# sch.net
KiCad netlist of a schematic drawn in EasyEDA Pro
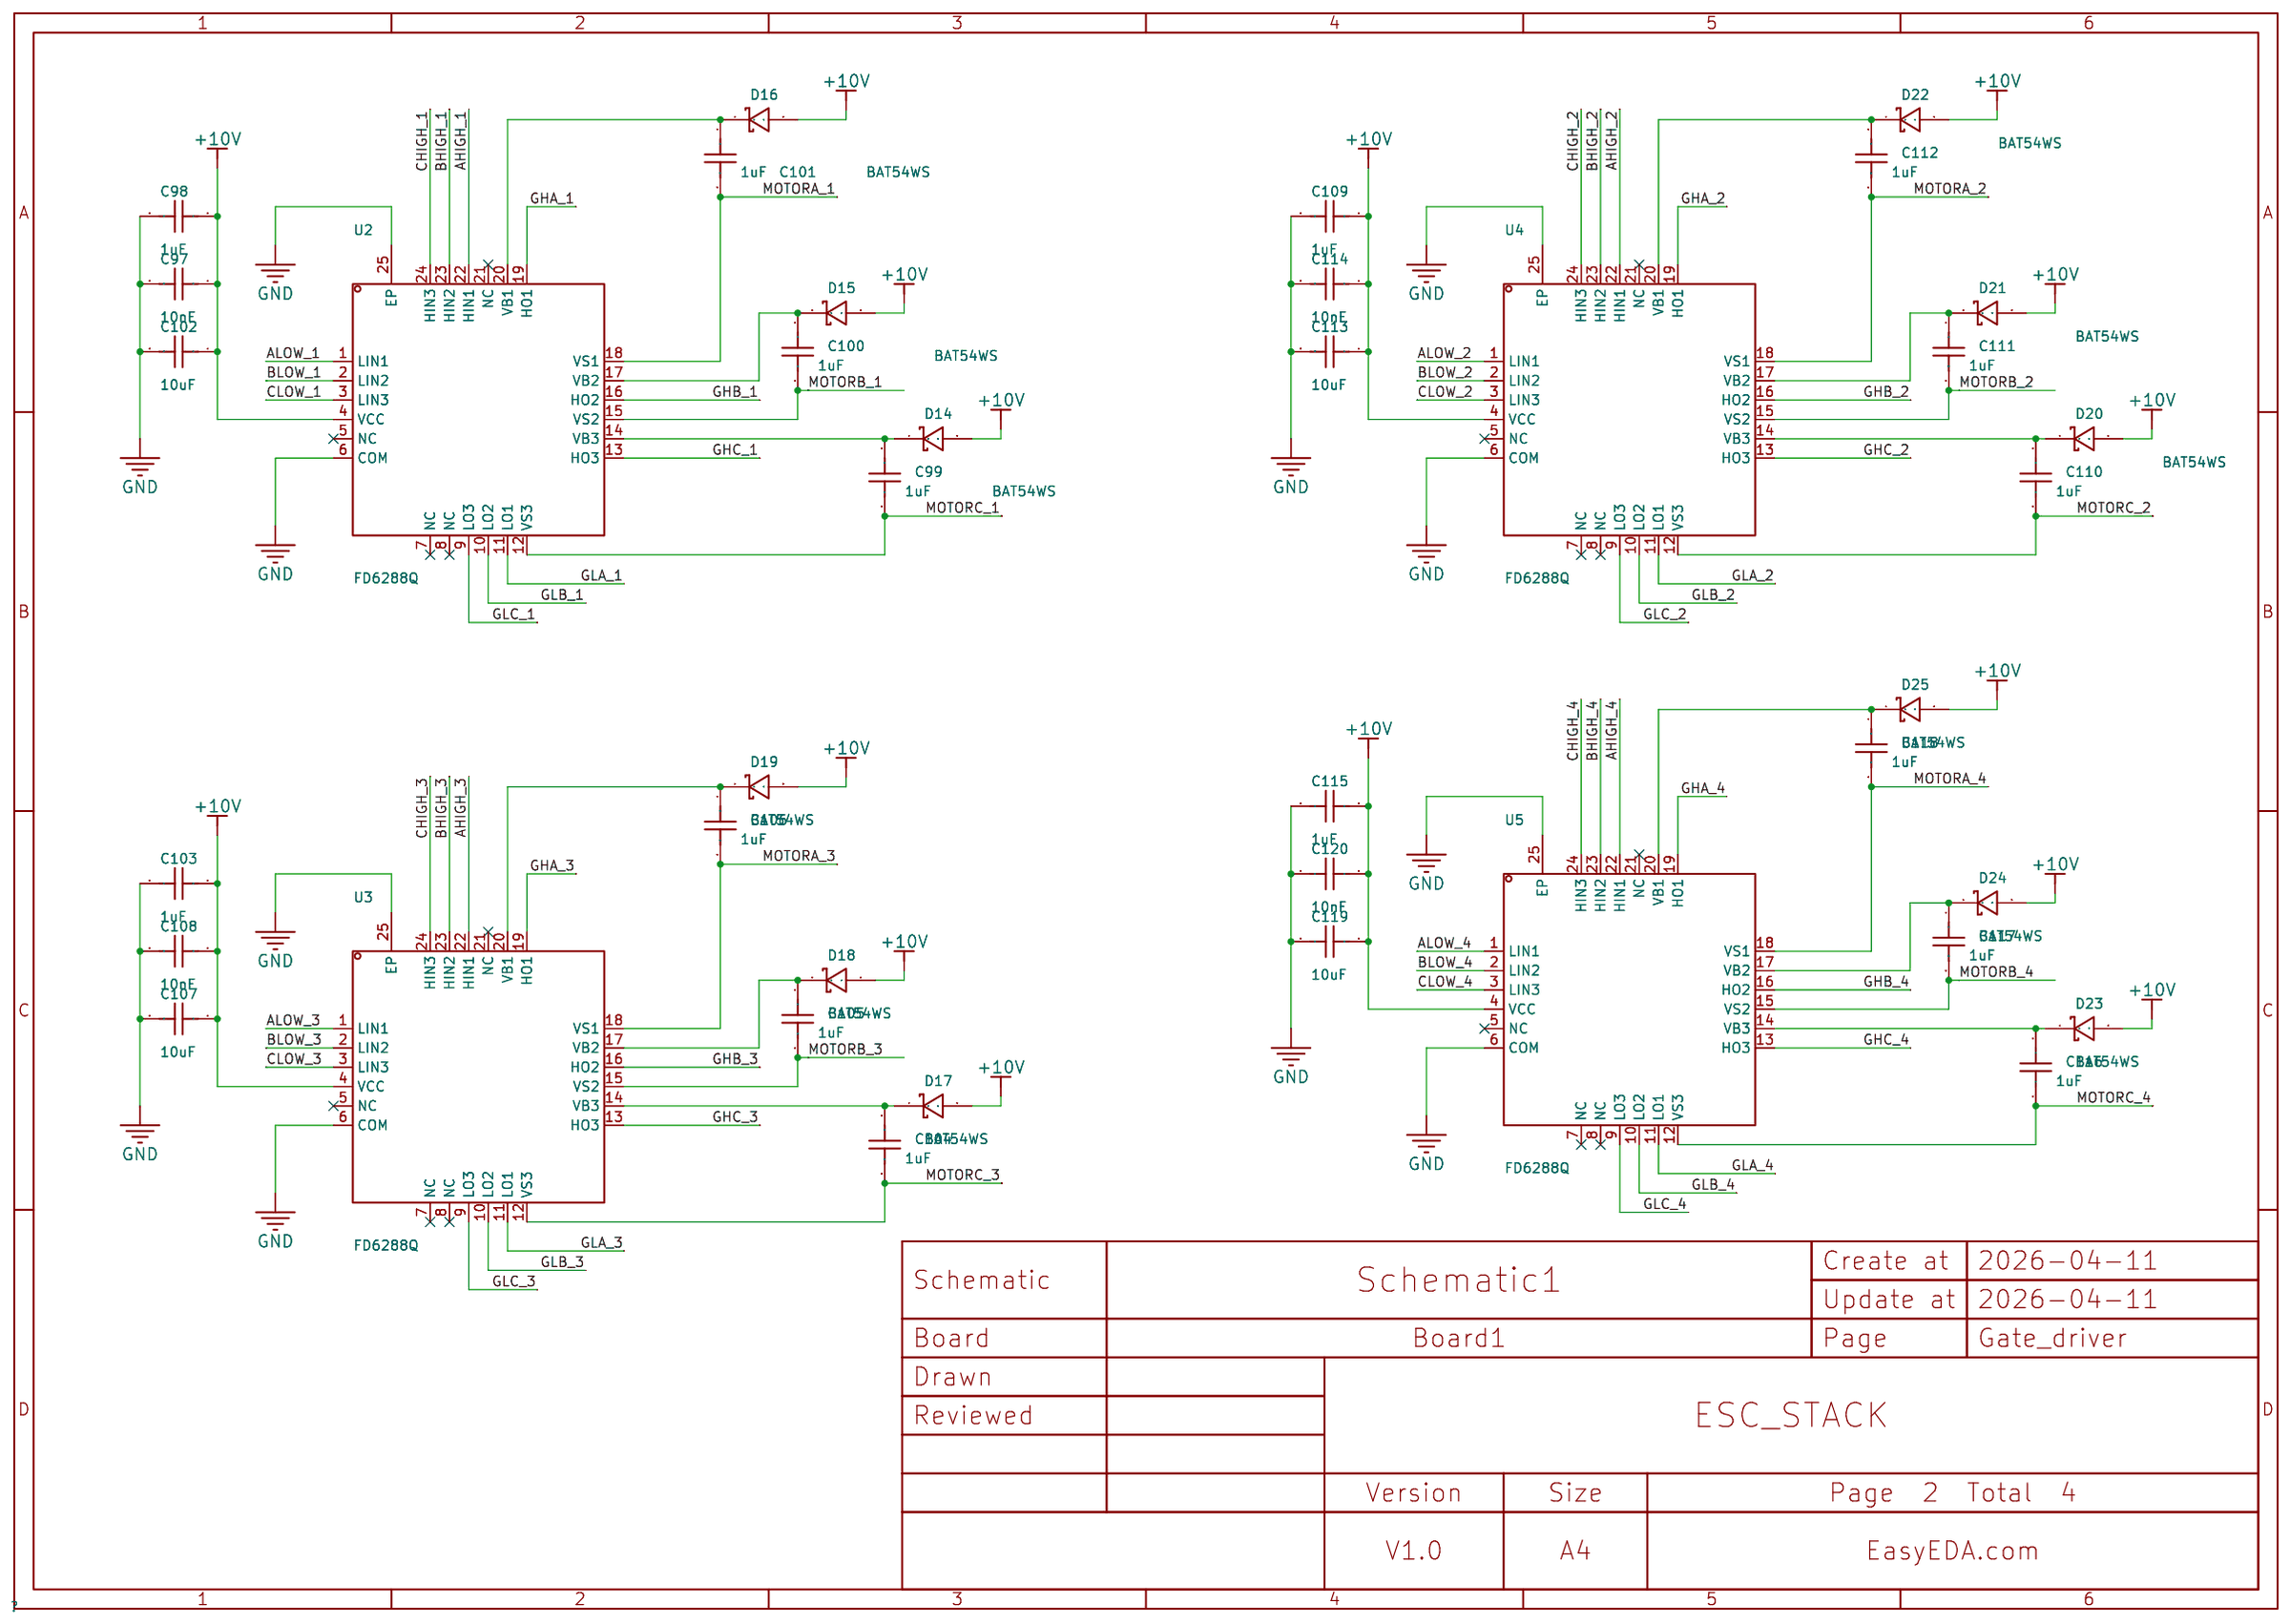
[diagram p0: Gate_driver]
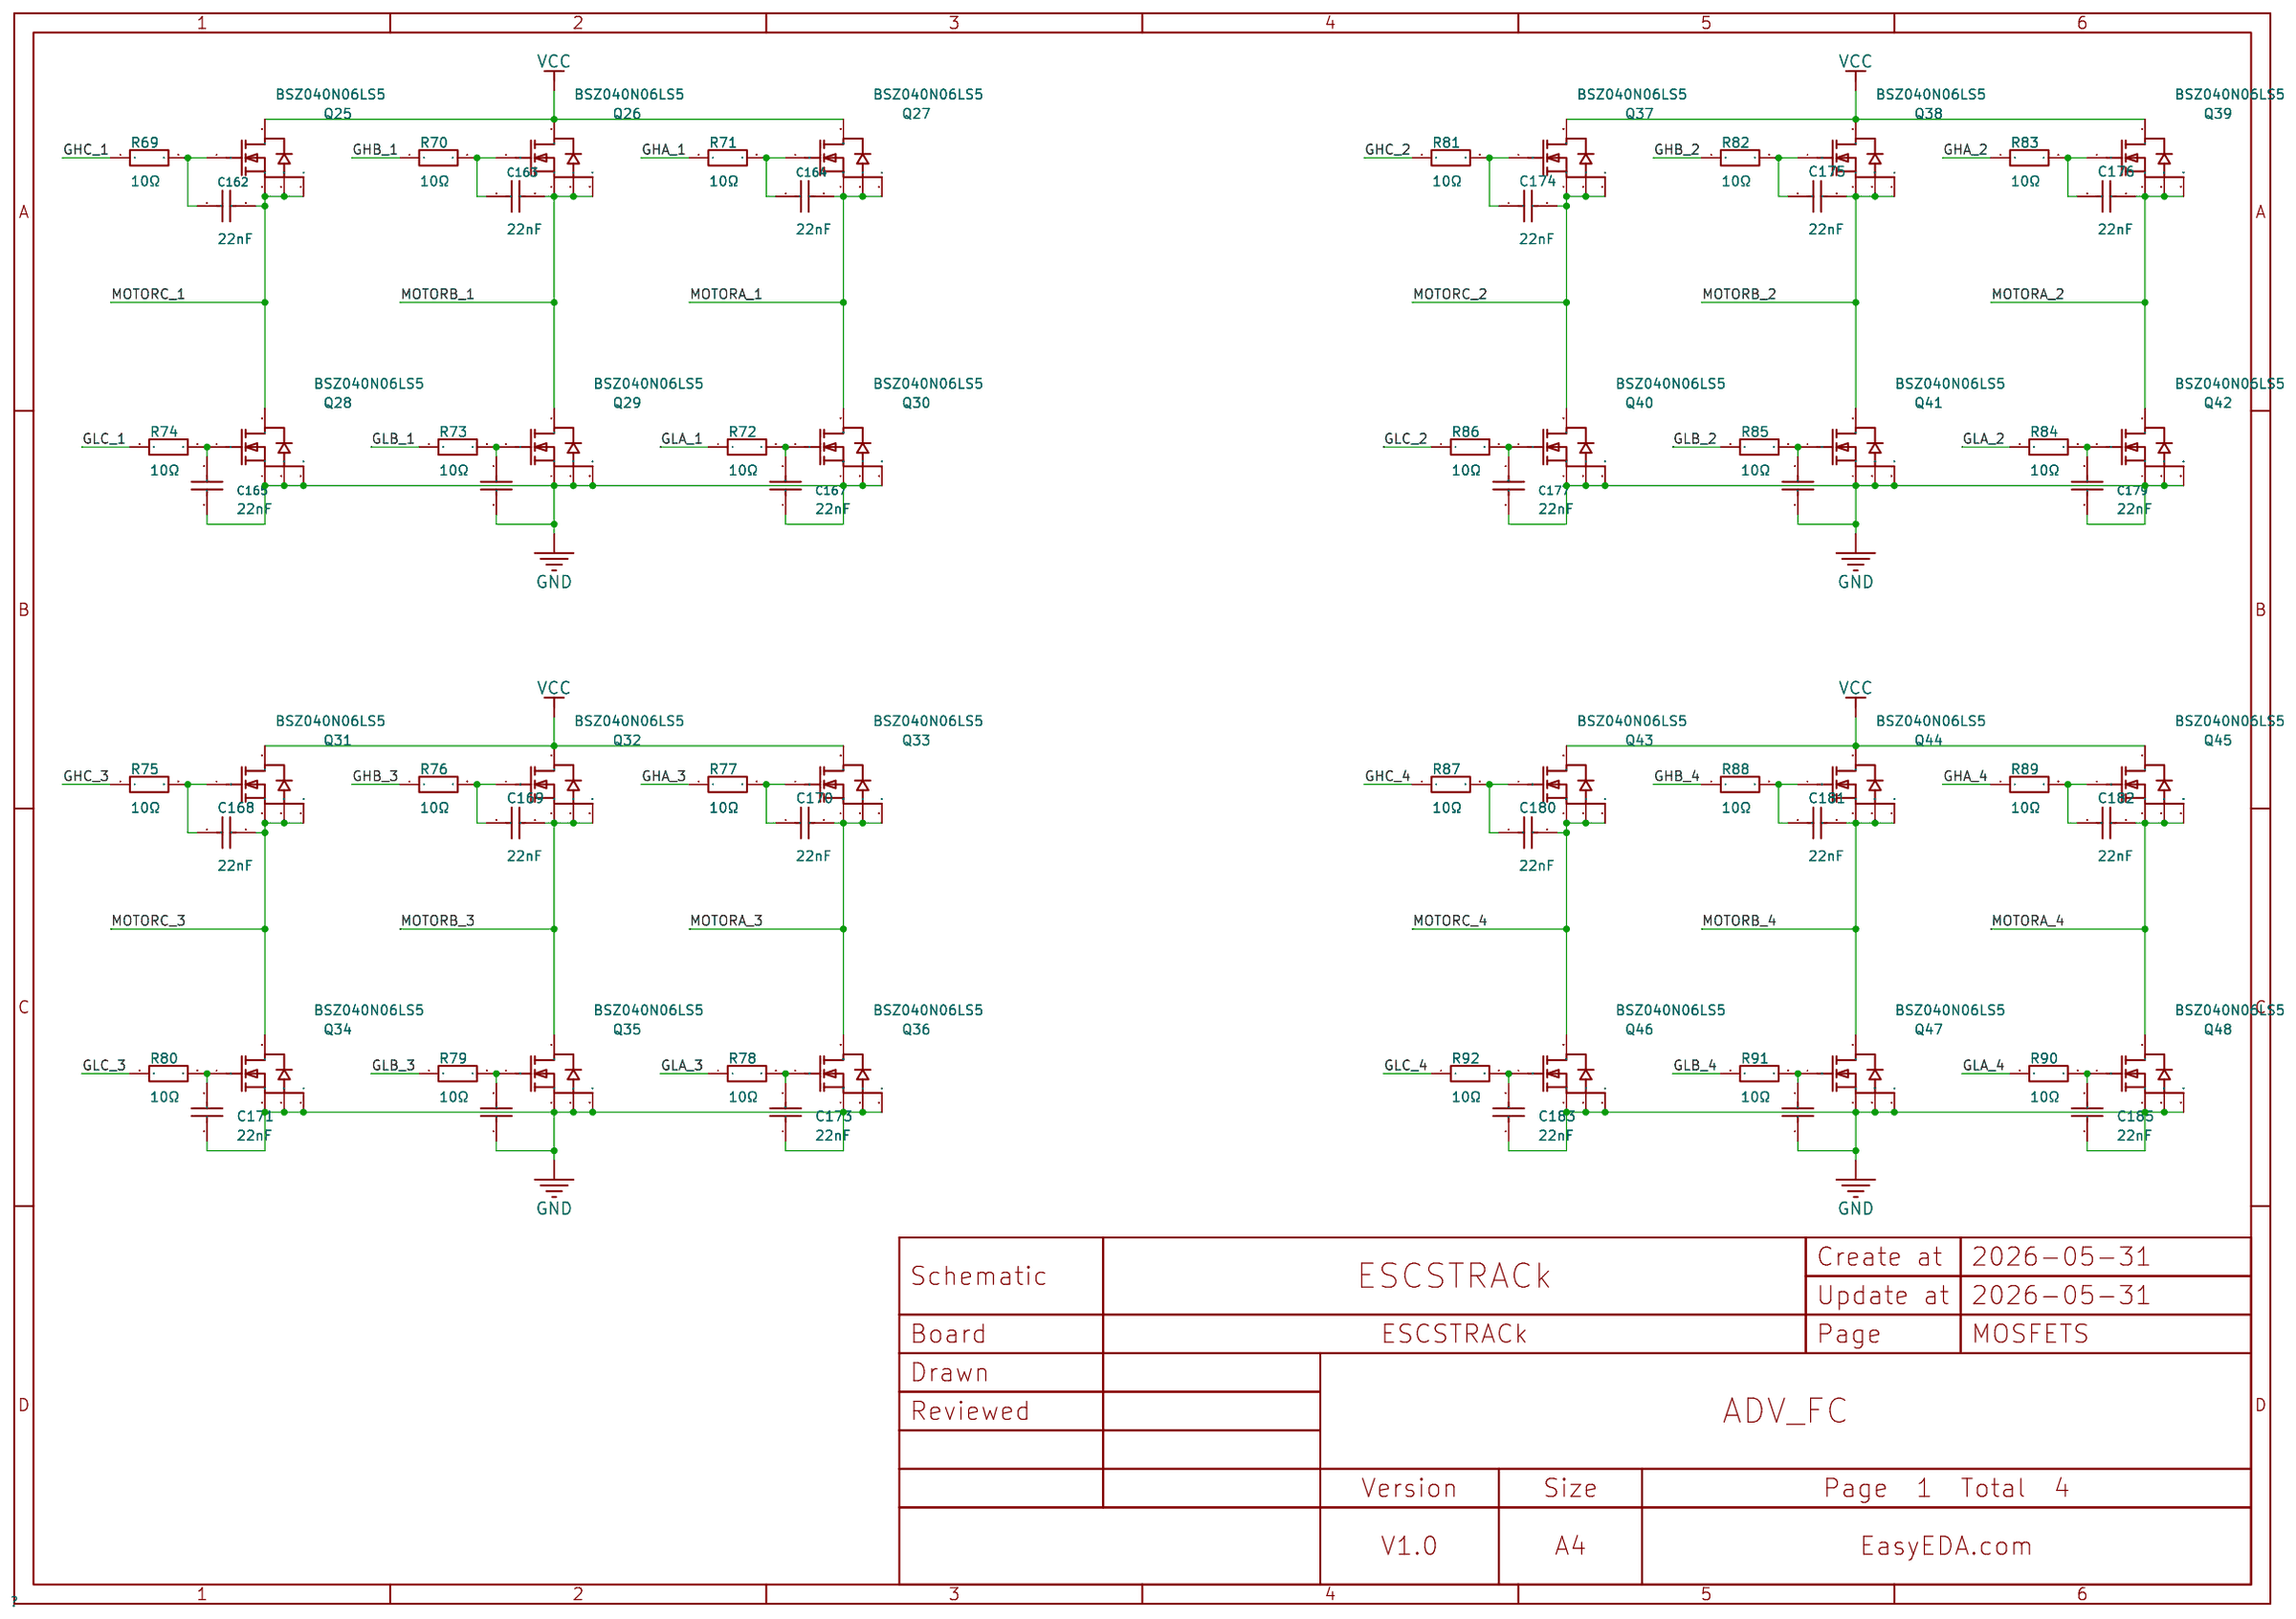
[diagram p1: MOSFETS]
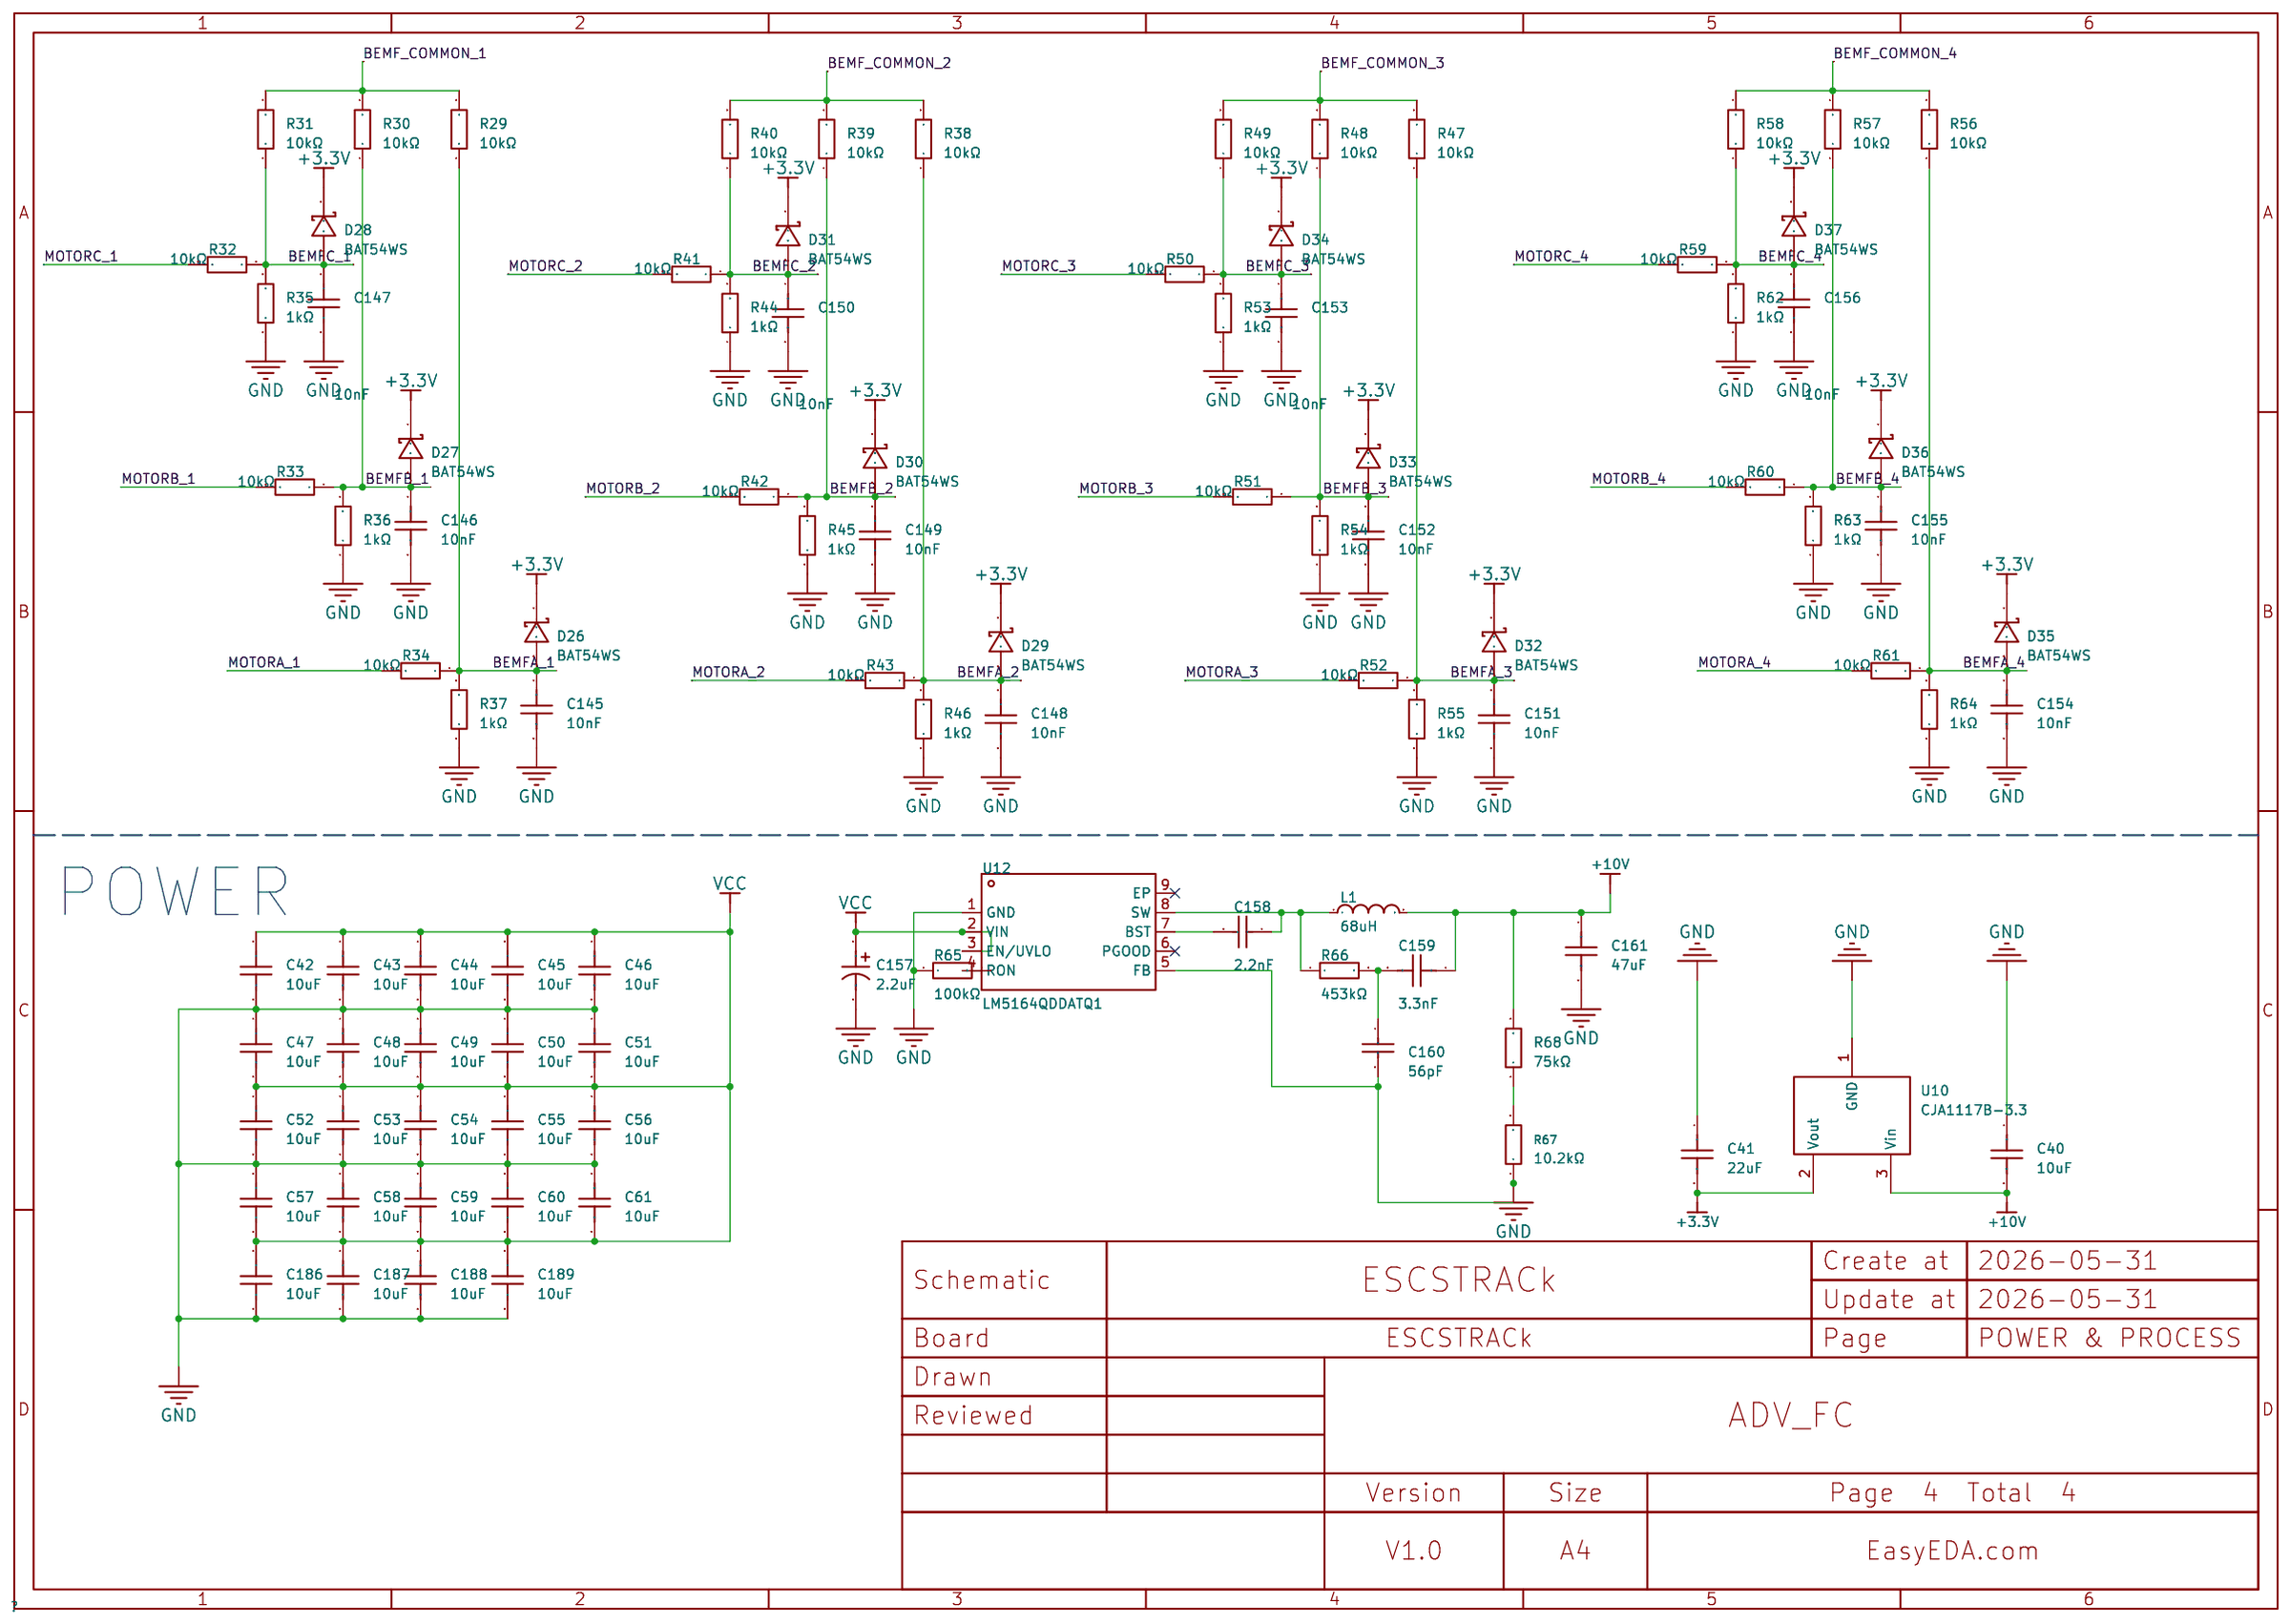
[diagram p2: POWER & PROCESS]
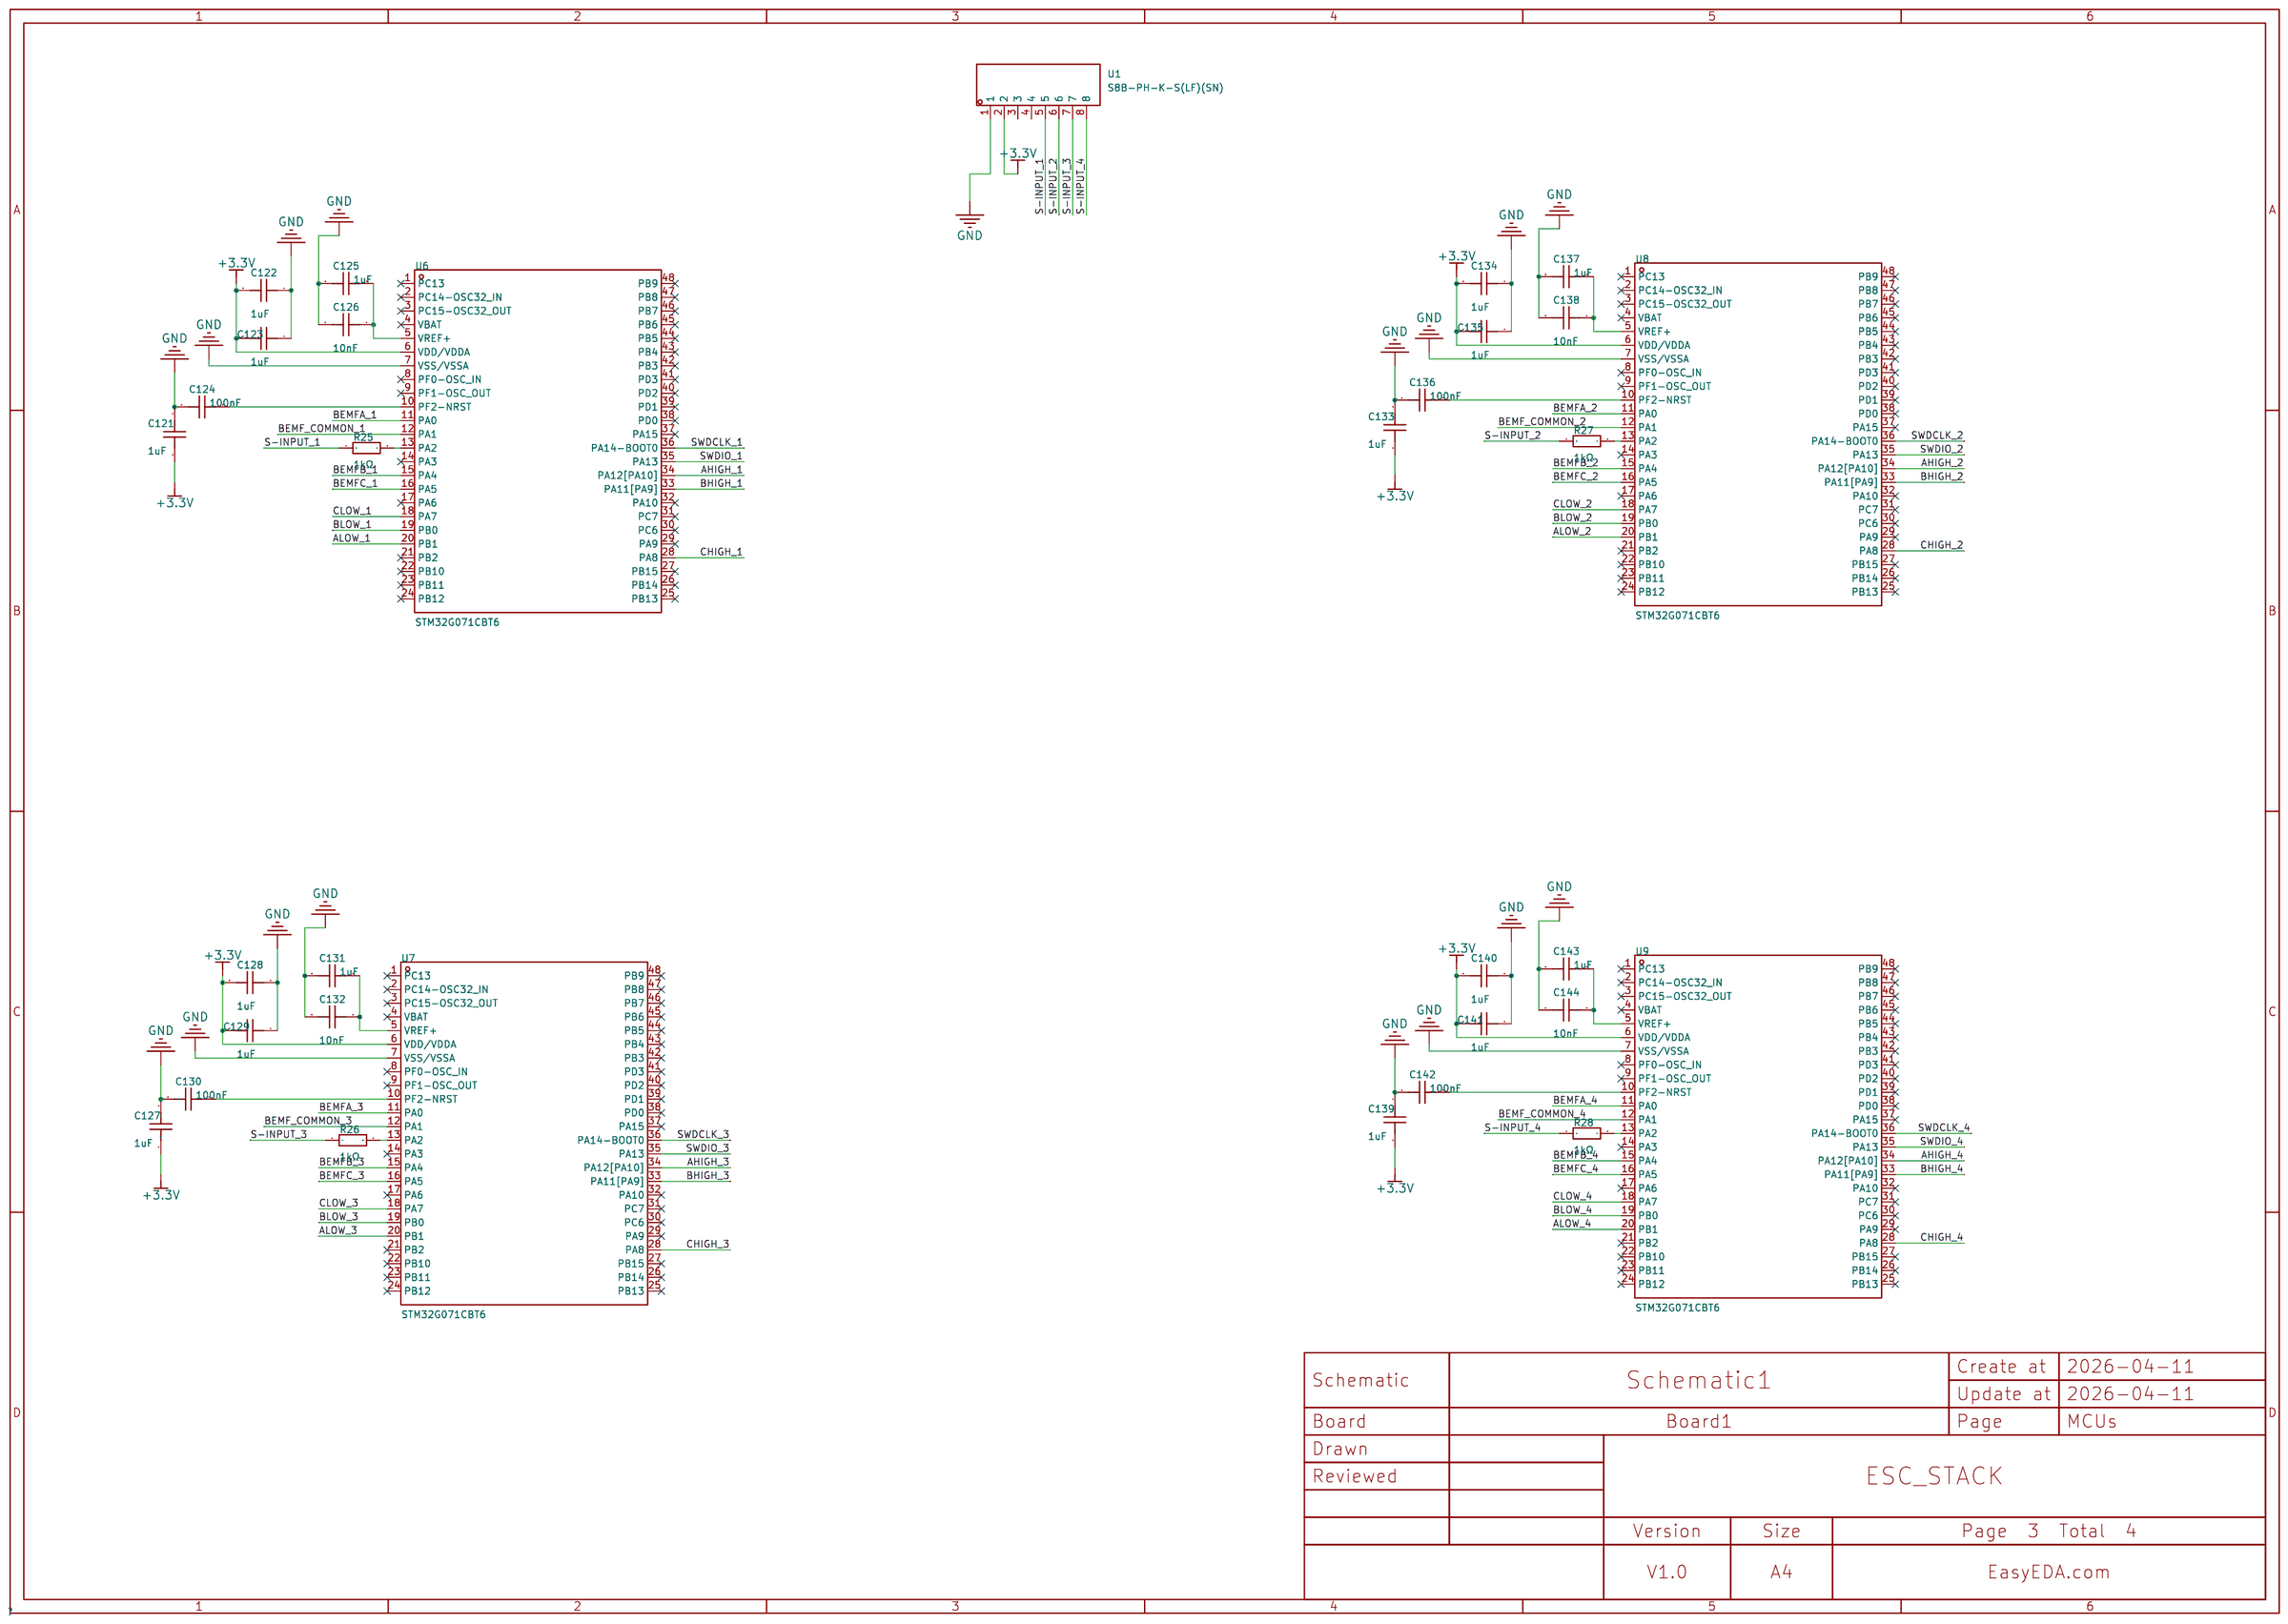
[diagram p3: MCUs]

(export (version "E")
  (design (tool "Eeschema 10.0.6"))
  (components
    (comp (ref "C97")
      (value "10nF")
      (description "Capacitance:10nF Tolerance:±10% Tolerance:±10% Voltage Rating:50V Temperature Coefficient:X7R")
      (fields
        (field (name "Manufacturer Part") "CC0402KRX7R9BB103")
        (field (name "Manufacturer") "YAGEO(国巨)")
      )
      (libsource (lib "easyedapro") (part "CAP"))
    )
    (comp (ref "C98")
      (value "1uF")
      (description "Capacitance:1uF Tolerance:±10% Tolerance:±10% Voltage Rating:25V Temperature Coefficient:X5R")
      (fields
        (field (name "Manufacturer Part") "CL05A105KA5NQNC")
        (field (name "Manufacturer") "SAMSUNG(三星)")
      )
      (libsource (lib "easyedapro") (part "CAP"))
    )
    (comp (ref "C99")
      (value "1uF")
      (description "Capacitance:1uF Tolerance:±10% Tolerance:±10% Voltage Rating:25V Temperature Coefficient:X5R")
      (fields
        (field (name "Manufacturer Part") "CL05A105KA5NQNC")
        (field (name "Manufacturer") "SAMSUNG(三星)")
      )
      (libsource (lib "easyedapro") (part "CAP"))
    )
    (comp (ref "C100")
      (value "1uF")
      (description "Capacitance:1uF Tolerance:±10% Tolerance:±10% Voltage Rating:25V Temperature Coefficient:X5R")
      (fields
        (field (name "Manufacturer Part") "CL05A105KA5NQNC")
        (field (name "Manufacturer") "SAMSUNG(三星)")
      )
      (libsource (lib "easyedapro") (part "CAP"))
    )
    (comp (ref "C101")
      (value "1uF")
      (description "Capacitance:1uF Tolerance:±10% Tolerance:±10% Voltage Rating:25V Temperature Coefficient:X5R")
      (fields
        (field (name "Manufacturer Part") "CL05A105KA5NQNC")
        (field (name "Manufacturer") "SAMSUNG(三星)")
      )
      (libsource (lib "easyedapro") (part "CAP"))
    )
    (comp (ref "C102")
      (value "10uF")
      (description "Capacitance:10uF Tolerance:±10% Tolerance:±10% Voltage Rating:50V Temperature Coefficient:X5R")
      (fields
        (field (name "Manufacturer Part") "CL31A106KBHNNNE")
        (field (name "Manufacturer") "SAMSUNG(三星)")
      )
      (libsource (lib "easyedapro") (part "CAP"))
    )
    (comp (ref "C103")
      (value "1uF")
      (description "Capacitance:1uF Tolerance:±10% Tolerance:±10% Voltage Rating:25V Temperature Coefficient:X5R")
      (fields
        (field (name "Manufacturer Part") "CL05A105KA5NQNC")
        (field (name "Manufacturer") "SAMSUNG(三星)")
      )
      (libsource (lib "easyedapro") (part "CAP"))
    )
    (comp (ref "C104")
      (value "1uF")
      (description "Capacitance:1uF Tolerance:±10% Tolerance:±10% Voltage Rating:25V Temperature Coefficient:X5R")
      (fields
        (field (name "Manufacturer Part") "CL05A105KA5NQNC")
        (field (name "Manufacturer") "SAMSUNG(三星)")
      )
      (libsource (lib "easyedapro") (part "CAP"))
    )
    (comp (ref "C105")
      (value "1uF")
      (description "Capacitance:1uF Tolerance:±10% Tolerance:±10% Voltage Rating:25V Temperature Coefficient:X5R")
      (fields
        (field (name "Manufacturer Part") "CL05A105KA5NQNC")
        (field (name "Manufacturer") "SAMSUNG(三星)")
      )
      (libsource (lib "easyedapro") (part "CAP"))
    )
    (comp (ref "C106")
      (value "1uF")
      (description "Capacitance:1uF Tolerance:±10% Tolerance:±10% Voltage Rating:25V Temperature Coefficient:X5R")
      (fields
        (field (name "Manufacturer Part") "CL05A105KA5NQNC")
        (field (name "Manufacturer") "SAMSUNG(三星)")
      )
      (libsource (lib "easyedapro") (part "CAP"))
    )
    (comp (ref "C107")
      (value "10uF")
      (description "Capacitance:10uF Tolerance:±10% Tolerance:±10% Voltage Rating:50V Temperature Coefficient:X5R")
      (fields
        (field (name "Manufacturer Part") "CL31A106KBHNNNE")
        (field (name "Manufacturer") "SAMSUNG(三星)")
      )
      (libsource (lib "easyedapro") (part "CAP"))
    )
    (comp (ref "C108")
      (value "10nF")
      (description "Capacitance:10nF Tolerance:±10% Tolerance:±10% Voltage Rating:50V Temperature Coefficient:X7R")
      (fields
        (field (name "Manufacturer Part") "CC0402KRX7R9BB103")
        (field (name "Manufacturer") "YAGEO(国巨)")
      )
      (libsource (lib "easyedapro") (part "CAP"))
    )
    (comp (ref "C109")
      (value "1uF")
      (description "Capacitance:1uF Tolerance:±10% Tolerance:±10% Voltage Rating:25V Temperature Coefficient:X5R")
      (fields
        (field (name "Manufacturer Part") "CL05A105KA5NQNC")
        (field (name "Manufacturer") "SAMSUNG(三星)")
      )
      (libsource (lib "easyedapro") (part "CAP"))
    )
    (comp (ref "C110")
      (value "1uF")
      (description "Capacitance:1uF Tolerance:±10% Tolerance:±10% Voltage Rating:25V Temperature Coefficient:X5R")
      (fields
        (field (name "Manufacturer Part") "CL05A105KA5NQNC")
        (field (name "Manufacturer") "SAMSUNG(三星)")
      )
      (libsource (lib "easyedapro") (part "CAP"))
    )
    (comp (ref "C111")
      (value "1uF")
      (description "Capacitance:1uF Tolerance:±10% Tolerance:±10% Voltage Rating:25V Temperature Coefficient:X5R")
      (fields
        (field (name "Manufacturer Part") "CL05A105KA5NQNC")
        (field (name "Manufacturer") "SAMSUNG(三星)")
      )
      (libsource (lib "easyedapro") (part "CAP"))
    )
    (comp (ref "C112")
      (value "1uF")
      (description "Capacitance:1uF Tolerance:±10% Tolerance:±10% Voltage Rating:25V Temperature Coefficient:X5R")
      (fields
        (field (name "Manufacturer Part") "CL05A105KA5NQNC")
        (field (name "Manufacturer") "SAMSUNG(三星)")
      )
      (libsource (lib "easyedapro") (part "CAP"))
    )
    (comp (ref "C113")
      (value "10uF")
      (description "Capacitance:10uF Tolerance:±10% Tolerance:±10% Voltage Rating:50V Temperature Coefficient:X5R")
      (fields
        (field (name "Manufacturer Part") "CL31A106KBHNNNE")
        (field (name "Manufacturer") "SAMSUNG(三星)")
      )
      (libsource (lib "easyedapro") (part "CAP"))
    )
    (comp (ref "C114")
      (value "10nF")
      (description "Capacitance:10nF Tolerance:±10% Tolerance:±10% Voltage Rating:50V Temperature Coefficient:X7R")
      (fields
        (field (name "Manufacturer Part") "CC0402KRX7R9BB103")
        (field (name "Manufacturer") "YAGEO(国巨)")
      )
      (libsource (lib "easyedapro") (part "CAP"))
    )
    (comp (ref "C115")
      (value "1uF")
      (description "Capacitance:1uF Tolerance:±10% Tolerance:±10% Voltage Rating:25V Temperature Coefficient:X5R")
      (fields
        (field (name "Manufacturer Part") "CL05A105KA5NQNC")
        (field (name "Manufacturer") "SAMSUNG(三星)")
      )
      (libsource (lib "easyedapro") (part "CAP"))
    )
    (comp (ref "C116")
      (value "1uF")
      (description "Capacitance:1uF Tolerance:±10% Tolerance:±10% Voltage Rating:25V Temperature Coefficient:X5R")
      (fields
        (field (name "Manufacturer Part") "CL05A105KA5NQNC")
        (field (name "Manufacturer") "SAMSUNG(三星)")
      )
      (libsource (lib "easyedapro") (part "CAP"))
    )
    (comp (ref "C117")
      (value "1uF")
      (description "Capacitance:1uF Tolerance:±10% Tolerance:±10% Voltage Rating:25V Temperature Coefficient:X5R")
      (fields
        (field (name "Manufacturer Part") "CL05A105KA5NQNC")
        (field (name "Manufacturer") "SAMSUNG(三星)")
      )
      (libsource (lib "easyedapro") (part "CAP"))
    )
    (comp (ref "C118")
      (value "1uF")
      (description "Capacitance:1uF Tolerance:±10% Tolerance:±10% Voltage Rating:25V Temperature Coefficient:X5R")
      (fields
        (field (name "Manufacturer Part") "CL05A105KA5NQNC")
        (field (name "Manufacturer") "SAMSUNG(三星)")
      )
      (libsource (lib "easyedapro") (part "CAP"))
    )
    (comp (ref "C119")
      (value "10uF")
      (description "Capacitance:10uF Tolerance:±10% Tolerance:±10% Voltage Rating:50V Temperature Coefficient:X5R")
      (fields
        (field (name "Manufacturer Part") "CL31A106KBHNNNE")
        (field (name "Manufacturer") "SAMSUNG(三星)")
      )
      (libsource (lib "easyedapro") (part "CAP"))
    )
    (comp (ref "C120")
      (value "10nF")
      (description "Capacitance:10nF Tolerance:±10% Tolerance:±10% Voltage Rating:50V Temperature Coefficient:X7R")
      (fields
        (field (name "Manufacturer Part") "CC0402KRX7R9BB103")
        (field (name "Manufacturer") "YAGEO(国巨)")
      )
      (libsource (lib "easyedapro") (part "CAP"))
    )
    (comp (ref "D14")
      (value "BAT54WS")
      (footprint "easyedapro:SOD-323_L1.7-W1.3-LS2.6-RD-1")
      (fields (field (name "Manufacturer") "High Diode(海德)"))
      (libsource (lib "easyedapro") (part "BAT54WS_C466657"))
    )
    (comp (ref "D15")
      (value "BAT54WS")
      (footprint "easyedapro:SOD-323_L1.7-W1.3-LS2.6-RD-1")
      (fields (field (name "Manufacturer") "High Diode(海德)"))
      (libsource (lib "easyedapro") (part "BAT54WS_C466657"))
    )
    (comp (ref "D16")
      (value "BAT54WS")
      (footprint "easyedapro:SOD-323_L1.7-W1.3-LS2.6-RD-1")
      (fields (field (name "Manufacturer") "High Diode(海德)"))
      (libsource (lib "easyedapro") (part "BAT54WS_C466657"))
    )
    (comp (ref "D17")
      (value "BAT54WS")
      (footprint "easyedapro:SOD-323_L1.7-W1.3-LS2.6-RD-1")
      (fields (field (name "Manufacturer") "High Diode(海德)"))
      (libsource (lib "easyedapro") (part "BAT54WS_C466657"))
    )
    (comp (ref "D18")
      (value "BAT54WS")
      (footprint "easyedapro:SOD-323_L1.7-W1.3-LS2.6-RD-1")
      (fields (field (name "Manufacturer") "High Diode(海德)"))
      (libsource (lib "easyedapro") (part "BAT54WS_C466657"))
    )
    (comp (ref "D19")
      (value "BAT54WS")
      (footprint "easyedapro:SOD-323_L1.7-W1.3-LS2.6-RD-1")
      (fields (field (name "Manufacturer") "High Diode(海德)"))
      (libsource (lib "easyedapro") (part "BAT54WS_C466657"))
    )
    (comp (ref "D20")
      (value "BAT54WS")
      (footprint "easyedapro:SOD-323_L1.7-W1.3-LS2.6-RD-1")
      (fields (field (name "Manufacturer") "High Diode(海德)"))
      (libsource (lib "easyedapro") (part "BAT54WS_C466657"))
    )
    (comp (ref "D21")
      (value "BAT54WS")
      (footprint "easyedapro:SOD-323_L1.7-W1.3-LS2.6-RD-1")
      (fields (field (name "Manufacturer") "High Diode(海德)"))
      (libsource (lib "easyedapro") (part "BAT54WS_C466657"))
    )
    (comp (ref "D22")
      (value "BAT54WS")
      (footprint "easyedapro:SOD-323_L1.7-W1.3-LS2.6-RD-1")
      (fields (field (name "Manufacturer") "High Diode(海德)"))
      (libsource (lib "easyedapro") (part "BAT54WS_C466657"))
    )
    (comp (ref "D23")
      (value "BAT54WS")
      (footprint "easyedapro:SOD-323_L1.7-W1.3-LS2.6-RD-1")
      (fields (field (name "Manufacturer") "High Diode(海德)"))
      (libsource (lib "easyedapro") (part "BAT54WS_C466657"))
    )
    (comp (ref "D24")
      (value "BAT54WS")
      (footprint "easyedapro:SOD-323_L1.7-W1.3-LS2.6-RD-1")
      (fields (field (name "Manufacturer") "High Diode(海德)"))
      (libsource (lib "easyedapro") (part "BAT54WS_C466657"))
    )
    (comp (ref "D25")
      (value "BAT54WS")
      (footprint "easyedapro:SOD-323_L1.7-W1.3-LS2.6-RD-1")
      (fields (field (name "Manufacturer") "High Diode(海德)"))
      (libsource (lib "easyedapro") (part "BAT54WS_C466657"))
    )
    (comp (ref "U2")
      (value "FD6288Q")
      (footprint "easyedapro:QFN-24_L4.0-W4.0-P0.50-BL-EP2.6")
      (fields (field (name "Manufacturer") "Fortior Tech(峰岹)"))
      (libsource (lib "easyedapro") (part "FD6288Q_C328453"))
    )
    (comp (ref "U3")
      (value "FD6288Q")
      (footprint "easyedapro:QFN-24_L4.0-W4.0-P0.50-BL-EP2.6")
      (fields (field (name "Manufacturer") "Fortior Tech(峰岹)"))
      (libsource (lib "easyedapro") (part "FD6288Q_C328453"))
    )
    (comp (ref "U4")
      (value "FD6288Q")
      (footprint "easyedapro:QFN-24_L4.0-W4.0-P0.50-BL-EP2.6")
      (fields (field (name "Manufacturer") "Fortior Tech(峰岹)"))
      (libsource (lib "easyedapro") (part "FD6288Q_C328453"))
    )
    (comp (ref "U5")
      (value "FD6288Q")
      (footprint "easyedapro:QFN-24_L4.0-W4.0-P0.50-BL-EP2.6")
      (fields (field (name "Manufacturer") "Fortior Tech(峰岹)"))
      (libsource (lib "easyedapro") (part "FD6288Q_C328453"))
    )
    (comp (ref "C162")
      (value "22nF")
      (footprint "easyedapro:C0603")
      (description "Capacitance:22nF Tolerance:±10% Tolerance:±10% Voltage Rating:50V Temperature Coefficient:X7R")
      (fields
        (field (name "Manufacturer Part") "CL10B223KB8NNNC")
        (field (name "Manufacturer") "SAMSUNG(三星)")
      )
      (libsource (lib "easyedapro") (part "CL10B223KB8NNNC"))
    )
    (comp (ref "C163")
      (value "22nF")
      (footprint "easyedapro:C0603")
      (description "Capacitance:22nF Tolerance:±10% Tolerance:±10% Voltage Rating:50V Temperature Coefficient:X7R")
      (fields
        (field (name "Manufacturer Part") "CL10B223KB8NNNC")
        (field (name "Manufacturer") "SAMSUNG(三星)")
      )
      (libsource (lib "easyedapro") (part "CL10B223KB8NNNC"))
    )
    (comp (ref "C164")
      (value "22nF")
      (footprint "easyedapro:C0603")
      (description "Capacitance:22nF Tolerance:±10% Tolerance:±10% Voltage Rating:50V Temperature Coefficient:X7R")
      (fields
        (field (name "Manufacturer Part") "CL10B223KB8NNNC")
        (field (name "Manufacturer") "SAMSUNG(三星)")
      )
      (libsource (lib "easyedapro") (part "CL10B223KB8NNNC"))
    )
    (comp (ref "C165")
      (value "22nF")
      (footprint "easyedapro:C0603")
      (description "Capacitance:22nF Tolerance:±10% Tolerance:±10% Voltage Rating:50V Temperature Coefficient:X7R")
      (fields
        (field (name "Manufacturer Part") "CL10B223KB8NNNC")
        (field (name "Manufacturer") "SAMSUNG(三星)")
      )
      (libsource (lib "easyedapro") (part "CL10B223KB8NNNC"))
    )
    (comp (ref "C166")
      (value "22nF")
      (footprint "easyedapro:C0603")
      (description "Capacitance:22nF Tolerance:±10% Tolerance:±10% Voltage Rating:50V Temperature Coefficient:X7R")
      (fields
        (field (name "Manufacturer Part") "CL10B223KB8NNNC")
        (field (name "Manufacturer") "SAMSUNG(三星)")
      )
      (libsource (lib "easyedapro") (part "CL10B223KB8NNNC"))
    )
    (comp (ref "C167")
      (value "22nF")
      (footprint "easyedapro:C0603")
      (description "Capacitance:22nF Tolerance:±10% Tolerance:±10% Voltage Rating:50V Temperature Coefficient:X7R")
      (fields
        (field (name "Manufacturer Part") "CL10B223KB8NNNC")
        (field (name "Manufacturer") "SAMSUNG(三星)")
      )
      (libsource (lib "easyedapro") (part "CL10B223KB8NNNC"))
    )
    (comp (ref "C168")
      (value "22nF")
      (footprint "easyedapro:C0603")
      (description "Capacitance:22nF Tolerance:±10% Tolerance:±10% Voltage Rating:50V Temperature Coefficient:X7R")
      (fields
        (field (name "Manufacturer Part") "CL10B223KB8NNNC")
        (field (name "Manufacturer") "SAMSUNG(三星)")
      )
      (libsource (lib "easyedapro") (part "CL10B223KB8NNNC"))
    )
    (comp (ref "C169")
      (value "22nF")
      (footprint "easyedapro:C0603")
      (description "Capacitance:22nF Tolerance:±10% Tolerance:±10% Voltage Rating:50V Temperature Coefficient:X7R")
      (fields
        (field (name "Manufacturer Part") "CL10B223KB8NNNC")
        (field (name "Manufacturer") "SAMSUNG(三星)")
      )
      (libsource (lib "easyedapro") (part "CL10B223KB8NNNC"))
    )
    (comp (ref "C170")
      (value "22nF")
      (footprint "easyedapro:C0603")
      (description "Capacitance:22nF Tolerance:±10% Tolerance:±10% Voltage Rating:50V Temperature Coefficient:X7R")
      (fields
        (field (name "Manufacturer Part") "CL10B223KB8NNNC")
        (field (name "Manufacturer") "SAMSUNG(三星)")
      )
      (libsource (lib "easyedapro") (part "CL10B223KB8NNNC"))
    )
    (comp (ref "C171")
      (value "22nF")
      (footprint "easyedapro:C0603")
      (description "Capacitance:22nF Tolerance:±10% Tolerance:±10% Voltage Rating:50V Temperature Coefficient:X7R")
      (fields
        (field (name "Manufacturer Part") "CL10B223KB8NNNC")
        (field (name "Manufacturer") "SAMSUNG(三星)")
      )
      (libsource (lib "easyedapro") (part "CL10B223KB8NNNC"))
    )
    (comp (ref "C172")
      (value "22nF")
      (footprint "easyedapro:C0603")
      (description "Capacitance:22nF Tolerance:±10% Tolerance:±10% Voltage Rating:50V Temperature Coefficient:X7R")
      (fields
        (field (name "Manufacturer Part") "CL10B223KB8NNNC")
        (field (name "Manufacturer") "SAMSUNG(三星)")
      )
      (libsource (lib "easyedapro") (part "CL10B223KB8NNNC"))
    )
    (comp (ref "C173")
      (value "22nF")
      (footprint "easyedapro:C0603")
      (description "Capacitance:22nF Tolerance:±10% Tolerance:±10% Voltage Rating:50V Temperature Coefficient:X7R")
      (fields
        (field (name "Manufacturer Part") "CL10B223KB8NNNC")
        (field (name "Manufacturer") "SAMSUNG(三星)")
      )
      (libsource (lib "easyedapro") (part "CL10B223KB8NNNC"))
    )
    (comp (ref "C174")
      (value "22nF")
      (footprint "easyedapro:C0603")
      (description "Capacitance:22nF Tolerance:±10% Tolerance:±10% Voltage Rating:50V Temperature Coefficient:X7R")
      (fields
        (field (name "Manufacturer Part") "CL10B223KB8NNNC")
        (field (name "Manufacturer") "SAMSUNG(三星)")
      )
      (libsource (lib "easyedapro") (part "CL10B223KB8NNNC"))
    )
    (comp (ref "C175")
      (value "22nF")
      (footprint "easyedapro:C0603")
      (description "Capacitance:22nF Tolerance:±10% Tolerance:±10% Voltage Rating:50V Temperature Coefficient:X7R")
      (fields
        (field (name "Manufacturer Part") "CL10B223KB8NNNC")
        (field (name "Manufacturer") "SAMSUNG(三星)")
      )
      (libsource (lib "easyedapro") (part "CL10B223KB8NNNC"))
    )
    (comp (ref "C176")
      (value "22nF")
      (footprint "easyedapro:C0603")
      (description "Capacitance:22nF Tolerance:±10% Tolerance:±10% Voltage Rating:50V Temperature Coefficient:X7R")
      (fields
        (field (name "Manufacturer Part") "CL10B223KB8NNNC")
        (field (name "Manufacturer") "SAMSUNG(三星)")
      )
      (libsource (lib "easyedapro") (part "CL10B223KB8NNNC"))
    )
    (comp (ref "C177")
      (value "22nF")
      (footprint "easyedapro:C0603")
      (description "Capacitance:22nF Tolerance:±10% Tolerance:±10% Voltage Rating:50V Temperature Coefficient:X7R")
      (fields
        (field (name "Manufacturer Part") "CL10B223KB8NNNC")
        (field (name "Manufacturer") "SAMSUNG(三星)")
      )
      (libsource (lib "easyedapro") (part "CL10B223KB8NNNC"))
    )
    (comp (ref "C178")
      (value "22nF")
      (footprint "easyedapro:C0603")
      (description "Capacitance:22nF Tolerance:±10% Tolerance:±10% Voltage Rating:50V Temperature Coefficient:X7R")
      (fields
        (field (name "Manufacturer Part") "CL10B223KB8NNNC")
        (field (name "Manufacturer") "SAMSUNG(三星)")
      )
      (libsource (lib "easyedapro") (part "CL10B223KB8NNNC"))
    )
    (comp (ref "C179")
      (value "22nF")
      (footprint "easyedapro:C0603")
      (description "Capacitance:22nF Tolerance:±10% Tolerance:±10% Voltage Rating:50V Temperature Coefficient:X7R")
      (fields
        (field (name "Manufacturer Part") "CL10B223KB8NNNC")
        (field (name "Manufacturer") "SAMSUNG(三星)")
      )
      (libsource (lib "easyedapro") (part "CL10B223KB8NNNC"))
    )
    (comp (ref "C180")
      (value "22nF")
      (footprint "easyedapro:C0603")
      (description "Capacitance:22nF Tolerance:±10% Tolerance:±10% Voltage Rating:50V Temperature Coefficient:X7R")
      (fields
        (field (name "Manufacturer Part") "CL10B223KB8NNNC")
        (field (name "Manufacturer") "SAMSUNG(三星)")
      )
      (libsource (lib "easyedapro") (part "CL10B223KB8NNNC"))
    )
    (comp (ref "C181")
      (value "22nF")
      (footprint "easyedapro:C0603")
      (description "Capacitance:22nF Tolerance:±10% Tolerance:±10% Voltage Rating:50V Temperature Coefficient:X7R")
      (fields
        (field (name "Manufacturer Part") "CL10B223KB8NNNC")
        (field (name "Manufacturer") "SAMSUNG(三星)")
      )
      (libsource (lib "easyedapro") (part "CL10B223KB8NNNC"))
    )
    (comp (ref "C182")
      (value "22nF")
      (footprint "easyedapro:C0603")
      (description "Capacitance:22nF Tolerance:±10% Tolerance:±10% Voltage Rating:50V Temperature Coefficient:X7R")
      (fields
        (field (name "Manufacturer Part") "CL10B223KB8NNNC")
        (field (name "Manufacturer") "SAMSUNG(三星)")
      )
      (libsource (lib "easyedapro") (part "CL10B223KB8NNNC"))
    )
    (comp (ref "C183")
      (value "22nF")
      (footprint "easyedapro:C0603")
      (description "Capacitance:22nF Tolerance:±10% Tolerance:±10% Voltage Rating:50V Temperature Coefficient:X7R")
      (fields
        (field (name "Manufacturer Part") "CL10B223KB8NNNC")
        (field (name "Manufacturer") "SAMSUNG(三星)")
      )
      (libsource (lib "easyedapro") (part "CL10B223KB8NNNC"))
    )
    (comp (ref "C184")
      (value "22nF")
      (footprint "easyedapro:C0603")
      (description "Capacitance:22nF Tolerance:±10% Tolerance:±10% Voltage Rating:50V Temperature Coefficient:X7R")
      (fields
        (field (name "Manufacturer Part") "CL10B223KB8NNNC")
        (field (name "Manufacturer") "SAMSUNG(三星)")
      )
      (libsource (lib "easyedapro") (part "CL10B223KB8NNNC"))
    )
    (comp (ref "C185")
      (value "22nF")
      (footprint "easyedapro:C0603")
      (description "Capacitance:22nF Tolerance:±10% Tolerance:±10% Voltage Rating:50V Temperature Coefficient:X7R")
      (fields
        (field (name "Manufacturer Part") "CL10B223KB8NNNC")
        (field (name "Manufacturer") "SAMSUNG(三星)")
      )
      (libsource (lib "easyedapro") (part "CL10B223KB8NNNC"))
    )
    (comp (ref "Q25")
      (value "BSZ040N06LS5")
      (footprint "easyedapro:DFN-8_L3.3-W3.3-P0.65-BL-2")
      (fields (field (name "Manufacturer") "Infineon(英飞凌)"))
      (libsource (lib "easyedapro") (part "BSZ040N06LS5ATMA1"))
    )
    (comp (ref "Q26")
      (value "BSZ040N06LS5")
      (footprint "easyedapro:DFN-8_L3.3-W3.3-P0.65-BL-2")
      (fields (field (name "Manufacturer") "Infineon(英飞凌)"))
      (libsource (lib "easyedapro") (part "BSZ040N06LS5ATMA1"))
    )
    (comp (ref "Q27")
      (value "BSZ040N06LS5")
      (footprint "easyedapro:DFN-8_L3.3-W3.3-P0.65-BL-2")
      (fields (field (name "Manufacturer") "Infineon(英飞凌)"))
      (libsource (lib "easyedapro") (part "BSZ040N06LS5ATMA1"))
    )
    (comp (ref "Q28")
      (value "BSZ040N06LS5")
      (footprint "easyedapro:DFN-8_L3.3-W3.3-P0.65-BL-2")
      (fields (field (name "Manufacturer") "Infineon(英飞凌)"))
      (libsource (lib "easyedapro") (part "BSZ040N06LS5ATMA1"))
    )
    (comp (ref "Q29")
      (value "BSZ040N06LS5")
      (footprint "easyedapro:DFN-8_L3.3-W3.3-P0.65-BL-2")
      (fields (field (name "Manufacturer") "Infineon(英飞凌)"))
      (libsource (lib "easyedapro") (part "BSZ040N06LS5ATMA1"))
    )
    (comp (ref "Q30")
      (value "BSZ040N06LS5")
      (footprint "easyedapro:DFN-8_L3.3-W3.3-P0.65-BL-2")
      (fields (field (name "Manufacturer") "Infineon(英飞凌)"))
      (libsource (lib "easyedapro") (part "BSZ040N06LS5ATMA1"))
    )
    (comp (ref "Q31")
      (value "BSZ040N06LS5")
      (footprint "easyedapro:DFN-8_L3.3-W3.3-P0.65-BL-2")
      (fields (field (name "Manufacturer") "Infineon(英飞凌)"))
      (libsource (lib "easyedapro") (part "BSZ040N06LS5ATMA1"))
    )
    (comp (ref "Q32")
      (value "BSZ040N06LS5")
      (footprint "easyedapro:DFN-8_L3.3-W3.3-P0.65-BL-2")
      (fields (field (name "Manufacturer") "Infineon(英飞凌)"))
      (libsource (lib "easyedapro") (part "BSZ040N06LS5ATMA1"))
    )
    (comp (ref "Q33")
      (value "BSZ040N06LS5")
      (footprint "easyedapro:DFN-8_L3.3-W3.3-P0.65-BL-2")
      (fields (field (name "Manufacturer") "Infineon(英飞凌)"))
      (libsource (lib "easyedapro") (part "BSZ040N06LS5ATMA1"))
    )
    (comp (ref "Q34")
      (value "BSZ040N06LS5")
      (footprint "easyedapro:DFN-8_L3.3-W3.3-P0.65-BL-2")
      (fields (field (name "Manufacturer") "Infineon(英飞凌)"))
      (libsource (lib "easyedapro") (part "BSZ040N06LS5ATMA1"))
    )
    (comp (ref "Q35")
      (value "BSZ040N06LS5")
      (footprint "easyedapro:DFN-8_L3.3-W3.3-P0.65-BL-2")
      (fields (field (name "Manufacturer") "Infineon(英飞凌)"))
      (libsource (lib "easyedapro") (part "BSZ040N06LS5ATMA1"))
    )
    (comp (ref "Q36")
      (value "BSZ040N06LS5")
      (footprint "easyedapro:DFN-8_L3.3-W3.3-P0.65-BL-2")
      (fields (field (name "Manufacturer") "Infineon(英飞凌)"))
      (libsource (lib "easyedapro") (part "BSZ040N06LS5ATMA1"))
    )
    (comp (ref "Q37")
      (value "BSZ040N06LS5")
      (footprint "easyedapro:DFN-8_L3.3-W3.3-P0.65-BL-2")
      (fields (field (name "Manufacturer") "Infineon(英飞凌)"))
      (libsource (lib "easyedapro") (part "BSZ040N06LS5ATMA1"))
    )
    (comp (ref "Q38")
      (value "BSZ040N06LS5")
      (footprint "easyedapro:DFN-8_L3.3-W3.3-P0.65-BL-2")
      (fields (field (name "Manufacturer") "Infineon(英飞凌)"))
      (libsource (lib "easyedapro") (part "BSZ040N06LS5ATMA1"))
    )
    (comp (ref "Q39")
      (value "BSZ040N06LS5")
      (footprint "easyedapro:DFN-8_L3.3-W3.3-P0.65-BL-2")
      (fields (field (name "Manufacturer") "Infineon(英飞凌)"))
      (libsource (lib "easyedapro") (part "BSZ040N06LS5ATMA1"))
    )
    (comp (ref "Q40")
      (value "BSZ040N06LS5")
      (footprint "easyedapro:DFN-8_L3.3-W3.3-P0.65-BL-2")
      (fields (field (name "Manufacturer") "Infineon(英飞凌)"))
      (libsource (lib "easyedapro") (part "BSZ040N06LS5ATMA1"))
    )
    (comp (ref "Q41")
      (value "BSZ040N06LS5")
      (footprint "easyedapro:DFN-8_L3.3-W3.3-P0.65-BL-2")
      (fields (field (name "Manufacturer") "Infineon(英飞凌)"))
      (libsource (lib "easyedapro") (part "BSZ040N06LS5ATMA1"))
    )
    (comp (ref "Q42")
      (value "BSZ040N06LS5")
      (footprint "easyedapro:DFN-8_L3.3-W3.3-P0.65-BL-2")
      (fields (field (name "Manufacturer") "Infineon(英飞凌)"))
      (libsource (lib "easyedapro") (part "BSZ040N06LS5ATMA1"))
    )
    (comp (ref "Q43")
      (value "BSZ040N06LS5")
      (footprint "easyedapro:DFN-8_L3.3-W3.3-P0.65-BL-2")
      (fields (field (name "Manufacturer") "Infineon(英飞凌)"))
      (libsource (lib "easyedapro") (part "BSZ040N06LS5ATMA1"))
    )
    (comp (ref "Q44")
      (value "BSZ040N06LS5")
      (footprint "easyedapro:DFN-8_L3.3-W3.3-P0.65-BL-2")
      (fields (field (name "Manufacturer") "Infineon(英飞凌)"))
      (libsource (lib "easyedapro") (part "BSZ040N06LS5ATMA1"))
    )
    (comp (ref "Q45")
      (value "BSZ040N06LS5")
      (footprint "easyedapro:DFN-8_L3.3-W3.3-P0.65-BL-2")
      (fields (field (name "Manufacturer") "Infineon(英飞凌)"))
      (libsource (lib "easyedapro") (part "BSZ040N06LS5ATMA1"))
    )
    (comp (ref "Q46")
      (value "BSZ040N06LS5")
      (footprint "easyedapro:DFN-8_L3.3-W3.3-P0.65-BL-2")
      (fields (field (name "Manufacturer") "Infineon(英飞凌)"))
      (libsource (lib "easyedapro") (part "BSZ040N06LS5ATMA1"))
    )
    (comp (ref "Q47")
      (value "BSZ040N06LS5")
      (footprint "easyedapro:DFN-8_L3.3-W3.3-P0.65-BL-2")
      (fields (field (name "Manufacturer") "Infineon(英飞凌)"))
      (libsource (lib "easyedapro") (part "BSZ040N06LS5ATMA1"))
    )
    (comp (ref "Q48")
      (value "BSZ040N06LS5")
      (footprint "easyedapro:DFN-8_L3.3-W3.3-P0.65-BL-2")
      (fields (field (name "Manufacturer") "Infineon(英飞凌)"))
      (libsource (lib "easyedapro") (part "BSZ040N06LS5ATMA1"))
    )
    (comp (ref "R69")
      (value "10Ω")
      (footprint "easyedapro:R0603")
      (fields
        (field (name "Manufacturer Part") "RC0603FR-0710RL")
        (field (name "Manufacturer") "YAGEO(国巨)")
        (field (name "Tolerance") "±1%")
      )
      (libsource (lib "easyedapro") (part "RC0603FR-0710RL"))
    )
    (comp (ref "R70")
      (value "10Ω")
      (footprint "easyedapro:R0603")
      (fields
        (field (name "Manufacturer Part") "RC0603FR-0710RL")
        (field (name "Manufacturer") "YAGEO(国巨)")
        (field (name "Tolerance") "±1%")
      )
      (libsource (lib "easyedapro") (part "RC0603FR-0710RL"))
    )
    (comp (ref "R71")
      (value "10Ω")
      (footprint "easyedapro:R0603")
      (fields
        (field (name "Manufacturer Part") "RC0603FR-0710RL")
        (field (name "Manufacturer") "YAGEO(国巨)")
        (field (name "Tolerance") "±1%")
      )
      (libsource (lib "easyedapro") (part "RC0603FR-0710RL"))
    )
    (comp (ref "R72")
      (value "10Ω")
      (footprint "easyedapro:R0603")
      (fields
        (field (name "Manufacturer Part") "RC0603FR-0710RL")
        (field (name "Manufacturer") "YAGEO(国巨)")
        (field (name "Tolerance") "±1%")
      )
      (libsource (lib "easyedapro") (part "RC0603FR-0710RL"))
    )
    (comp (ref "R73")
      (value "10Ω")
      (footprint "easyedapro:R0603")
      (fields
        (field (name "Manufacturer Part") "RC0603FR-0710RL")
        (field (name "Manufacturer") "YAGEO(国巨)")
        (field (name "Tolerance") "±1%")
      )
      (libsource (lib "easyedapro") (part "RC0603FR-0710RL"))
    )
    (comp (ref "R74")
      (value "10Ω")
      (footprint "easyedapro:R0603")
      (fields
        (field (name "Manufacturer Part") "RC0603FR-0710RL")
        (field (name "Manufacturer") "YAGEO(国巨)")
        (field (name "Tolerance") "±1%")
      )
      (libsource (lib "easyedapro") (part "RC0603FR-0710RL"))
    )
    (comp (ref "R75")
      (value "10Ω")
      (footprint "easyedapro:R0603")
      (fields
        (field (name "Manufacturer Part") "RC0603FR-0710RL")
        (field (name "Manufacturer") "YAGEO(国巨)")
        (field (name "Tolerance") "±1%")
      )
      (libsource (lib "easyedapro") (part "RC0603FR-0710RL"))
    )
    (comp (ref "R76")
      (value "10Ω")
      (footprint "easyedapro:R0603")
      (fields
        (field (name "Manufacturer Part") "RC0603FR-0710RL")
        (field (name "Manufacturer") "YAGEO(国巨)")
        (field (name "Tolerance") "±1%")
      )
      (libsource (lib "easyedapro") (part "RC0603FR-0710RL"))
    )
    (comp (ref "R77")
      (value "10Ω")
      (footprint "easyedapro:R0603")
      (fields
        (field (name "Manufacturer Part") "RC0603FR-0710RL")
        (field (name "Manufacturer") "YAGEO(国巨)")
        (field (name "Tolerance") "±1%")
      )
      (libsource (lib "easyedapro") (part "RC0603FR-0710RL"))
    )
    (comp (ref "R78")
      (value "10Ω")
      (footprint "easyedapro:R0603")
      (fields
        (field (name "Manufacturer Part") "RC0603FR-0710RL")
        (field (name "Manufacturer") "YAGEO(国巨)")
        (field (name "Tolerance") "±1%")
      )
      (libsource (lib "easyedapro") (part "RC0603FR-0710RL"))
    )
    (comp (ref "R79")
      (value "10Ω")
      (footprint "easyedapro:R0603")
      (fields
        (field (name "Manufacturer Part") "RC0603FR-0710RL")
        (field (name "Manufacturer") "YAGEO(国巨)")
        (field (name "Tolerance") "±1%")
      )
      (libsource (lib "easyedapro") (part "RC0603FR-0710RL"))
    )
    (comp (ref "R80")
      (value "10Ω")
      (footprint "easyedapro:R0603")
      (fields
        (field (name "Manufacturer Part") "RC0603FR-0710RL")
        (field (name "Manufacturer") "YAGEO(国巨)")
        (field (name "Tolerance") "±1%")
      )
      (libsource (lib "easyedapro") (part "RC0603FR-0710RL"))
    )
    (comp (ref "R81")
      (value "10Ω")
      (footprint "easyedapro:R0603")
      (fields
        (field (name "Manufacturer Part") "RC0603FR-0710RL")
        (field (name "Manufacturer") "YAGEO(国巨)")
        (field (name "Tolerance") "±1%")
      )
      (libsource (lib "easyedapro") (part "RC0603FR-0710RL"))
    )
    (comp (ref "R82")
      (value "10Ω")
      (footprint "easyedapro:R0603")
      (fields
        (field (name "Manufacturer Part") "RC0603FR-0710RL")
        (field (name "Manufacturer") "YAGEO(国巨)")
        (field (name "Tolerance") "±1%")
      )
      (libsource (lib "easyedapro") (part "RC0603FR-0710RL"))
    )
    (comp (ref "R83")
      (value "10Ω")
      (footprint "easyedapro:R0603")
      (fields
        (field (name "Manufacturer Part") "RC0603FR-0710RL")
        (field (name "Manufacturer") "YAGEO(国巨)")
        (field (name "Tolerance") "±1%")
      )
      (libsource (lib "easyedapro") (part "RC0603FR-0710RL"))
    )
    (comp (ref "R84")
      (value "10Ω")
      (footprint "easyedapro:R0603")
      (fields
        (field (name "Manufacturer Part") "RC0603FR-0710RL")
        (field (name "Manufacturer") "YAGEO(国巨)")
        (field (name "Tolerance") "±1%")
      )
      (libsource (lib "easyedapro") (part "RC0603FR-0710RL"))
    )
    (comp (ref "R85")
      (value "10Ω")
      (footprint "easyedapro:R0603")
      (fields
        (field (name "Manufacturer Part") "RC0603FR-0710RL")
        (field (name "Manufacturer") "YAGEO(国巨)")
        (field (name "Tolerance") "±1%")
      )
      (libsource (lib "easyedapro") (part "RC0603FR-0710RL"))
    )
    (comp (ref "R86")
      (value "10Ω")
      (footprint "easyedapro:R0603")
      (fields
        (field (name "Manufacturer Part") "RC0603FR-0710RL")
        (field (name "Manufacturer") "YAGEO(国巨)")
        (field (name "Tolerance") "±1%")
      )
      (libsource (lib "easyedapro") (part "RC0603FR-0710RL"))
    )
    (comp (ref "R87")
      (value "10Ω")
      (footprint "easyedapro:R0603")
      (fields
        (field (name "Manufacturer Part") "RC0603FR-0710RL")
        (field (name "Manufacturer") "YAGEO(国巨)")
        (field (name "Tolerance") "±1%")
      )
      (libsource (lib "easyedapro") (part "RC0603FR-0710RL"))
    )
    (comp (ref "R88")
      (value "10Ω")
      (footprint "easyedapro:R0603")
      (fields
        (field (name "Manufacturer Part") "RC0603FR-0710RL")
        (field (name "Manufacturer") "YAGEO(国巨)")
        (field (name "Tolerance") "±1%")
      )
      (libsource (lib "easyedapro") (part "RC0603FR-0710RL"))
    )
    (comp (ref "R89")
      (value "10Ω")
      (footprint "easyedapro:R0603")
      (fields
        (field (name "Manufacturer Part") "RC0603FR-0710RL")
        (field (name "Manufacturer") "YAGEO(国巨)")
        (field (name "Tolerance") "±1%")
      )
      (libsource (lib "easyedapro") (part "RC0603FR-0710RL"))
    )
    (comp (ref "R90")
      (value "10Ω")
      (footprint "easyedapro:R0603")
      (fields
        (field (name "Manufacturer Part") "RC0603FR-0710RL")
        (field (name "Manufacturer") "YAGEO(国巨)")
        (field (name "Tolerance") "±1%")
      )
      (libsource (lib "easyedapro") (part "RC0603FR-0710RL"))
    )
    (comp (ref "R91")
      (value "10Ω")
      (footprint "easyedapro:R0603")
      (fields
        (field (name "Manufacturer Part") "RC0603FR-0710RL")
        (field (name "Manufacturer") "YAGEO(国巨)")
        (field (name "Tolerance") "±1%")
      )
      (libsource (lib "easyedapro") (part "RC0603FR-0710RL"))
    )
    (comp (ref "R92")
      (value "10Ω")
      (footprint "easyedapro:R0603")
      (fields
        (field (name "Manufacturer Part") "RC0603FR-0710RL")
        (field (name "Manufacturer") "YAGEO(国巨)")
        (field (name "Tolerance") "±1%")
      )
      (libsource (lib "easyedapro") (part "RC0603FR-0710RL"))
    )
    (comp (ref "C40")
      (value "10uF")
      (description "Capacitance:10uF Tolerance:±10% Tolerance:±10% Voltage Rating:50V Temperature Coefficient:X5R")
      (fields
        (field (name "Manufacturer Part") "CL31A106KBHNNNE")
        (field (name "Manufacturer") "SAMSUNG(三星)")
      )
      (libsource (lib "easyedapro") (part "CAP"))
    )
    (comp (ref "C41")
      (value "22uF")
      (description "Capacitance:22uF Tolerance:±20% Tolerance:±20% Voltage Rating:6.3V Temperature Coefficient:X5R")
      (fields
        (field (name "Manufacturer Part") "GRM155R60J226ME11D")
        (field (name "Manufacturer") "muRata(村田)")
      )
      (libsource (lib "easyedapro") (part "CAP"))
    )
    (comp (ref "C42")
      (value "10uF")
      (description "Capacitance:10uF Tolerance:±10% Tolerance:±10% Voltage Rating:50V Temperature Coefficient:X5R")
      (fields
        (field (name "Manufacturer Part") "CL31A106KBHNNNE")
        (field (name "Manufacturer") "SAMSUNG(三星)")
      )
      (libsource (lib "easyedapro") (part "CAP"))
    )
    (comp (ref "C43")
      (value "10uF")
      (description "Capacitance:10uF Tolerance:±10% Tolerance:±10% Voltage Rating:50V Temperature Coefficient:X5R")
      (fields
        (field (name "Manufacturer Part") "CL31A106KBHNNNE")
        (field (name "Manufacturer") "SAMSUNG(三星)")
      )
      (libsource (lib "easyedapro") (part "CAP"))
    )
    (comp (ref "C44")
      (value "10uF")
      (description "Capacitance:10uF Tolerance:±10% Tolerance:±10% Voltage Rating:50V Temperature Coefficient:X5R")
      (fields
        (field (name "Manufacturer Part") "CL31A106KBHNNNE")
        (field (name "Manufacturer") "SAMSUNG(三星)")
      )
      (libsource (lib "easyedapro") (part "CAP"))
    )
    (comp (ref "C45")
      (value "10uF")
      (description "Capacitance:10uF Tolerance:±10% Tolerance:±10% Voltage Rating:50V Temperature Coefficient:X5R")
      (fields
        (field (name "Manufacturer Part") "CL31A106KBHNNNE")
        (field (name "Manufacturer") "SAMSUNG(三星)")
      )
      (libsource (lib "easyedapro") (part "CAP"))
    )
    (comp (ref "C46")
      (value "10uF")
      (description "Capacitance:10uF Tolerance:±10% Tolerance:±10% Voltage Rating:50V Temperature Coefficient:X5R")
      (fields
        (field (name "Manufacturer Part") "CL31A106KBHNNNE")
        (field (name "Manufacturer") "SAMSUNG(三星)")
      )
      (libsource (lib "easyedapro") (part "CAP"))
    )
    (comp (ref "C47")
      (value "10uF")
      (description "Capacitance:10uF Tolerance:±10% Tolerance:±10% Voltage Rating:50V Temperature Coefficient:X5R")
      (fields
        (field (name "Manufacturer Part") "CL31A106KBHNNNE")
        (field (name "Manufacturer") "SAMSUNG(三星)")
      )
      (libsource (lib "easyedapro") (part "CAP"))
    )
    (comp (ref "C48")
      (value "10uF")
      (description "Capacitance:10uF Tolerance:±10% Tolerance:±10% Voltage Rating:50V Temperature Coefficient:X5R")
      (fields
        (field (name "Manufacturer Part") "CL31A106KBHNNNE")
        (field (name "Manufacturer") "SAMSUNG(三星)")
      )
      (libsource (lib "easyedapro") (part "CAP"))
    )
    (comp (ref "C49")
      (value "10uF")
      (description "Capacitance:10uF Tolerance:±10% Tolerance:±10% Voltage Rating:50V Temperature Coefficient:X5R")
      (fields
        (field (name "Manufacturer Part") "CL31A106KBHNNNE")
        (field (name "Manufacturer") "SAMSUNG(三星)")
      )
      (libsource (lib "easyedapro") (part "CAP"))
    )
    (comp (ref "C50")
      (value "10uF")
      (description "Capacitance:10uF Tolerance:±10% Tolerance:±10% Voltage Rating:50V Temperature Coefficient:X5R")
      (fields
        (field (name "Manufacturer Part") "CL31A106KBHNNNE")
        (field (name "Manufacturer") "SAMSUNG(三星)")
      )
      (libsource (lib "easyedapro") (part "CAP"))
    )
    (comp (ref "C51")
      (value "10uF")
      (description "Capacitance:10uF Tolerance:±10% Tolerance:±10% Voltage Rating:50V Temperature Coefficient:X5R")
      (fields
        (field (name "Manufacturer Part") "CL31A106KBHNNNE")
        (field (name "Manufacturer") "SAMSUNG(三星)")
      )
      (libsource (lib "easyedapro") (part "CAP"))
    )
    (comp (ref "C52")
      (value "10uF")
      (description "Capacitance:10uF Tolerance:±10% Tolerance:±10% Voltage Rating:50V Temperature Coefficient:X5R")
      (fields
        (field (name "Manufacturer Part") "CL31A106KBHNNNE")
        (field (name "Manufacturer") "SAMSUNG(三星)")
      )
      (libsource (lib "easyedapro") (part "CAP"))
    )
    (comp (ref "C53")
      (value "10uF")
      (description "Capacitance:10uF Tolerance:±10% Tolerance:±10% Voltage Rating:50V Temperature Coefficient:X5R")
      (fields
        (field (name "Manufacturer Part") "CL31A106KBHNNNE")
        (field (name "Manufacturer") "SAMSUNG(三星)")
      )
      (libsource (lib "easyedapro") (part "CAP"))
    )
    (comp (ref "C54")
      (value "10uF")
      (description "Capacitance:10uF Tolerance:±10% Tolerance:±10% Voltage Rating:50V Temperature Coefficient:X5R")
      (fields
        (field (name "Manufacturer Part") "CL31A106KBHNNNE")
        (field (name "Manufacturer") "SAMSUNG(三星)")
      )
      (libsource (lib "easyedapro") (part "CAP"))
    )
    (comp (ref "C55")
      (value "10uF")
      (description "Capacitance:10uF Tolerance:±10% Tolerance:±10% Voltage Rating:50V Temperature Coefficient:X5R")
      (fields
        (field (name "Manufacturer Part") "CL31A106KBHNNNE")
        (field (name "Manufacturer") "SAMSUNG(三星)")
      )
      (libsource (lib "easyedapro") (part "CAP"))
    )
    (comp (ref "C56")
      (value "10uF")
      (description "Capacitance:10uF Tolerance:±10% Tolerance:±10% Voltage Rating:50V Temperature Coefficient:X5R")
      (fields
        (field (name "Manufacturer Part") "CL31A106KBHNNNE")
        (field (name "Manufacturer") "SAMSUNG(三星)")
      )
      (libsource (lib "easyedapro") (part "CAP"))
    )
    (comp (ref "C57")
      (value "10uF")
      (description "Capacitance:10uF Tolerance:±10% Tolerance:±10% Voltage Rating:50V Temperature Coefficient:X5R")
      (fields
        (field (name "Manufacturer Part") "CL31A106KBHNNNE")
        (field (name "Manufacturer") "SAMSUNG(三星)")
      )
      (libsource (lib "easyedapro") (part "CAP"))
    )
    (comp (ref "C58")
      (value "10uF")
      (description "Capacitance:10uF Tolerance:±10% Tolerance:±10% Voltage Rating:50V Temperature Coefficient:X5R")
      (fields
        (field (name "Manufacturer Part") "CL31A106KBHNNNE")
        (field (name "Manufacturer") "SAMSUNG(三星)")
      )
      (libsource (lib "easyedapro") (part "CAP"))
    )
    (comp (ref "C59")
      (value "10uF")
      (description "Capacitance:10uF Tolerance:±10% Tolerance:±10% Voltage Rating:50V Temperature Coefficient:X5R")
      (fields
        (field (name "Manufacturer Part") "CL31A106KBHNNNE")
        (field (name "Manufacturer") "SAMSUNG(三星)")
      )
      (libsource (lib "easyedapro") (part "CAP"))
    )
    (comp (ref "C60")
      (value "10uF")
      (description "Capacitance:10uF Tolerance:±10% Tolerance:±10% Voltage Rating:50V Temperature Coefficient:X5R")
      (fields
        (field (name "Manufacturer Part") "CL31A106KBHNNNE")
        (field (name "Manufacturer") "SAMSUNG(三星)")
      )
      (libsource (lib "easyedapro") (part "CAP"))
    )
    (comp (ref "C61")
      (value "10uF")
      (description "Capacitance:10uF Tolerance:±10% Tolerance:±10% Voltage Rating:50V Temperature Coefficient:X5R")
      (fields
        (field (name "Manufacturer Part") "CL31A106KBHNNNE")
        (field (name "Manufacturer") "SAMSUNG(三星)")
      )
      (libsource (lib "easyedapro") (part "CAP"))
    )
    (comp (ref "C145")
      (value "10nF")
      (description "Capacitance:10nF Tolerance:±10% Tolerance:±10% Voltage Rating:50V Temperature Coefficient:X7R")
      (fields
        (field (name "Manufacturer Part") "CC0402KRX7R9BB103")
        (field (name "Manufacturer") "YAGEO(国巨)")
      )
      (libsource (lib "easyedapro") (part "CAP"))
    )
    (comp (ref "C146")
      (value "10nF")
      (description "Capacitance:10nF Tolerance:±10% Tolerance:±10% Voltage Rating:50V Temperature Coefficient:X7R")
      (fields
        (field (name "Manufacturer Part") "CC0402KRX7R9BB103")
        (field (name "Manufacturer") "YAGEO(国巨)")
      )
      (libsource (lib "easyedapro") (part "CAP"))
    )
    (comp (ref "C147")
      (value "10nF")
      (description "Capacitance:10nF Tolerance:±10% Tolerance:±10% Voltage Rating:50V Temperature Coefficient:X7R")
      (fields
        (field (name "Manufacturer Part") "CC0402KRX7R9BB103")
        (field (name "Manufacturer") "YAGEO(国巨)")
      )
      (libsource (lib "easyedapro") (part "CAP"))
    )
    (comp (ref "C148")
      (value "10nF")
      (description "Capacitance:10nF Tolerance:±10% Tolerance:±10% Voltage Rating:50V Temperature Coefficient:X7R")
      (fields
        (field (name "Manufacturer Part") "CC0402KRX7R9BB103")
        (field (name "Manufacturer") "YAGEO(国巨)")
      )
      (libsource (lib "easyedapro") (part "CAP"))
    )
    (comp (ref "C149")
      (value "10nF")
      (description "Capacitance:10nF Tolerance:±10% Tolerance:±10% Voltage Rating:50V Temperature Coefficient:X7R")
      (fields
        (field (name "Manufacturer Part") "CC0402KRX7R9BB103")
        (field (name "Manufacturer") "YAGEO(国巨)")
      )
      (libsource (lib "easyedapro") (part "CAP"))
    )
    (comp (ref "C150")
      (value "10nF")
      (description "Capacitance:10nF Tolerance:±10% Tolerance:±10% Voltage Rating:50V Temperature Coefficient:X7R")
      (fields
        (field (name "Manufacturer Part") "CC0402KRX7R9BB103")
        (field (name "Manufacturer") "YAGEO(国巨)")
      )
      (libsource (lib "easyedapro") (part "CAP"))
    )
    (comp (ref "C151")
      (value "10nF")
      (description "Capacitance:10nF Tolerance:±10% Tolerance:±10% Voltage Rating:50V Temperature Coefficient:X7R")
      (fields
        (field (name "Manufacturer Part") "CC0402KRX7R9BB103")
        (field (name "Manufacturer") "YAGEO(国巨)")
      )
      (libsource (lib "easyedapro") (part "CAP"))
    )
    (comp (ref "C152")
      (value "10nF")
      (description "Capacitance:10nF Tolerance:±10% Tolerance:±10% Voltage Rating:50V Temperature Coefficient:X7R")
      (fields
        (field (name "Manufacturer Part") "CC0402KRX7R9BB103")
        (field (name "Manufacturer") "YAGEO(国巨)")
      )
      (libsource (lib "easyedapro") (part "CAP"))
    )
    (comp (ref "C153")
      (value "10nF")
      (description "Capacitance:10nF Tolerance:±10% Tolerance:±10% Voltage Rating:50V Temperature Coefficient:X7R")
      (fields
        (field (name "Manufacturer Part") "CC0402KRX7R9BB103")
        (field (name "Manufacturer") "YAGEO(国巨)")
      )
      (libsource (lib "easyedapro") (part "CAP"))
    )
    (comp (ref "C154")
      (value "10nF")
      (description "Capacitance:10nF Tolerance:±10% Tolerance:±10% Voltage Rating:50V Temperature Coefficient:X7R")
      (fields
        (field (name "Manufacturer Part") "CC0402KRX7R9BB103")
        (field (name "Manufacturer") "YAGEO(国巨)")
      )
      (libsource (lib "easyedapro") (part "CAP"))
    )
    (comp (ref "C155")
      (value "10nF")
      (description "Capacitance:10nF Tolerance:±10% Tolerance:±10% Voltage Rating:50V Temperature Coefficient:X7R")
      (fields
        (field (name "Manufacturer Part") "CC0402KRX7R9BB103")
        (field (name "Manufacturer") "YAGEO(国巨)")
      )
      (libsource (lib "easyedapro") (part "CAP"))
    )
    (comp (ref "C156")
      (value "10nF")
      (description "Capacitance:10nF Tolerance:±10% Tolerance:±10% Voltage Rating:50V Temperature Coefficient:X7R")
      (fields
        (field (name "Manufacturer Part") "CC0402KRX7R9BB103")
        (field (name "Manufacturer") "YAGEO(国巨)")
      )
      (libsource (lib "easyedapro") (part "CAP"))
    )
    (comp (ref "C157")
      (value "2.2uF")
      (footprint "easyedapro:CAP-SMD_BD4.0-L4.3-W4.3-FD")
      (fields
        (field (name "Manufacturer Part") "RVT1H2R2M0405 2.2UF 50V")
        (field (name "Manufacturer") "DMBJ(振宝佳)")
        (field (name "Tolerance") "±20%")
      )
      (libsource (lib "easyedapro") (part "RVT1H2R2M0405 2.2UF 50V"))
    )
    (comp (ref "C158")
      (value "2.2nF")
      (footprint "easyedapro:C0402")
      (description "Capacitance:2.2nF Tolerance:±10% Tolerance:±10% Voltage Rating:50V Temperature Coefficient:X7R")
      (fields (field (name "Manufacturer Part") "0402B222K500NT") (field (name "Manufacturer") "FH(风华)"))
      (libsource (lib "easyedapro") (part "0402B222K500NT"))
    )
    (comp (ref "C159")
      (value "3.3nF")
      (footprint "easyedapro:C0402")
      (description "Capacitance:3.3nF Tolerance:±10% Tolerance:±10% Voltage Rating:50V Temperature Coefficient:X7R")
      (fields
        (field (name "Manufacturer Part") "TCC0402X7R332K500AT")
        (field (name "Manufacturer") "CCTC(三环)")
      )
      (libsource (lib "easyedapro") (part "TCC0402X7R332K500AT"))
    )
    (comp (ref "C160")
      (value "56pF")
      (footprint "easyedapro:C0603")
      (description "Capacitance:56pF Tolerance:±5% Tolerance:±5% Voltage Rating:50V Temperature Coefficient:NP0")
      (fields
        (field (name "Manufacturer Part") "CC0603JRNPO9BN560")
        (field (name "Manufacturer") "YAGEO(国巨)")
      )
      (libsource (lib "easyedapro") (part "CC0603JRNPO9BN560"))
    )
    (comp (ref "C161")
      (value "47uF")
      (footprint "easyedapro:C1206")
      (description "Capacitance:47uF Tolerance:±20% Tolerance:±20% Voltage Rating:10V Temperature Coefficient:X5R")
      (fields
        (field (name "Manufacturer Part") "CL31A476MPHNNNE")
        (field (name "Manufacturer") "SAMSUNG(三星)")
      )
      (libsource (lib "easyedapro") (part "CL31A476MPHNNNE"))
    )
    (comp (ref "C186")
      (value "10uF")
      (description "Capacitance:10uF Tolerance:±10% Tolerance:±10% Voltage Rating:50V Temperature Coefficient:X5R")
      (fields
        (field (name "Manufacturer Part") "CL31A106KBHNNNE")
        (field (name "Manufacturer") "SAMSUNG(三星)")
      )
      (libsource (lib "easyedapro") (part "CAP"))
    )
    (comp (ref "C187")
      (value "10uF")
      (description "Capacitance:10uF Tolerance:±10% Tolerance:±10% Voltage Rating:50V Temperature Coefficient:X5R")
      (fields
        (field (name "Manufacturer Part") "CL31A106KBHNNNE")
        (field (name "Manufacturer") "SAMSUNG(三星)")
      )
      (libsource (lib "easyedapro") (part "CAP"))
    )
    (comp (ref "C188")
      (value "10uF")
      (description "Capacitance:10uF Tolerance:±10% Tolerance:±10% Voltage Rating:50V Temperature Coefficient:X5R")
      (fields
        (field (name "Manufacturer Part") "CL31A106KBHNNNE")
        (field (name "Manufacturer") "SAMSUNG(三星)")
      )
      (libsource (lib "easyedapro") (part "CAP"))
    )
    (comp (ref "C189")
      (value "10uF")
      (description "Capacitance:10uF Tolerance:±10% Tolerance:±10% Voltage Rating:50V Temperature Coefficient:X5R")
      (fields
        (field (name "Manufacturer Part") "CL31A106KBHNNNE")
        (field (name "Manufacturer") "SAMSUNG(三星)")
      )
      (libsource (lib "easyedapro") (part "CAP"))
    )
    (comp (ref "D26")
      (value "BAT54WS")
      (footprint "easyedapro:SOD-323_L1.7-W1.3-LS2.6-RD-1")
      (fields (field (name "Manufacturer") "High Diode(海德)"))
      (libsource (lib "easyedapro") (part "BAT54WS_C466657"))
    )
    (comp (ref "D27")
      (value "BAT54WS")
      (footprint "easyedapro:SOD-323_L1.7-W1.3-LS2.6-RD-1")
      (fields (field (name "Manufacturer") "High Diode(海德)"))
      (libsource (lib "easyedapro") (part "BAT54WS_C466657"))
    )
    (comp (ref "D28")
      (value "BAT54WS")
      (footprint "easyedapro:SOD-323_L1.7-W1.3-LS2.6-RD-1")
      (fields (field (name "Manufacturer") "High Diode(海德)"))
      (libsource (lib "easyedapro") (part "BAT54WS_C466657"))
    )
    (comp (ref "D29")
      (value "BAT54WS")
      (footprint "easyedapro:SOD-323_L1.7-W1.3-LS2.6-RD-1")
      (fields (field (name "Manufacturer") "High Diode(海德)"))
      (libsource (lib "easyedapro") (part "BAT54WS_C466657"))
    )
    (comp (ref "D30")
      (value "BAT54WS")
      (footprint "easyedapro:SOD-323_L1.7-W1.3-LS2.6-RD-1")
      (fields (field (name "Manufacturer") "High Diode(海德)"))
      (libsource (lib "easyedapro") (part "BAT54WS_C466657"))
    )
    (comp (ref "D31")
      (value "BAT54WS")
      (footprint "easyedapro:SOD-323_L1.7-W1.3-LS2.6-RD-1")
      (fields (field (name "Manufacturer") "High Diode(海德)"))
      (libsource (lib "easyedapro") (part "BAT54WS_C466657"))
    )
    (comp (ref "D32")
      (value "BAT54WS")
      (footprint "easyedapro:SOD-323_L1.7-W1.3-LS2.6-RD-1")
      (fields (field (name "Manufacturer") "High Diode(海德)"))
      (libsource (lib "easyedapro") (part "BAT54WS_C466657"))
    )
    (comp (ref "D33")
      (value "BAT54WS")
      (footprint "easyedapro:SOD-323_L1.7-W1.3-LS2.6-RD-1")
      (fields (field (name "Manufacturer") "High Diode(海德)"))
      (libsource (lib "easyedapro") (part "BAT54WS_C466657"))
    )
    (comp (ref "D34")
      (value "BAT54WS")
      (footprint "easyedapro:SOD-323_L1.7-W1.3-LS2.6-RD-1")
      (fields (field (name "Manufacturer") "High Diode(海德)"))
      (libsource (lib "easyedapro") (part "BAT54WS_C466657"))
    )
    (comp (ref "D35")
      (value "BAT54WS")
      (footprint "easyedapro:SOD-323_L1.7-W1.3-LS2.6-RD-1")
      (fields (field (name "Manufacturer") "High Diode(海德)"))
      (libsource (lib "easyedapro") (part "BAT54WS_C466657"))
    )
    (comp (ref "D36")
      (value "BAT54WS")
      (footprint "easyedapro:SOD-323_L1.7-W1.3-LS2.6-RD-1")
      (fields (field (name "Manufacturer") "High Diode(海德)"))
      (libsource (lib "easyedapro") (part "BAT54WS_C466657"))
    )
    (comp (ref "D37")
      (value "BAT54WS")
      (footprint "easyedapro:SOD-323_L1.7-W1.3-LS2.6-RD-1")
      (fields (field (name "Manufacturer") "High Diode(海德)"))
      (libsource (lib "easyedapro") (part "BAT54WS_C466657"))
    )
    (comp (ref "L1")
      (value "68uH")
      (footprint "easyedapro:IND-SMD_L7.8-W7.0_SUMIDA_CD73")
      (fields
        (field (name "Manufacturer Part") "CY75-68UH")
        (field (name "Manufacturer") "SHOU HAN(首韩)")
        (field (name "Tolerance") "±10%")
      )
      (libsource (lib "easyedapro") (part "CY75-68UH"))
    )
    (comp (ref "R29")
      (value "10kΩ")
      (fields
        (field (name "Manufacturer Part") "0402WGF1002TCE")
        (field (name "Manufacturer") "UNI-ROYAL(厚声)")
      )
      (libsource (lib "easyedapro") (part "Res"))
    )
    (comp (ref "R30")
      (value "10kΩ")
      (fields
        (field (name "Manufacturer Part") "0402WGF1002TCE")
        (field (name "Manufacturer") "UNI-ROYAL(厚声)")
      )
      (libsource (lib "easyedapro") (part "Res"))
    )
    (comp (ref "R31")
      (value "10kΩ")
      (fields
        (field (name "Manufacturer Part") "0402WGF1002TCE")
        (field (name "Manufacturer") "UNI-ROYAL(厚声)")
      )
      (libsource (lib "easyedapro") (part "Res"))
    )
    (comp (ref "R32")
      (value "10kΩ")
      (fields
        (field (name "Manufacturer Part") "0402WGF1002TCE")
        (field (name "Manufacturer") "UNI-ROYAL(厚声)")
      )
      (libsource (lib "easyedapro") (part "Res"))
    )
    (comp (ref "R33")
      (value "10kΩ")
      (fields
        (field (name "Manufacturer Part") "0402WGF1002TCE")
        (field (name "Manufacturer") "UNI-ROYAL(厚声)")
      )
      (libsource (lib "easyedapro") (part "Res"))
    )
    (comp (ref "R34")
      (value "10kΩ")
      (fields
        (field (name "Manufacturer Part") "0402WGF1002TCE")
        (field (name "Manufacturer") "UNI-ROYAL(厚声)")
      )
      (libsource (lib "easyedapro") (part "Res"))
    )
    (comp (ref "R35")
      (value "1kΩ")
      (fields
        (field (name "Manufacturer Part") "0402WGF1001TCE")
        (field (name "Manufacturer") "UNI-ROYAL(厚声)")
      )
      (libsource (lib "easyedapro") (part "Res"))
    )
    (comp (ref "R36")
      (value "1kΩ")
      (fields
        (field (name "Manufacturer Part") "0402WGF1001TCE")
        (field (name "Manufacturer") "UNI-ROYAL(厚声)")
      )
      (libsource (lib "easyedapro") (part "Res"))
    )
    (comp (ref "R37")
      (value "1kΩ")
      (fields
        (field (name "Manufacturer Part") "0402WGF1001TCE")
        (field (name "Manufacturer") "UNI-ROYAL(厚声)")
      )
      (libsource (lib "easyedapro") (part "Res"))
    )
    (comp (ref "R38")
      (value "10kΩ")
      (fields
        (field (name "Manufacturer Part") "0402WGF1002TCE")
        (field (name "Manufacturer") "UNI-ROYAL(厚声)")
      )
      (libsource (lib "easyedapro") (part "Res"))
    )
    (comp (ref "R39")
      (value "10kΩ")
      (fields
        (field (name "Manufacturer Part") "0402WGF1002TCE")
        (field (name "Manufacturer") "UNI-ROYAL(厚声)")
      )
      (libsource (lib "easyedapro") (part "Res"))
    )
    (comp (ref "R40")
      (value "10kΩ")
      (fields
        (field (name "Manufacturer Part") "0402WGF1002TCE")
        (field (name "Manufacturer") "UNI-ROYAL(厚声)")
      )
      (libsource (lib "easyedapro") (part "Res"))
    )
    (comp (ref "R41")
      (value "10kΩ")
      (fields
        (field (name "Manufacturer Part") "0402WGF1002TCE")
        (field (name "Manufacturer") "UNI-ROYAL(厚声)")
      )
      (libsource (lib "easyedapro") (part "Res"))
    )
    (comp (ref "R42")
      (value "10kΩ")
      (fields
        (field (name "Manufacturer Part") "0402WGF1002TCE")
        (field (name "Manufacturer") "UNI-ROYAL(厚声)")
      )
      (libsource (lib "easyedapro") (part "Res"))
    )
    (comp (ref "R43")
      (value "10kΩ")
      (fields
        (field (name "Manufacturer Part") "0402WGF1002TCE")
        (field (name "Manufacturer") "UNI-ROYAL(厚声)")
      )
      (libsource (lib "easyedapro") (part "Res"))
    )
    (comp (ref "R44")
      (value "1kΩ")
      (fields
        (field (name "Manufacturer Part") "0402WGF1001TCE")
        (field (name "Manufacturer") "UNI-ROYAL(厚声)")
      )
      (libsource (lib "easyedapro") (part "Res"))
    )
    (comp (ref "R45")
      (value "1kΩ")
      (fields
        (field (name "Manufacturer Part") "0402WGF1001TCE")
        (field (name "Manufacturer") "UNI-ROYAL(厚声)")
      )
      (libsource (lib "easyedapro") (part "Res"))
    )
    (comp (ref "R46")
      (value "1kΩ")
      (fields
        (field (name "Manufacturer Part") "0402WGF1001TCE")
        (field (name "Manufacturer") "UNI-ROYAL(厚声)")
      )
      (libsource (lib "easyedapro") (part "Res"))
    )
    (comp (ref "R47")
      (value "10kΩ")
      (fields
        (field (name "Manufacturer Part") "0402WGF1002TCE")
        (field (name "Manufacturer") "UNI-ROYAL(厚声)")
      )
      (libsource (lib "easyedapro") (part "Res"))
    )
    (comp (ref "R48")
      (value "10kΩ")
      (fields
        (field (name "Manufacturer Part") "0402WGF1002TCE")
        (field (name "Manufacturer") "UNI-ROYAL(厚声)")
      )
      (libsource (lib "easyedapro") (part "Res"))
    )
    (comp (ref "R49")
      (value "10kΩ")
      (fields
        (field (name "Manufacturer Part") "0402WGF1002TCE")
        (field (name "Manufacturer") "UNI-ROYAL(厚声)")
      )
      (libsource (lib "easyedapro") (part "Res"))
    )
    (comp (ref "R50")
      (value "10kΩ")
      (fields
        (field (name "Manufacturer Part") "0402WGF1002TCE")
        (field (name "Manufacturer") "UNI-ROYAL(厚声)")
      )
      (libsource (lib "easyedapro") (part "Res"))
    )
    (comp (ref "R51")
      (value "10kΩ")
      (fields
        (field (name "Manufacturer Part") "0402WGF1002TCE")
        (field (name "Manufacturer") "UNI-ROYAL(厚声)")
      )
      (libsource (lib "easyedapro") (part "Res"))
    )
    (comp (ref "R52")
      (value "10kΩ")
      (fields
        (field (name "Manufacturer Part") "0402WGF1002TCE")
        (field (name "Manufacturer") "UNI-ROYAL(厚声)")
      )
      (libsource (lib "easyedapro") (part "Res"))
    )
    (comp (ref "R53")
      (value "1kΩ")
      (fields
        (field (name "Manufacturer Part") "0402WGF1001TCE")
        (field (name "Manufacturer") "UNI-ROYAL(厚声)")
      )
      (libsource (lib "easyedapro") (part "Res"))
    )
    (comp (ref "R54")
      (value "1kΩ")
      (fields
        (field (name "Manufacturer Part") "0402WGF1001TCE")
        (field (name "Manufacturer") "UNI-ROYAL(厚声)")
      )
      (libsource (lib "easyedapro") (part "Res"))
    )
    (comp (ref "R55")
      (value "1kΩ")
      (fields
        (field (name "Manufacturer Part") "0402WGF1001TCE")
        (field (name "Manufacturer") "UNI-ROYAL(厚声)")
      )
      (libsource (lib "easyedapro") (part "Res"))
    )
    (comp (ref "R56")
      (value "10kΩ")
      (fields
        (field (name "Manufacturer Part") "0402WGF1002TCE")
        (field (name "Manufacturer") "UNI-ROYAL(厚声)")
      )
      (libsource (lib "easyedapro") (part "Res"))
    )
    (comp (ref "R57")
      (value "10kΩ")
      (fields
        (field (name "Manufacturer Part") "0402WGF1002TCE")
        (field (name "Manufacturer") "UNI-ROYAL(厚声)")
      )
      (libsource (lib "easyedapro") (part "Res"))
    )
    (comp (ref "R58")
      (value "10kΩ")
      (fields
        (field (name "Manufacturer Part") "0402WGF1002TCE")
        (field (name "Manufacturer") "UNI-ROYAL(厚声)")
      )
      (libsource (lib "easyedapro") (part "Res"))
    )
    (comp (ref "R59")
      (value "10kΩ")
      (fields
        (field (name "Manufacturer Part") "0402WGF1002TCE")
        (field (name "Manufacturer") "UNI-ROYAL(厚声)")
      )
      (libsource (lib "easyedapro") (part "Res"))
    )
    (comp (ref "R60")
      (value "10kΩ")
      (fields
        (field (name "Manufacturer Part") "0402WGF1002TCE")
        (field (name "Manufacturer") "UNI-ROYAL(厚声)")
      )
      (libsource (lib "easyedapro") (part "Res"))
    )
    (comp (ref "R61")
      (value "10kΩ")
      (fields
        (field (name "Manufacturer Part") "0402WGF1002TCE")
        (field (name "Manufacturer") "UNI-ROYAL(厚声)")
      )
      (libsource (lib "easyedapro") (part "Res"))
    )
    (comp (ref "R62")
      (value "1kΩ")
      (fields
        (field (name "Manufacturer Part") "0402WGF1001TCE")
        (field (name "Manufacturer") "UNI-ROYAL(厚声)")
      )
      (libsource (lib "easyedapro") (part "Res"))
    )
    (comp (ref "R63")
      (value "1kΩ")
      (fields
        (field (name "Manufacturer Part") "0402WGF1001TCE")
        (field (name "Manufacturer") "UNI-ROYAL(厚声)")
      )
      (libsource (lib "easyedapro") (part "Res"))
    )
    (comp (ref "R64")
      (value "1kΩ")
      (fields
        (field (name "Manufacturer Part") "0402WGF1001TCE")
        (field (name "Manufacturer") "UNI-ROYAL(厚声)")
      )
      (libsource (lib "easyedapro") (part "Res"))
    )
    (comp (ref "R65")
      (value "100kΩ")
      (footprint "easyedapro:R0603")
      (fields
        (field (name "Manufacturer Part") "0603WAF1003T5E")
        (field (name "Manufacturer") "UNI-ROYAL(厚声)")
        (field (name "Tolerance") "±1%")
      )
      (libsource (lib "easyedapro") (part "0603WAF1003T5E"))
    )
    (comp (ref "R66")
      (value "453kΩ")
      (footprint "easyedapro:R0402")
      (fields
        (field (name "Manufacturer Part") "0402WGF4533TCE")
        (field (name "Manufacturer") "UNI-ROYAL(厚声)")
        (field (name "Tolerance") "±1%")
      )
      (libsource (lib "easyedapro") (part "0402WGF4533TCE"))
    )
    (comp (ref "R67")
      (value "10.2kΩ")
      (footprint "easyedapro:R0603")
      (fields
        (field (name "Manufacturer Part") "RMC060310.2K1%N")
        (field (name "Manufacturer") "Tyohm(幸亚电阻)")
        (field (name "Tolerance") "±1%")
      )
      (libsource (lib "easyedapro") (part "RMC060310.2K1%N"))
    )
    (comp (ref "R68")
      (value "75kΩ")
      (footprint "easyedapro:R0603")
      (fields
        (field (name "Manufacturer Part") "0603WAF7502T5E")
        (field (name "Manufacturer") "UNI-ROYAL(厚声)")
        (field (name "Tolerance") "±1%")
      )
      (libsource (lib "easyedapro") (part "0603WAF7502T5E"))
    )
    (comp (ref "U10")
      (value "CJA1117B-3.3")
      (footprint "easyedapro:SOT-89-3_L4.5-W2.5-P1.50-LS4.2-BR")
      (fields (field (name "Manufacturer") "CJ(江苏长电/长晶)"))
      (libsource (lib "easyedapro") (part "CJA1117B-3.3"))
    )
    (comp (ref "U12")
      (value "LM5164QDDATQ1")
      (footprint "easyedapro:SOIC-8_L4.9-W3.9-P1.27-LS6.0-BL-EP2.9")
      (fields (field (name "Manufacturer") "TI(德州仪器)"))
      (libsource (lib "easyedapro") (part "LM5164QDDATQ1"))
    )
    (comp (ref "C121")
      (value "1uF")
      (description "Capacitance:1uF Tolerance:±10% Tolerance:±10% Voltage Rating:25V Temperature Coefficient:X5R")
      (fields
        (field (name "Manufacturer Part") "CL05A105KA5NQNC")
        (field (name "Manufacturer") "SAMSUNG(三星)")
      )
      (libsource (lib "easyedapro") (part "CAP"))
    )
    (comp (ref "C122")
      (value "1uF")
      (description "Capacitance:1uF Tolerance:±10% Tolerance:±10% Voltage Rating:25V Temperature Coefficient:X5R")
      (fields
        (field (name "Manufacturer Part") "CL05A105KA5NQNC")
        (field (name "Manufacturer") "SAMSUNG(三星)")
      )
      (libsource (lib "easyedapro") (part "CAP"))
    )
    (comp (ref "C123")
      (value "1uF")
      (description "Capacitance:1uF Tolerance:±10% Tolerance:±10% Voltage Rating:25V Temperature Coefficient:X5R")
      (fields
        (field (name "Manufacturer Part") "CL05A105KA5NQNC")
        (field (name "Manufacturer") "SAMSUNG(三星)")
      )
      (libsource (lib "easyedapro") (part "CAP"))
    )
    (comp (ref "C124")
      (value "100nF")
      (description "Capacitance:100nF Tolerance:±10% Tolerance:±10% Voltage Rating:16V Temperature Coefficient:X7R")
      (fields
        (field (name "Manufacturer Part") "CL05B104KO5NNNC")
        (field (name "Manufacturer") "SAMSUNG(三星)")
      )
      (libsource (lib "easyedapro") (part "CAP"))
    )
    (comp (ref "C125")
      (value "1uF")
      (description "Capacitance:1uF Tolerance:±10% Tolerance:±10% Voltage Rating:50V Temperature Coefficient:X5R")
      (fields
        (field (name "Manufacturer Part") "CL10A105KB8NNNC")
        (field (name "Manufacturer") "SAMSUNG(三星)")
      )
      (libsource (lib "easyedapro") (part "CAP"))
    )
    (comp (ref "C126")
      (value "10nF")
      (description "Capacitance:10nF Tolerance:±10% Tolerance:±10% Voltage Rating:50V Temperature Coefficient:X7R")
      (fields
        (field (name "Manufacturer Part") "CC0402KRX7R9BB103")
        (field (name "Manufacturer") "YAGEO(国巨)")
      )
      (libsource (lib "easyedapro") (part "CAP"))
    )
    (comp (ref "C127")
      (value "1uF")
      (description "Capacitance:1uF Tolerance:±10% Tolerance:±10% Voltage Rating:25V Temperature Coefficient:X5R")
      (fields
        (field (name "Manufacturer Part") "CL05A105KA5NQNC")
        (field (name "Manufacturer") "SAMSUNG(三星)")
      )
      (libsource (lib "easyedapro") (part "CAP"))
    )
    (comp (ref "C128")
      (value "1uF")
      (description "Capacitance:1uF Tolerance:±10% Tolerance:±10% Voltage Rating:25V Temperature Coefficient:X5R")
      (fields
        (field (name "Manufacturer Part") "CL05A105KA5NQNC")
        (field (name "Manufacturer") "SAMSUNG(三星)")
      )
      (libsource (lib "easyedapro") (part "CAP"))
    )
    (comp (ref "C129")
      (value "1uF")
      (description "Capacitance:1uF Tolerance:±10% Tolerance:±10% Voltage Rating:25V Temperature Coefficient:X5R")
      (fields
        (field (name "Manufacturer Part") "CL05A105KA5NQNC")
        (field (name "Manufacturer") "SAMSUNG(三星)")
      )
      (libsource (lib "easyedapro") (part "CAP"))
    )
    (comp (ref "C130")
      (value "100nF")
      (description "Capacitance:100nF Tolerance:±10% Tolerance:±10% Voltage Rating:16V Temperature Coefficient:X7R")
      (fields
        (field (name "Manufacturer Part") "CL05B104KO5NNNC")
        (field (name "Manufacturer") "SAMSUNG(三星)")
      )
      (libsource (lib "easyedapro") (part "CAP"))
    )
    (comp (ref "C131")
      (value "1uF")
      (description "Capacitance:1uF Tolerance:±10% Tolerance:±10% Voltage Rating:50V Temperature Coefficient:X5R")
      (fields
        (field (name "Manufacturer Part") "CL10A105KB8NNNC")
        (field (name "Manufacturer") "SAMSUNG(三星)")
      )
      (libsource (lib "easyedapro") (part "CAP"))
    )
    (comp (ref "C132")
      (value "10nF")
      (description "Capacitance:10nF Tolerance:±10% Tolerance:±10% Voltage Rating:50V Temperature Coefficient:X7R")
      (fields
        (field (name "Manufacturer Part") "CC0402KRX7R9BB103")
        (field (name "Manufacturer") "YAGEO(国巨)")
      )
      (libsource (lib "easyedapro") (part "CAP"))
    )
    (comp (ref "C133")
      (value "1uF")
      (description "Capacitance:1uF Tolerance:±10% Tolerance:±10% Voltage Rating:25V Temperature Coefficient:X5R")
      (fields
        (field (name "Manufacturer Part") "CL05A105KA5NQNC")
        (field (name "Manufacturer") "SAMSUNG(三星)")
      )
      (libsource (lib "easyedapro") (part "CAP"))
    )
    (comp (ref "C134")
      (value "1uF")
      (description "Capacitance:1uF Tolerance:±10% Tolerance:±10% Voltage Rating:25V Temperature Coefficient:X5R")
      (fields
        (field (name "Manufacturer Part") "CL05A105KA5NQNC")
        (field (name "Manufacturer") "SAMSUNG(三星)")
      )
      (libsource (lib "easyedapro") (part "CAP"))
    )
    (comp (ref "C135")
      (value "1uF")
      (description "Capacitance:1uF Tolerance:±10% Tolerance:±10% Voltage Rating:25V Temperature Coefficient:X5R")
      (fields
        (field (name "Manufacturer Part") "CL05A105KA5NQNC")
        (field (name "Manufacturer") "SAMSUNG(三星)")
      )
      (libsource (lib "easyedapro") (part "CAP"))
    )
    (comp (ref "C136")
      (value "100nF")
      (description "Capacitance:100nF Tolerance:±10% Tolerance:±10% Voltage Rating:16V Temperature Coefficient:X7R")
      (fields
        (field (name "Manufacturer Part") "CL05B104KO5NNNC")
        (field (name "Manufacturer") "SAMSUNG(三星)")
      )
      (libsource (lib "easyedapro") (part "CAP"))
    )
    (comp (ref "C137")
      (value "1uF")
      (description "Capacitance:1uF Tolerance:±10% Tolerance:±10% Voltage Rating:50V Temperature Coefficient:X5R")
      (fields
        (field (name "Manufacturer Part") "CL10A105KB8NNNC")
        (field (name "Manufacturer") "SAMSUNG(三星)")
      )
      (libsource (lib "easyedapro") (part "CAP"))
    )
    (comp (ref "C138")
      (value "10nF")
      (description "Capacitance:10nF Tolerance:±10% Tolerance:±10% Voltage Rating:50V Temperature Coefficient:X7R")
      (fields
        (field (name "Manufacturer Part") "CC0402KRX7R9BB103")
        (field (name "Manufacturer") "YAGEO(国巨)")
      )
      (libsource (lib "easyedapro") (part "CAP"))
    )
    (comp (ref "C139")
      (value "1uF")
      (description "Capacitance:1uF Tolerance:±10% Tolerance:±10% Voltage Rating:25V Temperature Coefficient:X5R")
      (fields
        (field (name "Manufacturer Part") "CL05A105KA5NQNC")
        (field (name "Manufacturer") "SAMSUNG(三星)")
      )
      (libsource (lib "easyedapro") (part "CAP"))
    )
    (comp (ref "C140")
      (value "1uF")
      (description "Capacitance:1uF Tolerance:±10% Tolerance:±10% Voltage Rating:25V Temperature Coefficient:X5R")
      (fields
        (field (name "Manufacturer Part") "CL05A105KA5NQNC")
        (field (name "Manufacturer") "SAMSUNG(三星)")
      )
      (libsource (lib "easyedapro") (part "CAP"))
    )
    (comp (ref "C141")
      (value "1uF")
      (description "Capacitance:1uF Tolerance:±10% Tolerance:±10% Voltage Rating:25V Temperature Coefficient:X5R")
      (fields
        (field (name "Manufacturer Part") "CL05A105KA5NQNC")
        (field (name "Manufacturer") "SAMSUNG(三星)")
      )
      (libsource (lib "easyedapro") (part "CAP"))
    )
    (comp (ref "C142")
      (value "100nF")
      (description "Capacitance:100nF Tolerance:±10% Tolerance:±10% Voltage Rating:16V Temperature Coefficient:X7R")
      (fields
        (field (name "Manufacturer Part") "CL05B104KO5NNNC")
        (field (name "Manufacturer") "SAMSUNG(三星)")
      )
      (libsource (lib "easyedapro") (part "CAP"))
    )
    (comp (ref "C143")
      (value "1uF")
      (description "Capacitance:1uF Tolerance:±10% Tolerance:±10% Voltage Rating:50V Temperature Coefficient:X5R")
      (fields
        (field (name "Manufacturer Part") "CL10A105KB8NNNC")
        (field (name "Manufacturer") "SAMSUNG(三星)")
      )
      (libsource (lib "easyedapro") (part "CAP"))
    )
    (comp (ref "C144")
      (value "10nF")
      (description "Capacitance:10nF Tolerance:±10% Tolerance:±10% Voltage Rating:50V Temperature Coefficient:X7R")
      (fields
        (field (name "Manufacturer Part") "CC0402KRX7R9BB103")
        (field (name "Manufacturer") "YAGEO(国巨)")
      )
      (libsource (lib "easyedapro") (part "CAP"))
    )
    (comp (ref "R25")
      (value "1kΩ")
      (fields
        (field (name "Manufacturer Part") "0402WGF1001TCE")
        (field (name "Manufacturer") "UNI-ROYAL(厚声)")
      )
      (libsource (lib "easyedapro") (part "Res"))
    )
    (comp (ref "R26")
      (value "1kΩ")
      (fields
        (field (name "Manufacturer Part") "0402WGF1001TCE")
        (field (name "Manufacturer") "UNI-ROYAL(厚声)")
      )
      (libsource (lib "easyedapro") (part "Res"))
    )
    (comp (ref "R27")
      (value "1kΩ")
      (fields
        (field (name "Manufacturer Part") "0402WGF1001TCE")
        (field (name "Manufacturer") "UNI-ROYAL(厚声)")
      )
      (libsource (lib "easyedapro") (part "Res"))
    )
    (comp (ref "R28")
      (value "1kΩ")
      (fields
        (field (name "Manufacturer Part") "0402WGF1001TCE")
        (field (name "Manufacturer") "UNI-ROYAL(厚声)")
      )
      (libsource (lib "easyedapro") (part "Res"))
    )
    (comp (ref "U1")
      (value "S8B-PH-K-S(LF)(SN)")
      (footprint "easyedapro:CONN-TH_S8B-PH-K-S-LF-SN")
      (fields (field (name "Manufacturer") "JST"))
      (libsource (lib "easyedapro") (part "S8B-PH-K-S-(LF)(SN)"))
    )
    (comp (ref "U6")
      (value "STM32G071CBT6")
      (footprint "easyedapro:LQFP-48_L7.0-W7.0-P0.50-LS9.0-BL")
      (fields (field (name "Manufacturer") "ST(意法半导体)"))
      (libsource (lib "easyedapro") (part "STM32G071CBT6"))
    )
    (comp (ref "U7")
      (value "STM32G071CBT6")
      (footprint "easyedapro:LQFP-48_L7.0-W7.0-P0.50-LS9.0-BL")
      (fields (field (name "Manufacturer") "ST(意法半导体)"))
      (libsource (lib "easyedapro") (part "STM32G071CBT6"))
    )
    (comp (ref "U8")
      (value "STM32G071CBT6")
      (footprint "easyedapro:LQFP-48_L7.0-W7.0-P0.50-LS9.0-BL")
      (fields (field (name "Manufacturer") "ST(意法半导体)"))
      (libsource (lib "easyedapro") (part "STM32G071CBT6"))
    )
    (comp (ref "U9")
      (value "STM32G071CBT6")
      (footprint "easyedapro:LQFP-48_L7.0-W7.0-P0.50-LS9.0-BL")
      (fields (field (name "Manufacturer") "ST(意法半导体)"))
      (libsource (lib "easyedapro") (part "STM32G071CBT6"))
    )
  )
  (nets
    (net (code "1") (name "+3.3V") (class "Default")
      (node (ref "C121") (pin "2") (pinfunction "2_2") (pintype "input"))
      (node (ref "C122") (pin "2") (pinfunction "2_2") (pintype "input"))
      (node (ref "C123") (pin "2") (pinfunction "2_2") (pintype "input"))
      (node (ref "C127") (pin "2") (pinfunction "2_2") (pintype "input"))
      (node (ref "C128") (pin "2") (pinfunction "2_2") (pintype "input"))
      (node (ref "C129") (pin "2") (pinfunction "2_2") (pintype "input"))
      (node (ref "C133") (pin "2") (pinfunction "2_2") (pintype "input"))
      (node (ref "C134") (pin "2") (pinfunction "2_2") (pintype "input"))
      (node (ref "C135") (pin "2") (pinfunction "2_2") (pintype "input"))
      (node (ref "C139") (pin "2") (pinfunction "2_2") (pintype "input"))
      (node (ref "C140") (pin "2") (pinfunction "2_2") (pintype "input"))
      (node (ref "C141") (pin "2") (pinfunction "2_2") (pintype "input"))
      (node (ref "C41") (pin "2") (pinfunction "2_2") (pintype "input"))
      (node (ref "D26") (pin "1") (pinfunction "1_1") (pintype "unspecified"))
      (node (ref "D27") (pin "1") (pinfunction "1_1") (pintype "unspecified"))
      (node (ref "D28") (pin "1") (pinfunction "1_1") (pintype "unspecified"))
      (node (ref "D29") (pin "1") (pinfunction "1_1") (pintype "unspecified"))
      (node (ref "D30") (pin "1") (pinfunction "1_1") (pintype "unspecified"))
      (node (ref "D31") (pin "1") (pinfunction "1_1") (pintype "unspecified"))
      (node (ref "D32") (pin "1") (pinfunction "1_1") (pintype "unspecified"))
      (node (ref "D33") (pin "1") (pinfunction "1_1") (pintype "unspecified"))
      (node (ref "D34") (pin "1") (pinfunction "1_1") (pintype "unspecified"))
      (node (ref "D35") (pin "1") (pinfunction "1_1") (pintype "unspecified"))
      (node (ref "D36") (pin "1") (pinfunction "1_1") (pintype "unspecified"))
      (node (ref "D37") (pin "1") (pinfunction "1_1") (pintype "unspecified"))
      (node (ref "U1") (pin "2") (pinfunction "2_2") (pintype "unspecified"))
      (node (ref "U10") (pin "2") (pinfunction "Vout_2") (pintype "unspecified"))
      (node (ref "U6") (pin "6") (pinfunction "VDD/VDDA_6") (pintype "unspecified"))
      (node (ref "U7") (pin "6") (pinfunction "VDD/VDDA_6") (pintype "unspecified"))
      (node (ref "U8") (pin "6") (pinfunction "VDD/VDDA_6") (pintype "unspecified"))
      (node (ref "U9") (pin "6") (pinfunction "VDD/VDDA_6") (pintype "unspecified"))
    )
    (net (code "2") (name "+10V") (class "Default")
      (node (ref "C102") (pin "1") (pinfunction "1_1") (pintype "input"))
      (node (ref "C103") (pin "1") (pinfunction "1_1") (pintype "input"))
      (node (ref "C107") (pin "1") (pinfunction "1_1") (pintype "input"))
      (node (ref "C108") (pin "1") (pinfunction "1_1") (pintype "input"))
      (node (ref "C109") (pin "1") (pinfunction "1_1") (pintype "input"))
      (node (ref "C113") (pin "1") (pinfunction "1_1") (pintype "input"))
      (node (ref "C114") (pin "1") (pinfunction "1_1") (pintype "input"))
      (node (ref "C115") (pin "1") (pinfunction "1_1") (pintype "input"))
      (node (ref "C119") (pin "1") (pinfunction "1_1") (pintype "input"))
      (node (ref "C120") (pin "1") (pinfunction "1_1") (pintype "input"))
      (node (ref "C159") (pin "1") (pinfunction "1_1") (pintype "unspecified"))
      (node (ref "C161") (pin "1") (pinfunction "1_1") (pintype "unspecified"))
      (node (ref "C40") (pin "2") (pinfunction "2_2") (pintype "input"))
      (node (ref "C97") (pin "1") (pinfunction "1_1") (pintype "input"))
      (node (ref "C98") (pin "1") (pinfunction "1_1") (pintype "input"))
      (node (ref "D14") (pin "2") (pinfunction "2_2") (pintype "unspecified"))
      (node (ref "D15") (pin "2") (pinfunction "2_2") (pintype "unspecified"))
      (node (ref "D16") (pin "2") (pinfunction "2_2") (pintype "unspecified"))
      (node (ref "D17") (pin "2") (pinfunction "2_2") (pintype "unspecified"))
      (node (ref "D18") (pin "2") (pinfunction "2_2") (pintype "unspecified"))
      (node (ref "D19") (pin "2") (pinfunction "2_2") (pintype "unspecified"))
      (node (ref "D20") (pin "2") (pinfunction "2_2") (pintype "unspecified"))
      (node (ref "D21") (pin "2") (pinfunction "2_2") (pintype "unspecified"))
      (node (ref "D22") (pin "2") (pinfunction "2_2") (pintype "unspecified"))
      (node (ref "D23") (pin "2") (pinfunction "2_2") (pintype "unspecified"))
      (node (ref "D24") (pin "2") (pinfunction "2_2") (pintype "unspecified"))
      (node (ref "D25") (pin "2") (pinfunction "2_2") (pintype "unspecified"))
      (node (ref "L1") (pin "2") (pinfunction "2_2") (pintype "unspecified"))
      (node (ref "R68") (pin "2") (pinfunction "2_2") (pintype "input"))
      (node (ref "U10") (pin "3") (pinfunction "Vin_3") (pintype "unspecified"))
      (node (ref "U2") (pin "4") (pinfunction "VCC_4") (pintype "unspecified"))
      (node (ref "U3") (pin "4") (pinfunction "VCC_4") (pintype "unspecified"))
      (node (ref "U4") (pin "4") (pinfunction "VCC_4") (pintype "unspecified"))
      (node (ref "U5") (pin "4") (pinfunction "VCC_4") (pintype "unspecified"))
    )
    (net (code "3") (name "AHIGH_1") (class "Default")
      (node (ref "U2") (pin "22") (pinfunction "HIN1_22") (pintype "unspecified"))
      (node (ref "U6") (pin "34") (pinfunction "PA12[PA10]_34") (pintype "unspecified"))
    )
    (net (code "4") (name "AHIGH_2") (class "Default")
      (node (ref "U4") (pin "22") (pinfunction "HIN1_22") (pintype "unspecified"))
      (node (ref "U8") (pin "34") (pinfunction "PA12[PA10]_34") (pintype "unspecified"))
    )
    (net (code "5") (name "AHIGH_3") (class "Default")
      (node (ref "U3") (pin "22") (pinfunction "HIN1_22") (pintype "unspecified"))
      (node (ref "U7") (pin "34") (pinfunction "PA12[PA10]_34") (pintype "unspecified"))
    )
    (net (code "6") (name "AHIGH_4") (class "Default")
      (node (ref "U5") (pin "22") (pinfunction "HIN1_22") (pintype "unspecified"))
      (node (ref "U9") (pin "34") (pinfunction "PA12[PA10]_34") (pintype "unspecified"))
    )
    (net (code "7") (name "ALOW_1") (class "Default")
      (node (ref "U2") (pin "1") (pinfunction "LIN1_1") (pintype "unspecified"))
      (node (ref "U6") (pin "20") (pinfunction "PB1_20") (pintype "unspecified"))
    )
    (net (code "8") (name "ALOW_2") (class "Default")
      (node (ref "U4") (pin "1") (pinfunction "LIN1_1") (pintype "unspecified"))
      (node (ref "U8") (pin "20") (pinfunction "PB1_20") (pintype "unspecified"))
    )
    (net (code "9") (name "ALOW_3") (class "Default")
      (node (ref "U3") (pin "1") (pinfunction "LIN1_1") (pintype "unspecified"))
      (node (ref "U7") (pin "20") (pinfunction "PB1_20") (pintype "unspecified"))
    )
    (net (code "10") (name "ALOW_4") (class "Default")
      (node (ref "U5") (pin "1") (pinfunction "LIN1_1") (pintype "unspecified"))
      (node (ref "U9") (pin "20") (pinfunction "PB1_20") (pintype "unspecified"))
    )
    (net (code "11") (name "BEMFA_1") (class "Default")
      (node (ref "C145") (pin "1") (pinfunction "1_1") (pintype "input"))
      (node (ref "D26") (pin "2") (pinfunction "2_2") (pintype "unspecified"))
      (node (ref "R29") (pin "1") (pinfunction "1_1") (pintype "input"))
      (node (ref "R34") (pin "1") (pinfunction "1_1") (pintype "input"))
      (node (ref "R37") (pin "2") (pinfunction "2_2") (pintype "input"))
      (node (ref "U6") (pin "11") (pinfunction "PA0_11") (pintype "unspecified"))
    )
    (net (code "12") (name "BEMFA_2") (class "Default")
      (node (ref "C148") (pin "1") (pinfunction "1_1") (pintype "input"))
      (node (ref "D29") (pin "2") (pinfunction "2_2") (pintype "unspecified"))
      (node (ref "R38") (pin "1") (pinfunction "1_1") (pintype "input"))
      (node (ref "R43") (pin "1") (pinfunction "1_1") (pintype "input"))
      (node (ref "R46") (pin "2") (pinfunction "2_2") (pintype "input"))
      (node (ref "U8") (pin "11") (pinfunction "PA0_11") (pintype "unspecified"))
    )
    (net (code "13") (name "BEMFA_3") (class "Default")
      (node (ref "C151") (pin "1") (pinfunction "1_1") (pintype "input"))
      (node (ref "D32") (pin "2") (pinfunction "2_2") (pintype "unspecified"))
      (node (ref "R47") (pin "1") (pinfunction "1_1") (pintype "input"))
      (node (ref "R52") (pin "1") (pinfunction "1_1") (pintype "input"))
      (node (ref "R55") (pin "2") (pinfunction "2_2") (pintype "input"))
      (node (ref "U7") (pin "11") (pinfunction "PA0_11") (pintype "unspecified"))
    )
    (net (code "14") (name "BEMFA_4") (class "Default")
      (node (ref "C154") (pin "1") (pinfunction "1_1") (pintype "input"))
      (node (ref "D35") (pin "2") (pinfunction "2_2") (pintype "unspecified"))
      (node (ref "R56") (pin "1") (pinfunction "1_1") (pintype "input"))
      (node (ref "R61") (pin "1") (pinfunction "1_1") (pintype "input"))
      (node (ref "R64") (pin "2") (pinfunction "2_2") (pintype "input"))
      (node (ref "U9") (pin "11") (pinfunction "PA0_11") (pintype "unspecified"))
    )
    (net (code "15") (name "BEMFB_1") (class "Default")
      (node (ref "C146") (pin "1") (pinfunction "1_1") (pintype "input"))
      (node (ref "D27") (pin "2") (pinfunction "2_2") (pintype "unspecified"))
      (node (ref "R30") (pin "1") (pinfunction "1_1") (pintype "input"))
      (node (ref "R33") (pin "1") (pinfunction "1_1") (pintype "input"))
      (node (ref "R36") (pin "2") (pinfunction "2_2") (pintype "input"))
      (node (ref "U6") (pin "15") (pinfunction "PA4_15") (pintype "unspecified"))
    )
    (net (code "16") (name "BEMFB_2") (class "Default")
      (node (ref "C149") (pin "1") (pinfunction "1_1") (pintype "input"))
      (node (ref "D30") (pin "2") (pinfunction "2_2") (pintype "unspecified"))
      (node (ref "R39") (pin "1") (pinfunction "1_1") (pintype "input"))
      (node (ref "R42") (pin "1") (pinfunction "1_1") (pintype "input"))
      (node (ref "R45") (pin "2") (pinfunction "2_2") (pintype "input"))
      (node (ref "U8") (pin "15") (pinfunction "PA4_15") (pintype "unspecified"))
    )
    (net (code "17") (name "BEMFB_3") (class "Default")
      (node (ref "C152") (pin "1") (pinfunction "1_1") (pintype "input"))
      (node (ref "D33") (pin "2") (pinfunction "2_2") (pintype "unspecified"))
      (node (ref "R48") (pin "1") (pinfunction "1_1") (pintype "input"))
      (node (ref "R51") (pin "1") (pinfunction "1_1") (pintype "input"))
      (node (ref "R54") (pin "2") (pinfunction "2_2") (pintype "input"))
      (node (ref "U7") (pin "15") (pinfunction "PA4_15") (pintype "unspecified"))
    )
    (net (code "18") (name "BEMFB_4") (class "Default")
      (node (ref "C155") (pin "1") (pinfunction "1_1") (pintype "input"))
      (node (ref "D36") (pin "2") (pinfunction "2_2") (pintype "unspecified"))
      (node (ref "R57") (pin "1") (pinfunction "1_1") (pintype "input"))
      (node (ref "R60") (pin "1") (pinfunction "1_1") (pintype "input"))
      (node (ref "R63") (pin "2") (pinfunction "2_2") (pintype "input"))
      (node (ref "U9") (pin "15") (pinfunction "PA4_15") (pintype "unspecified"))
    )
    (net (code "19") (name "BEMFC_1") (class "Default")
      (node (ref "C147") (pin "1") (pinfunction "1_1") (pintype "input"))
      (node (ref "D28") (pin "2") (pinfunction "2_2") (pintype "unspecified"))
      (node (ref "R31") (pin "1") (pinfunction "1_1") (pintype "input"))
      (node (ref "R32") (pin "1") (pinfunction "1_1") (pintype "input"))
      (node (ref "R35") (pin "2") (pinfunction "2_2") (pintype "input"))
      (node (ref "U6") (pin "16") (pinfunction "PA5_16") (pintype "unspecified"))
    )
    (net (code "20") (name "BEMFC_2") (class "Default")
      (node (ref "C150") (pin "1") (pinfunction "1_1") (pintype "input"))
      (node (ref "D31") (pin "2") (pinfunction "2_2") (pintype "unspecified"))
      (node (ref "R40") (pin "1") (pinfunction "1_1") (pintype "input"))
      (node (ref "R41") (pin "1") (pinfunction "1_1") (pintype "input"))
      (node (ref "R44") (pin "2") (pinfunction "2_2") (pintype "input"))
      (node (ref "U8") (pin "16") (pinfunction "PA5_16") (pintype "unspecified"))
    )
    (net (code "21") (name "BEMFC_3") (class "Default")
      (node (ref "C153") (pin "1") (pinfunction "1_1") (pintype "input"))
      (node (ref "D34") (pin "2") (pinfunction "2_2") (pintype "unspecified"))
      (node (ref "R49") (pin "1") (pinfunction "1_1") (pintype "input"))
      (node (ref "R50") (pin "1") (pinfunction "1_1") (pintype "input"))
      (node (ref "R53") (pin "2") (pinfunction "2_2") (pintype "input"))
      (node (ref "U7") (pin "16") (pinfunction "PA5_16") (pintype "unspecified"))
    )
    (net (code "22") (name "BEMFC_4") (class "Default")
      (node (ref "C156") (pin "1") (pinfunction "1_1") (pintype "input"))
      (node (ref "D37") (pin "2") (pinfunction "2_2") (pintype "unspecified"))
      (node (ref "R58") (pin "1") (pinfunction "1_1") (pintype "input"))
      (node (ref "R59") (pin "1") (pinfunction "1_1") (pintype "input"))
      (node (ref "R62") (pin "2") (pinfunction "2_2") (pintype "input"))
      (node (ref "U9") (pin "16") (pinfunction "PA5_16") (pintype "unspecified"))
    )
    (net (code "23") (name "BEMF_COMMON_1") (class "Default")
      (node (ref "R29") (pin "2") (pinfunction "2_2") (pintype "input"))
      (node (ref "R30") (pin "2") (pinfunction "2_2") (pintype "input"))
      (node (ref "R31") (pin "2") (pinfunction "2_2") (pintype "input"))
      (node (ref "U6") (pin "12") (pinfunction "PA1_12") (pintype "unspecified"))
    )
    (net (code "24") (name "BEMF_COMMON_2") (class "Default")
      (node (ref "R38") (pin "2") (pinfunction "2_2") (pintype "input"))
      (node (ref "R39") (pin "2") (pinfunction "2_2") (pintype "input"))
      (node (ref "R40") (pin "2") (pinfunction "2_2") (pintype "input"))
      (node (ref "U8") (pin "12") (pinfunction "PA1_12") (pintype "unspecified"))
    )
    (net (code "25") (name "BEMF_COMMON_3") (class "Default")
      (node (ref "R47") (pin "2") (pinfunction "2_2") (pintype "input"))
      (node (ref "R48") (pin "2") (pinfunction "2_2") (pintype "input"))
      (node (ref "R49") (pin "2") (pinfunction "2_2") (pintype "input"))
      (node (ref "U7") (pin "12") (pinfunction "PA1_12") (pintype "unspecified"))
    )
    (net (code "26") (name "BEMF_COMMON_4") (class "Default")
      (node (ref "R56") (pin "2") (pinfunction "2_2") (pintype "input"))
      (node (ref "R57") (pin "2") (pinfunction "2_2") (pintype "input"))
      (node (ref "R58") (pin "2") (pinfunction "2_2") (pintype "input"))
      (node (ref "U9") (pin "12") (pinfunction "PA1_12") (pintype "unspecified"))
    )
    (net (code "27") (name "BHIGH_1") (class "Default")
      (node (ref "U2") (pin "23") (pinfunction "HIN2_23") (pintype "unspecified"))
      (node (ref "U6") (pin "33") (pinfunction "PA11[PA9]_33") (pintype "unspecified"))
    )
    (net (code "28") (name "BHIGH_2") (class "Default")
      (node (ref "U4") (pin "23") (pinfunction "HIN2_23") (pintype "unspecified"))
      (node (ref "U8") (pin "33") (pinfunction "PA11[PA9]_33") (pintype "unspecified"))
    )
    (net (code "29") (name "BHIGH_3") (class "Default")
      (node (ref "U3") (pin "23") (pinfunction "HIN2_23") (pintype "unspecified"))
      (node (ref "U7") (pin "33") (pinfunction "PA11[PA9]_33") (pintype "unspecified"))
    )
    (net (code "30") (name "BHIGH_4") (class "Default")
      (node (ref "U5") (pin "23") (pinfunction "HIN2_23") (pintype "unspecified"))
      (node (ref "U9") (pin "33") (pinfunction "PA11[PA9]_33") (pintype "unspecified"))
    )
    (net (code "31") (name "BLOW_1") (class "Default")
      (node (ref "U2") (pin "2") (pinfunction "LIN2_2") (pintype "unspecified"))
      (node (ref "U6") (pin "19") (pinfunction "PB0_19") (pintype "unspecified"))
    )
    (net (code "32") (name "BLOW_2") (class "Default")
      (node (ref "U4") (pin "2") (pinfunction "LIN2_2") (pintype "unspecified"))
      (node (ref "U8") (pin "19") (pinfunction "PB0_19") (pintype "unspecified"))
    )
    (net (code "33") (name "BLOW_3") (class "Default")
      (node (ref "U3") (pin "2") (pinfunction "LIN2_2") (pintype "unspecified"))
      (node (ref "U7") (pin "19") (pinfunction "PB0_19") (pintype "unspecified"))
    )
    (net (code "34") (name "BLOW_4") (class "Default")
      (node (ref "U5") (pin "2") (pinfunction "LIN2_2") (pintype "unspecified"))
      (node (ref "U9") (pin "19") (pinfunction "PB0_19") (pintype "unspecified"))
    )
    (net (code "35") (name "CHIGH_1") (class "Default")
      (node (ref "U2") (pin "24") (pinfunction "HIN3_24") (pintype "unspecified"))
      (node (ref "U6") (pin "28") (pinfunction "PA8_28") (pintype "unspecified"))
    )
    (net (code "36") (name "CHIGH_2") (class "Default")
      (node (ref "U4") (pin "24") (pinfunction "HIN3_24") (pintype "unspecified"))
      (node (ref "U8") (pin "28") (pinfunction "PA8_28") (pintype "unspecified"))
    )
    (net (code "37") (name "CHIGH_3") (class "Default")
      (node (ref "U3") (pin "24") (pinfunction "HIN3_24") (pintype "unspecified"))
      (node (ref "U7") (pin "28") (pinfunction "PA8_28") (pintype "unspecified"))
    )
    (net (code "38") (name "CHIGH_4") (class "Default")
      (node (ref "U5") (pin "24") (pinfunction "HIN3_24") (pintype "unspecified"))
      (node (ref "U9") (pin "28") (pinfunction "PA8_28") (pintype "unspecified"))
    )
    (net (code "39") (name "CLOW_1") (class "Default")
      (node (ref "U2") (pin "3") (pinfunction "LIN3_3") (pintype "unspecified"))
      (node (ref "U6") (pin "18") (pinfunction "PA7_18") (pintype "unspecified"))
    )
    (net (code "40") (name "CLOW_2") (class "Default")
      (node (ref "U4") (pin "3") (pinfunction "LIN3_3") (pintype "unspecified"))
      (node (ref "U8") (pin "18") (pinfunction "PA7_18") (pintype "unspecified"))
    )
    (net (code "41") (name "CLOW_3") (class "Default")
      (node (ref "U3") (pin "3") (pinfunction "LIN3_3") (pintype "unspecified"))
      (node (ref "U7") (pin "18") (pinfunction "PA7_18") (pintype "unspecified"))
    )
    (net (code "42") (name "CLOW_4") (class "Default")
      (node (ref "U5") (pin "3") (pinfunction "LIN3_3") (pintype "unspecified"))
      (node (ref "U9") (pin "18") (pinfunction "PA7_18") (pintype "unspecified"))
    )
    (net (code "43") (name "GHA_1") (class "Default")
      (node (ref "R71") (pin "1") (pinfunction "1_1") (pintype "input"))
      (node (ref "U2") (pin "19") (pinfunction "HO1_19") (pintype "unspecified"))
    )
    (net (code "44") (name "GHA_2") (class "Default")
      (node (ref "R83") (pin "1") (pinfunction "1_1") (pintype "input"))
      (node (ref "U4") (pin "19") (pinfunction "HO1_19") (pintype "unspecified"))
    )
    (net (code "45") (name "GHA_3") (class "Default")
      (node (ref "R77") (pin "1") (pinfunction "1_1") (pintype "input"))
      (node (ref "U3") (pin "19") (pinfunction "HO1_19") (pintype "unspecified"))
    )
    (net (code "46") (name "GHA_4") (class "Default")
      (node (ref "R89") (pin "1") (pinfunction "1_1") (pintype "input"))
      (node (ref "U5") (pin "19") (pinfunction "HO1_19") (pintype "unspecified"))
    )
    (net (code "47") (name "GHB_1") (class "Default")
      (node (ref "R70") (pin "1") (pinfunction "1_1") (pintype "input"))
      (node (ref "U2") (pin "16") (pinfunction "HO2_16") (pintype "unspecified"))
    )
    (net (code "48") (name "GHB_2") (class "Default")
      (node (ref "R82") (pin "1") (pinfunction "1_1") (pintype "input"))
      (node (ref "U4") (pin "16") (pinfunction "HO2_16") (pintype "unspecified"))
    )
    (net (code "49") (name "GHB_3") (class "Default")
      (node (ref "R76") (pin "1") (pinfunction "1_1") (pintype "input"))
      (node (ref "U3") (pin "16") (pinfunction "HO2_16") (pintype "unspecified"))
    )
    (net (code "50") (name "GHB_4") (class "Default")
      (node (ref "R88") (pin "1") (pinfunction "1_1") (pintype "input"))
      (node (ref "U5") (pin "16") (pinfunction "HO2_16") (pintype "unspecified"))
    )
    (net (code "51") (name "GHC_1") (class "Default")
      (node (ref "R69") (pin "1") (pinfunction "1_1") (pintype "input"))
      (node (ref "U2") (pin "13") (pinfunction "HO3_13") (pintype "unspecified"))
    )
    (net (code "52") (name "GHC_2") (class "Default")
      (node (ref "R81") (pin "1") (pinfunction "1_1") (pintype "input"))
      (node (ref "U4") (pin "13") (pinfunction "HO3_13") (pintype "unspecified"))
    )
    (net (code "53") (name "GHC_3") (class "Default")
      (node (ref "R75") (pin "1") (pinfunction "1_1") (pintype "input"))
      (node (ref "U3") (pin "13") (pinfunction "HO3_13") (pintype "unspecified"))
    )
    (net (code "54") (name "GHC_4") (class "Default")
      (node (ref "R87") (pin "1") (pinfunction "1_1") (pintype "input"))
      (node (ref "U5") (pin "13") (pinfunction "HO3_13") (pintype "unspecified"))
    )
    (net (code "55") (name "GLA_1") (class "Default")
      (node (ref "R72") (pin "1") (pinfunction "1_1") (pintype "input"))
      (node (ref "U2") (pin "11") (pinfunction "LO1_11") (pintype "unspecified"))
    )
    (net (code "56") (name "GLA_2") (class "Default")
      (node (ref "R84") (pin "1") (pinfunction "1_1") (pintype "input"))
      (node (ref "U4") (pin "11") (pinfunction "LO1_11") (pintype "unspecified"))
    )
    (net (code "57") (name "GLA_3") (class "Default")
      (node (ref "R78") (pin "1") (pinfunction "1_1") (pintype "input"))
      (node (ref "U3") (pin "11") (pinfunction "LO1_11") (pintype "unspecified"))
    )
    (net (code "58") (name "GLA_4") (class "Default")
      (node (ref "R90") (pin "1") (pinfunction "1_1") (pintype "input"))
      (node (ref "U5") (pin "11") (pinfunction "LO1_11") (pintype "unspecified"))
    )
    (net (code "59") (name "GLB_1") (class "Default")
      (node (ref "R73") (pin "1") (pinfunction "1_1") (pintype "input"))
      (node (ref "U2") (pin "10") (pinfunction "LO2_10") (pintype "unspecified"))
    )
    (net (code "60") (name "GLB_2") (class "Default")
      (node (ref "R85") (pin "1") (pinfunction "1_1") (pintype "input"))
      (node (ref "U4") (pin "10") (pinfunction "LO2_10") (pintype "unspecified"))
    )
    (net (code "61") (name "GLB_3") (class "Default")
      (node (ref "R79") (pin "1") (pinfunction "1_1") (pintype "input"))
      (node (ref "U3") (pin "10") (pinfunction "LO2_10") (pintype "unspecified"))
    )
    (net (code "62") (name "GLB_4") (class "Default")
      (node (ref "R91") (pin "1") (pinfunction "1_1") (pintype "input"))
      (node (ref "U5") (pin "10") (pinfunction "LO2_10") (pintype "unspecified"))
    )
    (net (code "63") (name "GLC_1") (class "Default")
      (node (ref "R74") (pin "1") (pinfunction "1_1") (pintype "input"))
      (node (ref "U2") (pin "9") (pinfunction "LO3_9") (pintype "unspecified"))
    )
    (net (code "64") (name "GLC_2") (class "Default")
      (node (ref "R86") (pin "1") (pinfunction "1_1") (pintype "input"))
      (node (ref "U4") (pin "9") (pinfunction "LO3_9") (pintype "unspecified"))
    )
    (net (code "65") (name "GLC_3") (class "Default")
      (node (ref "R80") (pin "1") (pinfunction "1_1") (pintype "input"))
      (node (ref "U3") (pin "9") (pinfunction "LO3_9") (pintype "unspecified"))
    )
    (net (code "66") (name "GLC_4") (class "Default")
      (node (ref "R92") (pin "1") (pinfunction "1_1") (pintype "input"))
      (node (ref "U5") (pin "9") (pinfunction "LO3_9") (pintype "unspecified"))
    )
    (net (code "67") (name "GND") (class "Default")
      (node (ref "C102") (pin "2") (pinfunction "2_2") (pintype "input"))
      (node (ref "C103") (pin "2") (pinfunction "2_2") (pintype "input"))
      (node (ref "C107") (pin "2") (pinfunction "2_2") (pintype "input"))
      (node (ref "C108") (pin "2") (pinfunction "2_2") (pintype "input"))
      (node (ref "C109") (pin "2") (pinfunction "2_2") (pintype "input"))
      (node (ref "C113") (pin "2") (pinfunction "2_2") (pintype "input"))
      (node (ref "C114") (pin "2") (pinfunction "2_2") (pintype "input"))
      (node (ref "C115") (pin "2") (pinfunction "2_2") (pintype "input"))
      (node (ref "C119") (pin "2") (pinfunction "2_2") (pintype "input"))
      (node (ref "C120") (pin "2") (pinfunction "2_2") (pintype "input"))
      (node (ref "C121") (pin "1") (pinfunction "1_1") (pintype "input"))
      (node (ref "C122") (pin "1") (pinfunction "1_1") (pintype "input"))
      (node (ref "C123") (pin "1") (pinfunction "1_1") (pintype "input"))
      (node (ref "C124") (pin "2") (pinfunction "2_2") (pintype "input"))
      (node (ref "C125") (pin "2") (pinfunction "2_2") (pintype "input"))
      (node (ref "C126") (pin "2") (pinfunction "2_2") (pintype "input"))
      (node (ref "C127") (pin "1") (pinfunction "1_1") (pintype "input"))
      (node (ref "C128") (pin "1") (pinfunction "1_1") (pintype "input"))
      (node (ref "C129") (pin "1") (pinfunction "1_1") (pintype "input"))
      (node (ref "C130") (pin "2") (pinfunction "2_2") (pintype "input"))
      (node (ref "C131") (pin "2") (pinfunction "2_2") (pintype "input"))
      (node (ref "C132") (pin "2") (pinfunction "2_2") (pintype "input"))
      (node (ref "C133") (pin "1") (pinfunction "1_1") (pintype "input"))
      (node (ref "C134") (pin "1") (pinfunction "1_1") (pintype "input"))
      (node (ref "C135") (pin "1") (pinfunction "1_1") (pintype "input"))
      (node (ref "C136") (pin "2") (pinfunction "2_2") (pintype "input"))
      (node (ref "C137") (pin "2") (pinfunction "2_2") (pintype "input"))
      (node (ref "C138") (pin "2") (pinfunction "2_2") (pintype "input"))
      (node (ref "C139") (pin "1") (pinfunction "1_1") (pintype "input"))
      (node (ref "C140") (pin "1") (pinfunction "1_1") (pintype "input"))
      (node (ref "C141") (pin "1") (pinfunction "1_1") (pintype "input"))
      (node (ref "C142") (pin "2") (pinfunction "2_2") (pintype "input"))
      (node (ref "C143") (pin "2") (pinfunction "2_2") (pintype "input"))
      (node (ref "C144") (pin "2") (pinfunction "2_2") (pintype "input"))
      (node (ref "C145") (pin "2") (pinfunction "2_2") (pintype "input"))
      (node (ref "C146") (pin "2") (pinfunction "2_2") (pintype "input"))
      (node (ref "C147") (pin "2") (pinfunction "2_2") (pintype "input"))
      (node (ref "C148") (pin "2") (pinfunction "2_2") (pintype "input"))
      (node (ref "C149") (pin "2") (pinfunction "2_2") (pintype "input"))
      (node (ref "C150") (pin "2") (pinfunction "2_2") (pintype "input"))
      (node (ref "C151") (pin "2") (pinfunction "2_2") (pintype "input"))
      (node (ref "C152") (pin "2") (pinfunction "2_2") (pintype "input"))
      (node (ref "C153") (pin "2") (pinfunction "2_2") (pintype "input"))
      (node (ref "C154") (pin "2") (pinfunction "2_2") (pintype "input"))
      (node (ref "C155") (pin "2") (pinfunction "2_2") (pintype "input"))
      (node (ref "C156") (pin "2") (pinfunction "2_2") (pintype "input"))
      (node (ref "C157") (pin "2") (pinfunction "2_2") (pintype "input"))
      (node (ref "C160") (pin "2") (pinfunction "2_2") (pintype "input"))
      (node (ref "C161") (pin "2") (pinfunction "2_2") (pintype "unspecified"))
      (node (ref "C165") (pin "1") (pinfunction "1_1") (pintype "input"))
      (node (ref "C166") (pin "1") (pinfunction "1_1") (pintype "input"))
      (node (ref "C167") (pin "1") (pinfunction "1_1") (pintype "input"))
      (node (ref "C171") (pin "1") (pinfunction "1_1") (pintype "input"))
      (node (ref "C172") (pin "1") (pinfunction "1_1") (pintype "input"))
      (node (ref "C173") (pin "1") (pinfunction "1_1") (pintype "input"))
      (node (ref "C177") (pin "1") (pinfunction "1_1") (pintype "input"))
      (node (ref "C178") (pin "1") (pinfunction "1_1") (pintype "input"))
      (node (ref "C179") (pin "1") (pinfunction "1_1") (pintype "input"))
      (node (ref "C183") (pin "1") (pinfunction "1_1") (pintype "input"))
      (node (ref "C184") (pin "1") (pinfunction "1_1") (pintype "input"))
      (node (ref "C185") (pin "1") (pinfunction "1_1") (pintype "input"))
      (node (ref "C186") (pin "2") (pinfunction "2_2") (pintype "input"))
      (node (ref "C187") (pin "2") (pinfunction "2_2") (pintype "input"))
      (node (ref "C188") (pin "2") (pinfunction "2_2") (pintype "input"))
      (node (ref "C189") (pin "2") (pinfunction "2_2") (pintype "input"))
      (node (ref "C40") (pin "1") (pinfunction "1_1") (pintype "input"))
      (node (ref "C41") (pin "1") (pinfunction "1_1") (pintype "input"))
      (node (ref "C42") (pin "2") (pinfunction "2_2") (pintype "input"))
      (node (ref "C43") (pin "2") (pinfunction "2_2") (pintype "input"))
      (node (ref "C44") (pin "2") (pinfunction "2_2") (pintype "input"))
      (node (ref "C45") (pin "2") (pinfunction "2_2") (pintype "input"))
      (node (ref "C46") (pin "2") (pinfunction "2_2") (pintype "input"))
      (node (ref "C47") (pin "1") (pinfunction "1_1") (pintype "input"))
      (node (ref "C48") (pin "1") (pinfunction "1_1") (pintype "input"))
      (node (ref "C49") (pin "1") (pinfunction "1_1") (pintype "input"))
      (node (ref "C50") (pin "1") (pinfunction "1_1") (pintype "input"))
      (node (ref "C51") (pin "1") (pinfunction "1_1") (pintype "input"))
      (node (ref "C52") (pin "2") (pinfunction "2_2") (pintype "input"))
      (node (ref "C53") (pin "2") (pinfunction "2_2") (pintype "input"))
      (node (ref "C54") (pin "2") (pinfunction "2_2") (pintype "input"))
      (node (ref "C55") (pin "2") (pinfunction "2_2") (pintype "input"))
      (node (ref "C56") (pin "2") (pinfunction "2_2") (pintype "input"))
      (node (ref "C57") (pin "1") (pinfunction "1_1") (pintype "input"))
      (node (ref "C58") (pin "1") (pinfunction "1_1") (pintype "input"))
      (node (ref "C59") (pin "1") (pinfunction "1_1") (pintype "input"))
      (node (ref "C60") (pin "1") (pinfunction "1_1") (pintype "input"))
      (node (ref "C61") (pin "1") (pinfunction "1_1") (pintype "input"))
      (node (ref "C97") (pin "2") (pinfunction "2_2") (pintype "input"))
      (node (ref "C98") (pin "2") (pinfunction "2_2") (pintype "input"))
      (node (ref "Q28") (pin "1") (pinfunction "S_1") (pintype "unspecified"))
      (node (ref "Q28") (pin "2") (pinfunction "S_2") (pintype "unspecified"))
      (node (ref "Q28") (pin "3") (pinfunction "S_3") (pintype "unspecified"))
      (node (ref "Q29") (pin "1") (pinfunction "S_1") (pintype "unspecified"))
      (node (ref "Q29") (pin "2") (pinfunction "S_2") (pintype "unspecified"))
      (node (ref "Q29") (pin "3") (pinfunction "S_3") (pintype "unspecified"))
      (node (ref "Q30") (pin "1") (pinfunction "S_1") (pintype "unspecified"))
      (node (ref "Q30") (pin "2") (pinfunction "S_2") (pintype "unspecified"))
      (node (ref "Q30") (pin "3") (pinfunction "S_3") (pintype "unspecified"))
      (node (ref "Q34") (pin "1") (pinfunction "S_1") (pintype "unspecified"))
      (node (ref "Q34") (pin "2") (pinfunction "S_2") (pintype "unspecified"))
      (node (ref "Q34") (pin "3") (pinfunction "S_3") (pintype "unspecified"))
      (node (ref "Q35") (pin "1") (pinfunction "S_1") (pintype "unspecified"))
      (node (ref "Q35") (pin "2") (pinfunction "S_2") (pintype "unspecified"))
      (node (ref "Q35") (pin "3") (pinfunction "S_3") (pintype "unspecified"))
      (node (ref "Q36") (pin "1") (pinfunction "S_1") (pintype "unspecified"))
      (node (ref "Q36") (pin "2") (pinfunction "S_2") (pintype "unspecified"))
      (node (ref "Q36") (pin "3") (pinfunction "S_3") (pintype "unspecified"))
      (node (ref "Q40") (pin "1") (pinfunction "S_1") (pintype "unspecified"))
      (node (ref "Q40") (pin "2") (pinfunction "S_2") (pintype "unspecified"))
      (node (ref "Q40") (pin "3") (pinfunction "S_3") (pintype "unspecified"))
      (node (ref "Q41") (pin "1") (pinfunction "S_1") (pintype "unspecified"))
      (node (ref "Q41") (pin "2") (pinfunction "S_2") (pintype "unspecified"))
      (node (ref "Q41") (pin "3") (pinfunction "S_3") (pintype "unspecified"))
      (node (ref "Q42") (pin "1") (pinfunction "S_1") (pintype "unspecified"))
      (node (ref "Q42") (pin "2") (pinfunction "S_2") (pintype "unspecified"))
      (node (ref "Q42") (pin "3") (pinfunction "S_3") (pintype "unspecified"))
      (node (ref "Q46") (pin "1") (pinfunction "S_1") (pintype "unspecified"))
      (node (ref "Q46") (pin "2") (pinfunction "S_2") (pintype "unspecified"))
      (node (ref "Q46") (pin "3") (pinfunction "S_3") (pintype "unspecified"))
      (node (ref "Q47") (pin "1") (pinfunction "S_1") (pintype "unspecified"))
      (node (ref "Q47") (pin "2") (pinfunction "S_2") (pintype "unspecified"))
      (node (ref "Q47") (pin "3") (pinfunction "S_3") (pintype "unspecified"))
      (node (ref "Q48") (pin "1") (pinfunction "S_1") (pintype "unspecified"))
      (node (ref "Q48") (pin "2") (pinfunction "S_2") (pintype "unspecified"))
      (node (ref "Q48") (pin "3") (pinfunction "S_3") (pintype "unspecified"))
      (node (ref "R35") (pin "1") (pinfunction "1_1") (pintype "input"))
      (node (ref "R36") (pin "1") (pinfunction "1_1") (pintype "input"))
      (node (ref "R37") (pin "1") (pinfunction "1_1") (pintype "input"))
      (node (ref "R44") (pin "1") (pinfunction "1_1") (pintype "input"))
      (node (ref "R45") (pin "1") (pinfunction "1_1") (pintype "input"))
      (node (ref "R46") (pin "1") (pinfunction "1_1") (pintype "input"))
      (node (ref "R53") (pin "1") (pinfunction "1_1") (pintype "input"))
      (node (ref "R54") (pin "1") (pinfunction "1_1") (pintype "input"))
      (node (ref "R55") (pin "1") (pinfunction "1_1") (pintype "input"))
      (node (ref "R62") (pin "1") (pinfunction "1_1") (pintype "input"))
      (node (ref "R63") (pin "1") (pinfunction "1_1") (pintype "input"))
      (node (ref "R64") (pin "1") (pinfunction "1_1") (pintype "input"))
      (node (ref "R65") (pin "1") (pinfunction "1_1") (pintype "input"))
      (node (ref "R67") (pin "1") (pinfunction "1_1") (pintype "input"))
      (node (ref "U1") (pin "1") (pinfunction "1_1") (pintype "unspecified"))
      (node (ref "U10") (pin "1") (pinfunction "GND_1") (pintype "unspecified"))
      (node (ref "U12") (pin "1") (pinfunction "GND_1") (pintype "unspecified"))
      (node (ref "U12") (pin "5") (pinfunction "FB_5") (pintype "unspecified"))
      (node (ref "U2") (pin "25") (pinfunction "EP_25") (pintype "unspecified"))
      (node (ref "U2") (pin "6") (pinfunction "COM_6") (pintype "unspecified"))
      (node (ref "U3") (pin "25") (pinfunction "EP_25") (pintype "unspecified"))
      (node (ref "U3") (pin "6") (pinfunction "COM_6") (pintype "unspecified"))
      (node (ref "U4") (pin "25") (pinfunction "EP_25") (pintype "unspecified"))
      (node (ref "U4") (pin "6") (pinfunction "COM_6") (pintype "unspecified"))
      (node (ref "U5") (pin "25") (pinfunction "EP_25") (pintype "unspecified"))
      (node (ref "U5") (pin "6") (pinfunction "COM_6") (pintype "unspecified"))
      (node (ref "U6") (pin "7") (pinfunction "VSS/VSSA_7") (pintype "unspecified"))
      (node (ref "U7") (pin "7") (pinfunction "VSS/VSSA_7") (pintype "unspecified"))
      (node (ref "U8") (pin "7") (pinfunction "VSS/VSSA_7") (pintype "unspecified"))
      (node (ref "U9") (pin "7") (pinfunction "VSS/VSSA_7") (pintype "unspecified"))
    )
    (net (code "68") (name "MOTORA_1") (class "Default")
      (node (ref "C101") (pin "2") (pinfunction "2_2") (pintype "input"))
      (node (ref "C164") (pin "2") (pinfunction "2_2") (pintype "input"))
      (node (ref "Q27") (pin "1") (pinfunction "S_1") (pintype "unspecified"))
      (node (ref "Q27") (pin "2") (pinfunction "S_2") (pintype "unspecified"))
      (node (ref "Q27") (pin "3") (pinfunction "S_3") (pintype "unspecified"))
      (node (ref "Q30") (pin "5") (pinfunction "D_5") (pintype "unspecified"))
      (node (ref "R34") (pin "2") (pinfunction "2_2") (pintype "input"))
      (node (ref "U2") (pin "18") (pinfunction "VS1_18") (pintype "unspecified"))
    )
    (net (code "69") (name "MOTORA_2") (class "Default")
      (node (ref "C112") (pin "2") (pinfunction "2_2") (pintype "input"))
      (node (ref "C176") (pin "2") (pinfunction "2_2") (pintype "input"))
      (node (ref "Q39") (pin "1") (pinfunction "S_1") (pintype "unspecified"))
      (node (ref "Q39") (pin "2") (pinfunction "S_2") (pintype "unspecified"))
      (node (ref "Q39") (pin "3") (pinfunction "S_3") (pintype "unspecified"))
      (node (ref "Q42") (pin "5") (pinfunction "D_5") (pintype "unspecified"))
      (node (ref "R43") (pin "2") (pinfunction "2_2") (pintype "input"))
      (node (ref "U4") (pin "18") (pinfunction "VS1_18") (pintype "unspecified"))
    )
    (net (code "70") (name "MOTORA_3") (class "Default")
      (node (ref "C106") (pin "2") (pinfunction "2_2") (pintype "input"))
      (node (ref "C170") (pin "2") (pinfunction "2_2") (pintype "input"))
      (node (ref "Q33") (pin "1") (pinfunction "S_1") (pintype "unspecified"))
      (node (ref "Q33") (pin "2") (pinfunction "S_2") (pintype "unspecified"))
      (node (ref "Q33") (pin "3") (pinfunction "S_3") (pintype "unspecified"))
      (node (ref "Q36") (pin "5") (pinfunction "D_5") (pintype "unspecified"))
      (node (ref "R52") (pin "2") (pinfunction "2_2") (pintype "input"))
      (node (ref "U3") (pin "18") (pinfunction "VS1_18") (pintype "unspecified"))
    )
    (net (code "71") (name "MOTORA_4") (class "Default")
      (node (ref "C118") (pin "2") (pinfunction "2_2") (pintype "input"))
      (node (ref "C182") (pin "2") (pinfunction "2_2") (pintype "input"))
      (node (ref "Q45") (pin "1") (pinfunction "S_1") (pintype "unspecified"))
      (node (ref "Q45") (pin "2") (pinfunction "S_2") (pintype "unspecified"))
      (node (ref "Q45") (pin "3") (pinfunction "S_3") (pintype "unspecified"))
      (node (ref "Q48") (pin "5") (pinfunction "D_5") (pintype "unspecified"))
      (node (ref "R61") (pin "2") (pinfunction "2_2") (pintype "input"))
      (node (ref "U5") (pin "18") (pinfunction "VS1_18") (pintype "unspecified"))
    )
    (net (code "72") (name "MOTORB_1") (class "Default")
      (node (ref "C100") (pin "2") (pinfunction "2_2") (pintype "input"))
      (node (ref "C163") (pin "2") (pinfunction "2_2") (pintype "input"))
      (node (ref "Q26") (pin "1") (pinfunction "S_1") (pintype "unspecified"))
      (node (ref "Q26") (pin "2") (pinfunction "S_2") (pintype "unspecified"))
      (node (ref "Q26") (pin "3") (pinfunction "S_3") (pintype "unspecified"))
      (node (ref "Q29") (pin "5") (pinfunction "D_5") (pintype "unspecified"))
      (node (ref "R33") (pin "2") (pinfunction "2_2") (pintype "input"))
      (node (ref "U2") (pin "15") (pinfunction "VS2_15") (pintype "unspecified"))
    )
    (net (code "73") (name "MOTORB_2") (class "Default")
      (node (ref "C111") (pin "2") (pinfunction "2_2") (pintype "input"))
      (node (ref "C175") (pin "2") (pinfunction "2_2") (pintype "input"))
      (node (ref "Q38") (pin "1") (pinfunction "S_1") (pintype "unspecified"))
      (node (ref "Q38") (pin "2") (pinfunction "S_2") (pintype "unspecified"))
      (node (ref "Q38") (pin "3") (pinfunction "S_3") (pintype "unspecified"))
      (node (ref "Q41") (pin "5") (pinfunction "D_5") (pintype "unspecified"))
      (node (ref "R42") (pin "2") (pinfunction "2_2") (pintype "input"))
      (node (ref "U4") (pin "15") (pinfunction "VS2_15") (pintype "unspecified"))
    )
    (net (code "74") (name "MOTORB_3") (class "Default")
      (node (ref "C105") (pin "2") (pinfunction "2_2") (pintype "input"))
      (node (ref "C169") (pin "2") (pinfunction "2_2") (pintype "input"))
      (node (ref "Q32") (pin "1") (pinfunction "S_1") (pintype "unspecified"))
      (node (ref "Q32") (pin "2") (pinfunction "S_2") (pintype "unspecified"))
      (node (ref "Q32") (pin "3") (pinfunction "S_3") (pintype "unspecified"))
      (node (ref "Q35") (pin "5") (pinfunction "D_5") (pintype "unspecified"))
      (node (ref "R51") (pin "2") (pinfunction "2_2") (pintype "input"))
      (node (ref "U3") (pin "15") (pinfunction "VS2_15") (pintype "unspecified"))
    )
    (net (code "75") (name "MOTORB_4") (class "Default")
      (node (ref "C117") (pin "2") (pinfunction "2_2") (pintype "input"))
      (node (ref "C181") (pin "2") (pinfunction "2_2") (pintype "input"))
      (node (ref "Q44") (pin "1") (pinfunction "S_1") (pintype "unspecified"))
      (node (ref "Q44") (pin "2") (pinfunction "S_2") (pintype "unspecified"))
      (node (ref "Q44") (pin "3") (pinfunction "S_3") (pintype "unspecified"))
      (node (ref "Q47") (pin "5") (pinfunction "D_5") (pintype "unspecified"))
      (node (ref "R60") (pin "2") (pinfunction "2_2") (pintype "input"))
      (node (ref "U5") (pin "15") (pinfunction "VS2_15") (pintype "unspecified"))
    )
    (net (code "76") (name "MOTORC_1") (class "Default")
      (node (ref "C162") (pin "2") (pinfunction "2_2") (pintype "input"))
      (node (ref "C99") (pin "2") (pinfunction "2_2") (pintype "input"))
      (node (ref "Q25") (pin "1") (pinfunction "S_1") (pintype "unspecified"))
      (node (ref "Q25") (pin "2") (pinfunction "S_2") (pintype "unspecified"))
      (node (ref "Q25") (pin "3") (pinfunction "S_3") (pintype "unspecified"))
      (node (ref "Q28") (pin "5") (pinfunction "D_5") (pintype "unspecified"))
      (node (ref "R32") (pin "2") (pinfunction "2_2") (pintype "input"))
      (node (ref "U2") (pin "12") (pinfunction "VS3_12") (pintype "unspecified"))
    )
    (net (code "77") (name "MOTORC_2") (class "Default")
      (node (ref "C110") (pin "2") (pinfunction "2_2") (pintype "input"))
      (node (ref "C174") (pin "2") (pinfunction "2_2") (pintype "input"))
      (node (ref "Q37") (pin "1") (pinfunction "S_1") (pintype "unspecified"))
      (node (ref "Q37") (pin "2") (pinfunction "S_2") (pintype "unspecified"))
      (node (ref "Q37") (pin "3") (pinfunction "S_3") (pintype "unspecified"))
      (node (ref "Q40") (pin "5") (pinfunction "D_5") (pintype "unspecified"))
      (node (ref "R41") (pin "2") (pinfunction "2_2") (pintype "input"))
      (node (ref "U4") (pin "12") (pinfunction "VS3_12") (pintype "unspecified"))
    )
    (net (code "78") (name "MOTORC_3") (class "Default")
      (node (ref "C104") (pin "2") (pinfunction "2_2") (pintype "input"))
      (node (ref "C168") (pin "2") (pinfunction "2_2") (pintype "input"))
      (node (ref "Q31") (pin "1") (pinfunction "S_1") (pintype "unspecified"))
      (node (ref "Q31") (pin "2") (pinfunction "S_2") (pintype "unspecified"))
      (node (ref "Q31") (pin "3") (pinfunction "S_3") (pintype "unspecified"))
      (node (ref "Q34") (pin "5") (pinfunction "D_5") (pintype "unspecified"))
      (node (ref "R50") (pin "2") (pinfunction "2_2") (pintype "input"))
      (node (ref "U3") (pin "12") (pinfunction "VS3_12") (pintype "unspecified"))
    )
    (net (code "79") (name "MOTORC_4") (class "Default")
      (node (ref "C116") (pin "2") (pinfunction "2_2") (pintype "input"))
      (node (ref "C180") (pin "2") (pinfunction "2_2") (pintype "input"))
      (node (ref "Q43") (pin "1") (pinfunction "S_1") (pintype "unspecified"))
      (node (ref "Q43") (pin "2") (pinfunction "S_2") (pintype "unspecified"))
      (node (ref "Q43") (pin "3") (pinfunction "S_3") (pintype "unspecified"))
      (node (ref "Q46") (pin "5") (pinfunction "D_5") (pintype "unspecified"))
      (node (ref "R59") (pin "2") (pinfunction "2_2") (pintype "input"))
      (node (ref "U5") (pin "12") (pinfunction "VS3_12") (pintype "unspecified"))
    )
    (net (code "80") (name "Net-(C159-Pad2)") (class "Default")
      (node (ref "C159") (pin "2") (pinfunction "2_2") (pintype "unspecified"))
      (node (ref "C160") (pin "1") (pinfunction "1_1") (pintype "input"))
      (node (ref "R66") (pin "2") (pinfunction "2_2") (pintype "input"))
    )
    (net (code "81") (name "Net-(Q25-G)") (class "Default")
      (node (ref "C162") (pin "1") (pinfunction "1_1") (pintype "input"))
      (node (ref "Q25") (pin "4") (pinfunction "G_4") (pintype "unspecified"))
      (node (ref "R69") (pin "2") (pinfunction "2_2") (pintype "input"))
    )
    (net (code "82") (name "Net-(Q26-G)") (class "Default")
      (node (ref "C163") (pin "1") (pinfunction "1_1") (pintype "input"))
      (node (ref "Q26") (pin "4") (pinfunction "G_4") (pintype "unspecified"))
      (node (ref "R70") (pin "2") (pinfunction "2_2") (pintype "input"))
    )
    (net (code "83") (name "Net-(Q27-G)") (class "Default")
      (node (ref "C164") (pin "1") (pinfunction "1_1") (pintype "input"))
      (node (ref "Q27") (pin "4") (pinfunction "G_4") (pintype "unspecified"))
      (node (ref "R71") (pin "2") (pinfunction "2_2") (pintype "input"))
    )
    (net (code "84") (name "Net-(Q28-G)") (class "Default")
      (node (ref "C165") (pin "2") (pinfunction "2_2") (pintype "input"))
      (node (ref "Q28") (pin "4") (pinfunction "G_4") (pintype "unspecified"))
      (node (ref "R74") (pin "2") (pinfunction "2_2") (pintype "input"))
    )
    (net (code "85") (name "Net-(Q29-G)") (class "Default")
      (node (ref "C166") (pin "2") (pinfunction "2_2") (pintype "input"))
      (node (ref "Q29") (pin "4") (pinfunction "G_4") (pintype "unspecified"))
      (node (ref "R73") (pin "2") (pinfunction "2_2") (pintype "input"))
    )
    (net (code "86") (name "Net-(Q30-G)") (class "Default")
      (node (ref "C167") (pin "2") (pinfunction "2_2") (pintype "input"))
      (node (ref "Q30") (pin "4") (pinfunction "G_4") (pintype "unspecified"))
      (node (ref "R72") (pin "2") (pinfunction "2_2") (pintype "input"))
    )
    (net (code "87") (name "Net-(Q31-G)") (class "Default")
      (node (ref "C168") (pin "1") (pinfunction "1_1") (pintype "input"))
      (node (ref "Q31") (pin "4") (pinfunction "G_4") (pintype "unspecified"))
      (node (ref "R75") (pin "2") (pinfunction "2_2") (pintype "input"))
    )
    (net (code "88") (name "Net-(Q32-G)") (class "Default")
      (node (ref "C169") (pin "1") (pinfunction "1_1") (pintype "input"))
      (node (ref "Q32") (pin "4") (pinfunction "G_4") (pintype "unspecified"))
      (node (ref "R76") (pin "2") (pinfunction "2_2") (pintype "input"))
    )
    (net (code "89") (name "Net-(Q33-G)") (class "Default")
      (node (ref "C170") (pin "1") (pinfunction "1_1") (pintype "input"))
      (node (ref "Q33") (pin "4") (pinfunction "G_4") (pintype "unspecified"))
      (node (ref "R77") (pin "2") (pinfunction "2_2") (pintype "input"))
    )
    (net (code "90") (name "Net-(Q34-G)") (class "Default")
      (node (ref "C171") (pin "2") (pinfunction "2_2") (pintype "input"))
      (node (ref "Q34") (pin "4") (pinfunction "G_4") (pintype "unspecified"))
      (node (ref "R80") (pin "2") (pinfunction "2_2") (pintype "input"))
    )
    (net (code "91") (name "Net-(Q35-G)") (class "Default")
      (node (ref "C172") (pin "2") (pinfunction "2_2") (pintype "input"))
      (node (ref "Q35") (pin "4") (pinfunction "G_4") (pintype "unspecified"))
      (node (ref "R79") (pin "2") (pinfunction "2_2") (pintype "input"))
    )
    (net (code "92") (name "Net-(Q36-G)") (class "Default")
      (node (ref "C173") (pin "2") (pinfunction "2_2") (pintype "input"))
      (node (ref "Q36") (pin "4") (pinfunction "G_4") (pintype "unspecified"))
      (node (ref "R78") (pin "2") (pinfunction "2_2") (pintype "input"))
    )
    (net (code "93") (name "Net-(Q37-G)") (class "Default")
      (node (ref "C174") (pin "1") (pinfunction "1_1") (pintype "input"))
      (node (ref "Q37") (pin "4") (pinfunction "G_4") (pintype "unspecified"))
      (node (ref "R81") (pin "2") (pinfunction "2_2") (pintype "input"))
    )
    (net (code "94") (name "Net-(Q38-G)") (class "Default")
      (node (ref "C175") (pin "1") (pinfunction "1_1") (pintype "input"))
      (node (ref "Q38") (pin "4") (pinfunction "G_4") (pintype "unspecified"))
      (node (ref "R82") (pin "2") (pinfunction "2_2") (pintype "input"))
    )
    (net (code "95") (name "Net-(Q39-G)") (class "Default")
      (node (ref "C176") (pin "1") (pinfunction "1_1") (pintype "input"))
      (node (ref "Q39") (pin "4") (pinfunction "G_4") (pintype "unspecified"))
      (node (ref "R83") (pin "2") (pinfunction "2_2") (pintype "input"))
    )
    (net (code "96") (name "Net-(Q40-G)") (class "Default")
      (node (ref "C177") (pin "2") (pinfunction "2_2") (pintype "input"))
      (node (ref "Q40") (pin "4") (pinfunction "G_4") (pintype "unspecified"))
      (node (ref "R86") (pin "2") (pinfunction "2_2") (pintype "input"))
    )
    (net (code "97") (name "Net-(Q41-G)") (class "Default")
      (node (ref "C178") (pin "2") (pinfunction "2_2") (pintype "input"))
      (node (ref "Q41") (pin "4") (pinfunction "G_4") (pintype "unspecified"))
      (node (ref "R85") (pin "2") (pinfunction "2_2") (pintype "input"))
    )
    (net (code "98") (name "Net-(Q42-G)") (class "Default")
      (node (ref "C179") (pin "2") (pinfunction "2_2") (pintype "input"))
      (node (ref "Q42") (pin "4") (pinfunction "G_4") (pintype "unspecified"))
      (node (ref "R84") (pin "2") (pinfunction "2_2") (pintype "input"))
    )
    (net (code "99") (name "Net-(Q43-G)") (class "Default")
      (node (ref "C180") (pin "1") (pinfunction "1_1") (pintype "input"))
      (node (ref "Q43") (pin "4") (pinfunction "G_4") (pintype "unspecified"))
      (node (ref "R87") (pin "2") (pinfunction "2_2") (pintype "input"))
    )
    (net (code "100") (name "Net-(Q44-G)") (class "Default")
      (node (ref "C181") (pin "1") (pinfunction "1_1") (pintype "input"))
      (node (ref "Q44") (pin "4") (pinfunction "G_4") (pintype "unspecified"))
      (node (ref "R88") (pin "2") (pinfunction "2_2") (pintype "input"))
    )
    (net (code "101") (name "Net-(Q45-G)") (class "Default")
      (node (ref "C182") (pin "1") (pinfunction "1_1") (pintype "input"))
      (node (ref "Q45") (pin "4") (pinfunction "G_4") (pintype "unspecified"))
      (node (ref "R89") (pin "2") (pinfunction "2_2") (pintype "input"))
    )
    (net (code "102") (name "Net-(Q46-G)") (class "Default")
      (node (ref "C183") (pin "2") (pinfunction "2_2") (pintype "input"))
      (node (ref "Q46") (pin "4") (pinfunction "G_4") (pintype "unspecified"))
      (node (ref "R92") (pin "2") (pinfunction "2_2") (pintype "input"))
    )
    (net (code "103") (name "Net-(Q47-G)") (class "Default")
      (node (ref "C184") (pin "2") (pinfunction "2_2") (pintype "input"))
      (node (ref "Q47") (pin "4") (pinfunction "G_4") (pintype "unspecified"))
      (node (ref "R91") (pin "2") (pinfunction "2_2") (pintype "input"))
    )
    (net (code "104") (name "Net-(Q48-G)") (class "Default")
      (node (ref "C185") (pin "2") (pinfunction "2_2") (pintype "input"))
      (node (ref "Q48") (pin "4") (pinfunction "G_4") (pintype "unspecified"))
      (node (ref "R90") (pin "2") (pinfunction "2_2") (pintype "input"))
    )
    (net (code "105") (name "Net-(R67-Pad2)") (class "Default")
      (node (ref "R67") (pin "2") (pinfunction "2_2") (pintype "input"))
      (node (ref "R68") (pin "1") (pinfunction "1_1") (pintype "input"))
    )
    (net (code "106") (name "Net-(U2-VB1)") (class "Default")
      (node (ref "C101") (pin "1") (pinfunction "1_1") (pintype "input"))
      (node (ref "D16") (pin "1") (pinfunction "1_1") (pintype "unspecified"))
      (node (ref "U2") (pin "20") (pinfunction "VB1_20") (pintype "unspecified"))
    )
    (net (code "107") (name "Net-(U2-VB2)") (class "Default")
      (node (ref "C100") (pin "1") (pinfunction "1_1") (pintype "input"))
      (node (ref "D15") (pin "1") (pinfunction "1_1") (pintype "unspecified"))
      (node (ref "U2") (pin "17") (pinfunction "VB2_17") (pintype "unspecified"))
    )
    (net (code "108") (name "Net-(U2-VB3)") (class "Default")
      (node (ref "C99") (pin "1") (pinfunction "1_1") (pintype "input"))
      (node (ref "D14") (pin "1") (pinfunction "1_1") (pintype "unspecified"))
      (node (ref "U2") (pin "14") (pinfunction "VB3_14") (pintype "unspecified"))
    )
    (net (code "109") (name "Net-(U3-VB1)") (class "Default")
      (node (ref "C106") (pin "1") (pinfunction "1_1") (pintype "input"))
      (node (ref "D19") (pin "1") (pinfunction "1_1") (pintype "unspecified"))
      (node (ref "U3") (pin "20") (pinfunction "VB1_20") (pintype "unspecified"))
    )
    (net (code "110") (name "Net-(U3-VB2)") (class "Default")
      (node (ref "C105") (pin "1") (pinfunction "1_1") (pintype "input"))
      (node (ref "D18") (pin "1") (pinfunction "1_1") (pintype "unspecified"))
      (node (ref "U3") (pin "17") (pinfunction "VB2_17") (pintype "unspecified"))
    )
    (net (code "111") (name "Net-(U3-VB3)") (class "Default")
      (node (ref "C104") (pin "1") (pinfunction "1_1") (pintype "input"))
      (node (ref "D17") (pin "1") (pinfunction "1_1") (pintype "unspecified"))
      (node (ref "U3") (pin "14") (pinfunction "VB3_14") (pintype "unspecified"))
    )
    (net (code "112") (name "Net-(U4-VB1)") (class "Default")
      (node (ref "C112") (pin "1") (pinfunction "1_1") (pintype "input"))
      (node (ref "D22") (pin "1") (pinfunction "1_1") (pintype "unspecified"))
      (node (ref "U4") (pin "20") (pinfunction "VB1_20") (pintype "unspecified"))
    )
    (net (code "113") (name "Net-(U4-VB2)") (class "Default")
      (node (ref "C111") (pin "1") (pinfunction "1_1") (pintype "input"))
      (node (ref "D21") (pin "1") (pinfunction "1_1") (pintype "unspecified"))
      (node (ref "U4") (pin "17") (pinfunction "VB2_17") (pintype "unspecified"))
    )
    (net (code "114") (name "Net-(U4-VB3)") (class "Default")
      (node (ref "C110") (pin "1") (pinfunction "1_1") (pintype "input"))
      (node (ref "D20") (pin "1") (pinfunction "1_1") (pintype "unspecified"))
      (node (ref "U4") (pin "14") (pinfunction "VB3_14") (pintype "unspecified"))
    )
    (net (code "115") (name "Net-(U5-VB1)") (class "Default")
      (node (ref "C118") (pin "1") (pinfunction "1_1") (pintype "input"))
      (node (ref "D25") (pin "1") (pinfunction "1_1") (pintype "unspecified"))
      (node (ref "U5") (pin "20") (pinfunction "VB1_20") (pintype "unspecified"))
    )
    (net (code "116") (name "Net-(U5-VB2)") (class "Default")
      (node (ref "C117") (pin "1") (pinfunction "1_1") (pintype "input"))
      (node (ref "D24") (pin "1") (pinfunction "1_1") (pintype "unspecified"))
      (node (ref "U5") (pin "17") (pinfunction "VB2_17") (pintype "unspecified"))
    )
    (net (code "117") (name "Net-(U5-VB3)") (class "Default")
      (node (ref "C116") (pin "1") (pinfunction "1_1") (pintype "input"))
      (node (ref "D23") (pin "1") (pinfunction "1_1") (pintype "unspecified"))
      (node (ref "U5") (pin "14") (pinfunction "VB3_14") (pintype "unspecified"))
    )
    (net (code "118") (name "Net-(U6-PA2)") (class "Default")
      (node (ref "R25") (pin "2") (pinfunction "2_2") (pintype "input"))
      (node (ref "U6") (pin "13") (pinfunction "PA2_13") (pintype "unspecified"))
    )
    (net (code "119") (name "Net-(U6-PF2-NRST)") (class "Default")
      (node (ref "C124") (pin "1") (pinfunction "1_1") (pintype "input"))
      (node (ref "U6") (pin "10") (pinfunction "PF2-NRST_10") (pintype "unspecified"))
    )
    (net (code "120") (name "Net-(U6-VREF+)") (class "Default")
      (node (ref "C125") (pin "1") (pinfunction "1_1") (pintype "input"))
      (node (ref "C126") (pin "1") (pinfunction "1_1") (pintype "input"))
      (node (ref "U6") (pin "5") (pinfunction "VREF+_5") (pintype "unspecified"))
    )
    (net (code "121") (name "Net-(U7-PA2)") (class "Default")
      (node (ref "R26") (pin "2") (pinfunction "2_2") (pintype "input"))
      (node (ref "U7") (pin "13") (pinfunction "PA2_13") (pintype "unspecified"))
    )
    (net (code "122") (name "Net-(U7-PF2-NRST)") (class "Default")
      (node (ref "C130") (pin "1") (pinfunction "1_1") (pintype "input"))
      (node (ref "U7") (pin "10") (pinfunction "PF2-NRST_10") (pintype "unspecified"))
    )
    (net (code "123") (name "Net-(U7-VREF+)") (class "Default")
      (node (ref "C131") (pin "1") (pinfunction "1_1") (pintype "input"))
      (node (ref "C132") (pin "1") (pinfunction "1_1") (pintype "input"))
      (node (ref "U7") (pin "5") (pinfunction "VREF+_5") (pintype "unspecified"))
    )
    (net (code "124") (name "Net-(U8-PA2)") (class "Default")
      (node (ref "R27") (pin "2") (pinfunction "2_2") (pintype "input"))
      (node (ref "U8") (pin "13") (pinfunction "PA2_13") (pintype "unspecified"))
    )
    (net (code "125") (name "Net-(U8-PF2-NRST)") (class "Default")
      (node (ref "C136") (pin "1") (pinfunction "1_1") (pintype "input"))
      (node (ref "U8") (pin "10") (pinfunction "PF2-NRST_10") (pintype "unspecified"))
    )
    (net (code "126") (name "Net-(U8-VREF+)") (class "Default")
      (node (ref "C137") (pin "1") (pinfunction "1_1") (pintype "input"))
      (node (ref "C138") (pin "1") (pinfunction "1_1") (pintype "input"))
      (node (ref "U8") (pin "5") (pinfunction "VREF+_5") (pintype "unspecified"))
    )
    (net (code "127") (name "Net-(U9-PA2)") (class "Default")
      (node (ref "R28") (pin "2") (pinfunction "2_2") (pintype "input"))
      (node (ref "U9") (pin "13") (pinfunction "PA2_13") (pintype "unspecified"))
    )
    (net (code "128") (name "Net-(U9-PF2-NRST)") (class "Default")
      (node (ref "C142") (pin "1") (pinfunction "1_1") (pintype "input"))
      (node (ref "U9") (pin "10") (pinfunction "PF2-NRST_10") (pintype "unspecified"))
    )
    (net (code "129") (name "Net-(U9-VREF+)") (class "Default")
      (node (ref "C143") (pin "1") (pinfunction "1_1") (pintype "input"))
      (node (ref "C144") (pin "1") (pinfunction "1_1") (pintype "input"))
      (node (ref "U9") (pin "5") (pinfunction "VREF+_5") (pintype "unspecified"))
    )
    (net (code "130") (name "Net-(U12-BST)") (class "Default")
      (node (ref "C158") (pin "2") (pinfunction "2_2") (pintype "input"))
      (node (ref "U12") (pin "7") (pinfunction "BST_7") (pintype "unspecified"))
    )
    (net (code "131") (name "Net-(U12-RON)") (class "Default")
      (node (ref "R65") (pin "2") (pinfunction "2_2") (pintype "input"))
      (node (ref "U12") (pin "4") (pinfunction "RON_4") (pintype "unspecified"))
    )
    (net (code "132") (name "Net-(U12-SW)") (class "Default")
      (node (ref "C158") (pin "1") (pinfunction "1_1") (pintype "input"))
      (node (ref "L1") (pin "1") (pinfunction "1_1") (pintype "unspecified"))
      (node (ref "R66") (pin "1") (pinfunction "1_1") (pintype "input"))
      (node (ref "U12") (pin "8") (pinfunction "SW_8") (pintype "unspecified"))
    )
    (net (code "133") (name "S-INPUT_1") (class "Default")
      (node (ref "R25") (pin "1") (pinfunction "1_1") (pintype "input"))
      (node (ref "U1") (pin "5") (pinfunction "5_5") (pintype "unspecified"))
    )
    (net (code "134") (name "S-INPUT_2") (class "Default")
      (node (ref "R27") (pin "1") (pinfunction "1_1") (pintype "input"))
      (node (ref "U1") (pin "6") (pinfunction "6_6") (pintype "unspecified"))
    )
    (net (code "135") (name "S-INPUT_3") (class "Default")
      (node (ref "R26") (pin "1") (pinfunction "1_1") (pintype "input"))
      (node (ref "U1") (pin "7") (pinfunction "7_7") (pintype "unspecified"))
    )
    (net (code "136") (name "S-INPUT_4") (class "Default")
      (node (ref "R28") (pin "1") (pinfunction "1_1") (pintype "input"))
      (node (ref "U1") (pin "8") (pinfunction "8_8") (pintype "unspecified"))
    )
    (net (code "137") (name "SWDCLK_1") (class "Default")
      (node (ref "U6") (pin "36") (pinfunction "PA14-BOOT0_36") (pintype "unspecified"))
    )
    (net (code "138") (name "SWDCLK_2") (class "Default")
      (node (ref "U8") (pin "36") (pinfunction "PA14-BOOT0_36") (pintype "unspecified"))
    )
    (net (code "139") (name "SWDCLK_3") (class "Default")
      (node (ref "U7") (pin "36") (pinfunction "PA14-BOOT0_36") (pintype "unspecified"))
    )
    (net (code "140") (name "SWDCLK_4") (class "Default")
      (node (ref "U9") (pin "36") (pinfunction "PA14-BOOT0_36") (pintype "unspecified"))
    )
    (net (code "141") (name "SWDIO_1") (class "Default")
      (node (ref "U6") (pin "35") (pinfunction "PA13_35") (pintype "unspecified"))
    )
    (net (code "142") (name "SWDIO_2") (class "Default")
      (node (ref "U8") (pin "35") (pinfunction "PA13_35") (pintype "unspecified"))
    )
    (net (code "143") (name "SWDIO_3") (class "Default")
      (node (ref "U7") (pin "35") (pinfunction "PA13_35") (pintype "unspecified"))
    )
    (net (code "144") (name "SWDIO_4") (class "Default")
      (node (ref "U9") (pin "35") (pinfunction "PA13_35") (pintype "unspecified"))
    )
    (net (code "145") (name "VCC") (class "Default")
      (node (ref "C157") (pin "1") (pinfunction "1_1") (pintype "input"))
      (node (ref "C186") (pin "1") (pinfunction "1_1") (pintype "input"))
      (node (ref "C187") (pin "1") (pinfunction "1_1") (pintype "input"))
      (node (ref "C188") (pin "1") (pinfunction "1_1") (pintype "input"))
      (node (ref "C189") (pin "1") (pinfunction "1_1") (pintype "input"))
      (node (ref "C42") (pin "1") (pinfunction "1_1") (pintype "input"))
      (node (ref "C43") (pin "1") (pinfunction "1_1") (pintype "input"))
      (node (ref "C44") (pin "1") (pinfunction "1_1") (pintype "input"))
      (node (ref "C45") (pin "1") (pinfunction "1_1") (pintype "input"))
      (node (ref "C46") (pin "1") (pinfunction "1_1") (pintype "input"))
      (node (ref "C47") (pin "2") (pinfunction "2_2") (pintype "input"))
      (node (ref "C48") (pin "2") (pinfunction "2_2") (pintype "input"))
      (node (ref "C49") (pin "2") (pinfunction "2_2") (pintype "input"))
      (node (ref "C50") (pin "2") (pinfunction "2_2") (pintype "input"))
      (node (ref "C51") (pin "2") (pinfunction "2_2") (pintype "input"))
      (node (ref "C52") (pin "1") (pinfunction "1_1") (pintype "input"))
      (node (ref "C53") (pin "1") (pinfunction "1_1") (pintype "input"))
      (node (ref "C54") (pin "1") (pinfunction "1_1") (pintype "input"))
      (node (ref "C55") (pin "1") (pinfunction "1_1") (pintype "input"))
      (node (ref "C56") (pin "1") (pinfunction "1_1") (pintype "input"))
      (node (ref "C57") (pin "2") (pinfunction "2_2") (pintype "input"))
      (node (ref "C58") (pin "2") (pinfunction "2_2") (pintype "input"))
      (node (ref "C59") (pin "2") (pinfunction "2_2") (pintype "input"))
      (node (ref "C60") (pin "2") (pinfunction "2_2") (pintype "input"))
      (node (ref "C61") (pin "2") (pinfunction "2_2") (pintype "input"))
      (node (ref "Q25") (pin "5") (pinfunction "D_5") (pintype "unspecified"))
      (node (ref "Q26") (pin "5") (pinfunction "D_5") (pintype "unspecified"))
      (node (ref "Q27") (pin "5") (pinfunction "D_5") (pintype "unspecified"))
      (node (ref "Q31") (pin "5") (pinfunction "D_5") (pintype "unspecified"))
      (node (ref "Q32") (pin "5") (pinfunction "D_5") (pintype "unspecified"))
      (node (ref "Q33") (pin "5") (pinfunction "D_5") (pintype "unspecified"))
      (node (ref "Q37") (pin "5") (pinfunction "D_5") (pintype "unspecified"))
      (node (ref "Q38") (pin "5") (pinfunction "D_5") (pintype "unspecified"))
      (node (ref "Q39") (pin "5") (pinfunction "D_5") (pintype "unspecified"))
      (node (ref "Q43") (pin "5") (pinfunction "D_5") (pintype "unspecified"))
      (node (ref "Q44") (pin "5") (pinfunction "D_5") (pintype "unspecified"))
      (node (ref "Q45") (pin "5") (pinfunction "D_5") (pintype "unspecified"))
      (node (ref "U12") (pin "2") (pinfunction "VIN_2") (pintype "unspecified"))
      (node (ref "U12") (pin "3") (pinfunction "EN/UVLO_3") (pintype "unspecified"))
    )
    (net (code "146") (name "unconnected-(U1-Pad3)") (class "Default")
      (node (ref "U1") (pin "3") (pinfunction "3_3") (pintype "unspecified"))
    )
    (net (code "147") (name "unconnected-(U1-Pad4)") (class "Default")
      (node (ref "U1") (pin "4") (pinfunction "4_4") (pintype "unspecified"))
    )
    (net (code "148") (name "unconnected-(U2-NC-Pad5)") (class "Default")
      (node (ref "U2") (pin "5") (pinfunction "NC_5") (pintype "unspecified+no_connect"))
    )
    (net (code "149") (name "unconnected-(U2-NC-Pad7)") (class "Default")
      (node (ref "U2") (pin "7") (pinfunction "NC_7") (pintype "unspecified+no_connect"))
    )
    (net (code "150") (name "unconnected-(U2-NC-Pad8)") (class "Default")
      (node (ref "U2") (pin "8") (pinfunction "NC_8") (pintype "unspecified+no_connect"))
    )
    (net (code "151") (name "unconnected-(U2-NC-Pad21)") (class "Default")
      (node (ref "U2") (pin "21") (pinfunction "NC_21") (pintype "unspecified+no_connect"))
    )
    (net (code "152") (name "unconnected-(U3-NC-Pad5)") (class "Default")
      (node (ref "U3") (pin "5") (pinfunction "NC_5") (pintype "unspecified+no_connect"))
    )
    (net (code "153") (name "unconnected-(U3-NC-Pad7)") (class "Default")
      (node (ref "U3") (pin "7") (pinfunction "NC_7") (pintype "unspecified+no_connect"))
    )
    (net (code "154") (name "unconnected-(U3-NC-Pad8)") (class "Default")
      (node (ref "U3") (pin "8") (pinfunction "NC_8") (pintype "unspecified+no_connect"))
    )
    (net (code "155") (name "unconnected-(U3-NC-Pad21)") (class "Default")
      (node (ref "U3") (pin "21") (pinfunction "NC_21") (pintype "unspecified+no_connect"))
    )
    (net (code "156") (name "unconnected-(U4-NC-Pad5)") (class "Default")
      (node (ref "U4") (pin "5") (pinfunction "NC_5") (pintype "unspecified+no_connect"))
    )
    (net (code "157") (name "unconnected-(U4-NC-Pad7)") (class "Default")
      (node (ref "U4") (pin "7") (pinfunction "NC_7") (pintype "unspecified+no_connect"))
    )
    (net (code "158") (name "unconnected-(U4-NC-Pad8)") (class "Default")
      (node (ref "U4") (pin "8") (pinfunction "NC_8") (pintype "unspecified+no_connect"))
    )
    (net (code "159") (name "unconnected-(U4-NC-Pad21)") (class "Default")
      (node (ref "U4") (pin "21") (pinfunction "NC_21") (pintype "unspecified+no_connect"))
    )
    (net (code "160") (name "unconnected-(U5-NC-Pad5)") (class "Default")
      (node (ref "U5") (pin "5") (pinfunction "NC_5") (pintype "unspecified+no_connect"))
    )
    (net (code "161") (name "unconnected-(U5-NC-Pad7)") (class "Default")
      (node (ref "U5") (pin "7") (pinfunction "NC_7") (pintype "unspecified+no_connect"))
    )
    (net (code "162") (name "unconnected-(U5-NC-Pad8)") (class "Default")
      (node (ref "U5") (pin "8") (pinfunction "NC_8") (pintype "unspecified+no_connect"))
    )
    (net (code "163") (name "unconnected-(U5-NC-Pad21)") (class "Default")
      (node (ref "U5") (pin "21") (pinfunction "NC_21") (pintype "unspecified+no_connect"))
    )
    (net (code "164") (name "unconnected-(U6-PA3-Pad14)") (class "Default")
      (node (ref "U6") (pin "14") (pinfunction "PA3_14") (pintype "unspecified+no_connect"))
    )
    (net (code "165") (name "unconnected-(U6-PA6-Pad17)") (class "Default")
      (node (ref "U6") (pin "17") (pinfunction "PA6_17") (pintype "unspecified+no_connect"))
    )
    (net (code "166") (name "unconnected-(U6-PA9-Pad29)") (class "Default")
      (node (ref "U6") (pin "29") (pinfunction "PA9_29") (pintype "unspecified+no_connect"))
    )
    (net (code "167") (name "unconnected-(U6-PA10-Pad32)") (class "Default")
      (node (ref "U6") (pin "32") (pinfunction "PA10_32") (pintype "unspecified+no_connect"))
    )
    (net (code "168") (name "unconnected-(U6-PA15-Pad37)") (class "Default")
      (node (ref "U6") (pin "37") (pinfunction "PA15_37") (pintype "unspecified+no_connect"))
    )
    (net (code "169") (name "unconnected-(U6-PB2-Pad21)") (class "Default")
      (node (ref "U6") (pin "21") (pinfunction "PB2_21") (pintype "unspecified+no_connect"))
    )
    (net (code "170") (name "unconnected-(U6-PB3-Pad42)") (class "Default")
      (node (ref "U6") (pin "42") (pinfunction "PB3_42") (pintype "unspecified+no_connect"))
    )
    (net (code "171") (name "unconnected-(U6-PB4-Pad43)") (class "Default")
      (node (ref "U6") (pin "43") (pinfunction "PB4_43") (pintype "unspecified+no_connect"))
    )
    (net (code "172") (name "unconnected-(U6-PB5-Pad44)") (class "Default")
      (node (ref "U6") (pin "44") (pinfunction "PB5_44") (pintype "unspecified+no_connect"))
    )
    (net (code "173") (name "unconnected-(U6-PB6-Pad45)") (class "Default")
      (node (ref "U6") (pin "45") (pinfunction "PB6_45") (pintype "unspecified+no_connect"))
    )
    (net (code "174") (name "unconnected-(U6-PB7-Pad46)") (class "Default")
      (node (ref "U6") (pin "46") (pinfunction "PB7_46") (pintype "unspecified+no_connect"))
    )
    (net (code "175") (name "unconnected-(U6-PB8-Pad47)") (class "Default")
      (node (ref "U6") (pin "47") (pinfunction "PB8_47") (pintype "unspecified+no_connect"))
    )
    (net (code "176") (name "unconnected-(U6-PB9-Pad48)") (class "Default")
      (node (ref "U6") (pin "48") (pinfunction "PB9_48") (pintype "unspecified+no_connect"))
    )
    (net (code "177") (name "unconnected-(U6-PB10-Pad22)") (class "Default")
      (node (ref "U6") (pin "22") (pinfunction "PB10_22") (pintype "unspecified+no_connect"))
    )
    (net (code "178") (name "unconnected-(U6-PB11-Pad23)") (class "Default")
      (node (ref "U6") (pin "23") (pinfunction "PB11_23") (pintype "unspecified+no_connect"))
    )
    (net (code "179") (name "unconnected-(U6-PB12-Pad24)") (class "Default")
      (node (ref "U6") (pin "24") (pinfunction "PB12_24") (pintype "unspecified+no_connect"))
    )
    (net (code "180") (name "unconnected-(U6-PB13-Pad25)") (class "Default")
      (node (ref "U6") (pin "25") (pinfunction "PB13_25") (pintype "unspecified+no_connect"))
    )
    (net (code "181") (name "unconnected-(U6-PB14-Pad26)") (class "Default")
      (node (ref "U6") (pin "26") (pinfunction "PB14_26") (pintype "unspecified+no_connect"))
    )
    (net (code "182") (name "unconnected-(U6-PB15-Pad27)") (class "Default")
      (node (ref "U6") (pin "27") (pinfunction "PB15_27") (pintype "unspecified+no_connect"))
    )
    (net (code "183") (name "unconnected-(U6-PC6-Pad30)") (class "Default")
      (node (ref "U6") (pin "30") (pinfunction "PC6_30") (pintype "unspecified+no_connect"))
    )
    (net (code "184") (name "unconnected-(U6-PC7-Pad31)") (class "Default")
      (node (ref "U6") (pin "31") (pinfunction "PC7_31") (pintype "unspecified+no_connect"))
    )
    (net (code "185") (name "unconnected-(U6-PC13-Pad1)") (class "Default")
      (node (ref "U6") (pin "1") (pinfunction "PC13_1") (pintype "unspecified+no_connect"))
    )
    (net (code "186") (name "unconnected-(U6-PC14-OSC32_IN-Pad2)") (class "Default")
      (node (ref "U6") (pin "2") (pinfunction "PC14-OSC32_IN_2") (pintype "unspecified+no_connect"))
    )
    (net (code "187") (name "unconnected-(U6-PC15-OSC32_OUT-Pad3)") (class "Default")
      (node (ref "U6") (pin "3") (pinfunction "PC15-OSC32_OUT_3") (pintype "unspecified+no_connect"))
    )
    (net (code "188") (name "unconnected-(U6-PD0-Pad38)") (class "Default")
      (node (ref "U6") (pin "38") (pinfunction "PD0_38") (pintype "unspecified+no_connect"))
    )
    (net (code "189") (name "unconnected-(U6-PD1-Pad39)") (class "Default")
      (node (ref "U6") (pin "39") (pinfunction "PD1_39") (pintype "unspecified+no_connect"))
    )
    (net (code "190") (name "unconnected-(U6-PD2-Pad40)") (class "Default")
      (node (ref "U6") (pin "40") (pinfunction "PD2_40") (pintype "unspecified+no_connect"))
    )
    (net (code "191") (name "unconnected-(U6-PD3-Pad41)") (class "Default")
      (node (ref "U6") (pin "41") (pinfunction "PD3_41") (pintype "unspecified+no_connect"))
    )
    (net (code "192") (name "unconnected-(U6-PF0-OSC_IN-Pad8)") (class "Default")
      (node (ref "U6") (pin "8") (pinfunction "PF0-OSC_IN_8") (pintype "unspecified+no_connect"))
    )
    (net (code "193") (name "unconnected-(U6-PF1-OSC_OUT-Pad9)") (class "Default")
      (node (ref "U6") (pin "9") (pinfunction "PF1-OSC_OUT_9") (pintype "unspecified+no_connect"))
    )
    (net (code "194") (name "unconnected-(U6-VBAT-Pad4)") (class "Default")
      (node (ref "U6") (pin "4") (pinfunction "VBAT_4") (pintype "unspecified+no_connect"))
    )
    (net (code "195") (name "unconnected-(U7-PA3-Pad14)") (class "Default")
      (node (ref "U7") (pin "14") (pinfunction "PA3_14") (pintype "unspecified+no_connect"))
    )
    (net (code "196") (name "unconnected-(U7-PA6-Pad17)") (class "Default")
      (node (ref "U7") (pin "17") (pinfunction "PA6_17") (pintype "unspecified+no_connect"))
    )
    (net (code "197") (name "unconnected-(U7-PA9-Pad29)") (class "Default")
      (node (ref "U7") (pin "29") (pinfunction "PA9_29") (pintype "unspecified+no_connect"))
    )
    (net (code "198") (name "unconnected-(U7-PA10-Pad32)") (class "Default")
      (node (ref "U7") (pin "32") (pinfunction "PA10_32") (pintype "unspecified+no_connect"))
    )
    (net (code "199") (name "unconnected-(U7-PA15-Pad37)") (class "Default")
      (node (ref "U7") (pin "37") (pinfunction "PA15_37") (pintype "unspecified+no_connect"))
    )
    (net (code "200") (name "unconnected-(U7-PB2-Pad21)") (class "Default")
      (node (ref "U7") (pin "21") (pinfunction "PB2_21") (pintype "unspecified+no_connect"))
    )
    (net (code "201") (name "unconnected-(U7-PB3-Pad42)") (class "Default")
      (node (ref "U7") (pin "42") (pinfunction "PB3_42") (pintype "unspecified+no_connect"))
    )
    (net (code "202") (name "unconnected-(U7-PB4-Pad43)") (class "Default")
      (node (ref "U7") (pin "43") (pinfunction "PB4_43") (pintype "unspecified+no_connect"))
    )
    (net (code "203") (name "unconnected-(U7-PB5-Pad44)") (class "Default")
      (node (ref "U7") (pin "44") (pinfunction "PB5_44") (pintype "unspecified+no_connect"))
    )
    (net (code "204") (name "unconnected-(U7-PB6-Pad45)") (class "Default")
      (node (ref "U7") (pin "45") (pinfunction "PB6_45") (pintype "unspecified+no_connect"))
    )
    (net (code "205") (name "unconnected-(U7-PB7-Pad46)") (class "Default")
      (node (ref "U7") (pin "46") (pinfunction "PB7_46") (pintype "unspecified+no_connect"))
    )
    (net (code "206") (name "unconnected-(U7-PB8-Pad47)") (class "Default")
      (node (ref "U7") (pin "47") (pinfunction "PB8_47") (pintype "unspecified+no_connect"))
    )
    (net (code "207") (name "unconnected-(U7-PB9-Pad48)") (class "Default")
      (node (ref "U7") (pin "48") (pinfunction "PB9_48") (pintype "unspecified+no_connect"))
    )
    (net (code "208") (name "unconnected-(U7-PB10-Pad22)") (class "Default")
      (node (ref "U7") (pin "22") (pinfunction "PB10_22") (pintype "unspecified+no_connect"))
    )
    (net (code "209") (name "unconnected-(U7-PB11-Pad23)") (class "Default")
      (node (ref "U7") (pin "23") (pinfunction "PB11_23") (pintype "unspecified+no_connect"))
    )
    (net (code "210") (name "unconnected-(U7-PB12-Pad24)") (class "Default")
      (node (ref "U7") (pin "24") (pinfunction "PB12_24") (pintype "unspecified+no_connect"))
    )
    (net (code "211") (name "unconnected-(U7-PB13-Pad25)") (class "Default")
      (node (ref "U7") (pin "25") (pinfunction "PB13_25") (pintype "unspecified+no_connect"))
    )
    (net (code "212") (name "unconnected-(U7-PB14-Pad26)") (class "Default")
      (node (ref "U7") (pin "26") (pinfunction "PB14_26") (pintype "unspecified+no_connect"))
    )
    (net (code "213") (name "unconnected-(U7-PB15-Pad27)") (class "Default")
      (node (ref "U7") (pin "27") (pinfunction "PB15_27") (pintype "unspecified+no_connect"))
    )
    (net (code "214") (name "unconnected-(U7-PC6-Pad30)") (class "Default")
      (node (ref "U7") (pin "30") (pinfunction "PC6_30") (pintype "unspecified+no_connect"))
    )
    (net (code "215") (name "unconnected-(U7-PC7-Pad31)") (class "Default")
      (node (ref "U7") (pin "31") (pinfunction "PC7_31") (pintype "unspecified+no_connect"))
    )
    (net (code "216") (name "unconnected-(U7-PC13-Pad1)") (class "Default")
      (node (ref "U7") (pin "1") (pinfunction "PC13_1") (pintype "unspecified+no_connect"))
    )
    (net (code "217") (name "unconnected-(U7-PC14-OSC32_IN-Pad2)") (class "Default")
      (node (ref "U7") (pin "2") (pinfunction "PC14-OSC32_IN_2") (pintype "unspecified+no_connect"))
    )
    (net (code "218") (name "unconnected-(U7-PC15-OSC32_OUT-Pad3)") (class "Default")
      (node (ref "U7") (pin "3") (pinfunction "PC15-OSC32_OUT_3") (pintype "unspecified+no_connect"))
    )
    (net (code "219") (name "unconnected-(U7-PD0-Pad38)") (class "Default")
      (node (ref "U7") (pin "38") (pinfunction "PD0_38") (pintype "unspecified+no_connect"))
    )
    (net (code "220") (name "unconnected-(U7-PD1-Pad39)") (class "Default")
      (node (ref "U7") (pin "39") (pinfunction "PD1_39") (pintype "unspecified+no_connect"))
    )
    (net (code "221") (name "unconnected-(U7-PD2-Pad40)") (class "Default")
      (node (ref "U7") (pin "40") (pinfunction "PD2_40") (pintype "unspecified+no_connect"))
    )
    (net (code "222") (name "unconnected-(U7-PD3-Pad41)") (class "Default")
      (node (ref "U7") (pin "41") (pinfunction "PD3_41") (pintype "unspecified+no_connect"))
    )
    (net (code "223") (name "unconnected-(U7-PF0-OSC_IN-Pad8)") (class "Default")
      (node (ref "U7") (pin "8") (pinfunction "PF0-OSC_IN_8") (pintype "unspecified+no_connect"))
    )
    (net (code "224") (name "unconnected-(U7-PF1-OSC_OUT-Pad9)") (class "Default")
      (node (ref "U7") (pin "9") (pinfunction "PF1-OSC_OUT_9") (pintype "unspecified+no_connect"))
    )
    (net (code "225") (name "unconnected-(U7-VBAT-Pad4)") (class "Default")
      (node (ref "U7") (pin "4") (pinfunction "VBAT_4") (pintype "unspecified+no_connect"))
    )
    (net (code "226") (name "unconnected-(U8-PA3-Pad14)") (class "Default")
      (node (ref "U8") (pin "14") (pinfunction "PA3_14") (pintype "unspecified+no_connect"))
    )
    (net (code "227") (name "unconnected-(U8-PA6-Pad17)") (class "Default")
      (node (ref "U8") (pin "17") (pinfunction "PA6_17") (pintype "unspecified+no_connect"))
    )
    (net (code "228") (name "unconnected-(U8-PA9-Pad29)") (class "Default")
      (node (ref "U8") (pin "29") (pinfunction "PA9_29") (pintype "unspecified+no_connect"))
    )
    (net (code "229") (name "unconnected-(U8-PA10-Pad32)") (class "Default")
      (node (ref "U8") (pin "32") (pinfunction "PA10_32") (pintype "unspecified+no_connect"))
    )
    (net (code "230") (name "unconnected-(U8-PA15-Pad37)") (class "Default")
      (node (ref "U8") (pin "37") (pinfunction "PA15_37") (pintype "unspecified+no_connect"))
    )
    (net (code "231") (name "unconnected-(U8-PB2-Pad21)") (class "Default")
      (node (ref "U8") (pin "21") (pinfunction "PB2_21") (pintype "unspecified+no_connect"))
    )
    (net (code "232") (name "unconnected-(U8-PB3-Pad42)") (class "Default")
      (node (ref "U8") (pin "42") (pinfunction "PB3_42") (pintype "unspecified+no_connect"))
    )
    (net (code "233") (name "unconnected-(U8-PB4-Pad43)") (class "Default")
      (node (ref "U8") (pin "43") (pinfunction "PB4_43") (pintype "unspecified+no_connect"))
    )
    (net (code "234") (name "unconnected-(U8-PB5-Pad44)") (class "Default")
      (node (ref "U8") (pin "44") (pinfunction "PB5_44") (pintype "unspecified+no_connect"))
    )
    (net (code "235") (name "unconnected-(U8-PB6-Pad45)") (class "Default")
      (node (ref "U8") (pin "45") (pinfunction "PB6_45") (pintype "unspecified+no_connect"))
    )
    (net (code "236") (name "unconnected-(U8-PB7-Pad46)") (class "Default")
      (node (ref "U8") (pin "46") (pinfunction "PB7_46") (pintype "unspecified+no_connect"))
    )
    (net (code "237") (name "unconnected-(U8-PB8-Pad47)") (class "Default")
      (node (ref "U8") (pin "47") (pinfunction "PB8_47") (pintype "unspecified+no_connect"))
    )
    (net (code "238") (name "unconnected-(U8-PB9-Pad48)") (class "Default")
      (node (ref "U8") (pin "48") (pinfunction "PB9_48") (pintype "unspecified+no_connect"))
    )
    (net (code "239") (name "unconnected-(U8-PB10-Pad22)") (class "Default")
      (node (ref "U8") (pin "22") (pinfunction "PB10_22") (pintype "unspecified+no_connect"))
    )
    (net (code "240") (name "unconnected-(U8-PB11-Pad23)") (class "Default")
      (node (ref "U8") (pin "23") (pinfunction "PB11_23") (pintype "unspecified+no_connect"))
    )
    (net (code "241") (name "unconnected-(U8-PB12-Pad24)") (class "Default")
      (node (ref "U8") (pin "24") (pinfunction "PB12_24") (pintype "unspecified+no_connect"))
    )
    (net (code "242") (name "unconnected-(U8-PB13-Pad25)") (class "Default")
      (node (ref "U8") (pin "25") (pinfunction "PB13_25") (pintype "unspecified+no_connect"))
    )
    (net (code "243") (name "unconnected-(U8-PB14-Pad26)") (class "Default")
      (node (ref "U8") (pin "26") (pinfunction "PB14_26") (pintype "unspecified+no_connect"))
    )
    (net (code "244") (name "unconnected-(U8-PB15-Pad27)") (class "Default")
      (node (ref "U8") (pin "27") (pinfunction "PB15_27") (pintype "unspecified+no_connect"))
    )
    (net (code "245") (name "unconnected-(U8-PC6-Pad30)") (class "Default")
      (node (ref "U8") (pin "30") (pinfunction "PC6_30") (pintype "unspecified+no_connect"))
    )
    (net (code "246") (name "unconnected-(U8-PC7-Pad31)") (class "Default")
      (node (ref "U8") (pin "31") (pinfunction "PC7_31") (pintype "unspecified+no_connect"))
    )
    (net (code "247") (name "unconnected-(U8-PC13-Pad1)") (class "Default")
      (node (ref "U8") (pin "1") (pinfunction "PC13_1") (pintype "unspecified+no_connect"))
    )
    (net (code "248") (name "unconnected-(U8-PC14-OSC32_IN-Pad2)") (class "Default")
      (node (ref "U8") (pin "2") (pinfunction "PC14-OSC32_IN_2") (pintype "unspecified+no_connect"))
    )
    (net (code "249") (name "unconnected-(U8-PC15-OSC32_OUT-Pad3)") (class "Default")
      (node (ref "U8") (pin "3") (pinfunction "PC15-OSC32_OUT_3") (pintype "unspecified+no_connect"))
    )
    (net (code "250") (name "unconnected-(U8-PD0-Pad38)") (class "Default")
      (node (ref "U8") (pin "38") (pinfunction "PD0_38") (pintype "unspecified+no_connect"))
    )
    (net (code "251") (name "unconnected-(U8-PD1-Pad39)") (class "Default")
      (node (ref "U8") (pin "39") (pinfunction "PD1_39") (pintype "unspecified+no_connect"))
    )
    (net (code "252") (name "unconnected-(U8-PD2-Pad40)") (class "Default")
      (node (ref "U8") (pin "40") (pinfunction "PD2_40") (pintype "unspecified+no_connect"))
    )
    (net (code "253") (name "unconnected-(U8-PD3-Pad41)") (class "Default")
      (node (ref "U8") (pin "41") (pinfunction "PD3_41") (pintype "unspecified+no_connect"))
    )
    (net (code "254") (name "unconnected-(U8-PF0-OSC_IN-Pad8)") (class "Default")
      (node (ref "U8") (pin "8") (pinfunction "PF0-OSC_IN_8") (pintype "unspecified+no_connect"))
    )
    (net (code "255") (name "unconnected-(U8-PF1-OSC_OUT-Pad9)") (class "Default")
      (node (ref "U8") (pin "9") (pinfunction "PF1-OSC_OUT_9") (pintype "unspecified+no_connect"))
    )
    (net (code "256") (name "unconnected-(U8-VBAT-Pad4)") (class "Default")
      (node (ref "U8") (pin "4") (pinfunction "VBAT_4") (pintype "unspecified+no_connect"))
    )
    (net (code "257") (name "unconnected-(U9-PA3-Pad14)") (class "Default")
      (node (ref "U9") (pin "14") (pinfunction "PA3_14") (pintype "unspecified+no_connect"))
    )
    (net (code "258") (name "unconnected-(U9-PA6-Pad17)") (class "Default")
      (node (ref "U9") (pin "17") (pinfunction "PA6_17") (pintype "unspecified+no_connect"))
    )
    (net (code "259") (name "unconnected-(U9-PA9-Pad29)") (class "Default")
      (node (ref "U9") (pin "29") (pinfunction "PA9_29") (pintype "unspecified+no_connect"))
    )
    (net (code "260") (name "unconnected-(U9-PA10-Pad32)") (class "Default")
      (node (ref "U9") (pin "32") (pinfunction "PA10_32") (pintype "unspecified+no_connect"))
    )
    (net (code "261") (name "unconnected-(U9-PA15-Pad37)") (class "Default")
      (node (ref "U9") (pin "37") (pinfunction "PA15_37") (pintype "unspecified+no_connect"))
    )
    (net (code "262") (name "unconnected-(U9-PB2-Pad21)") (class "Default")
      (node (ref "U9") (pin "21") (pinfunction "PB2_21") (pintype "unspecified+no_connect"))
    )
    (net (code "263") (name "unconnected-(U9-PB3-Pad42)") (class "Default")
      (node (ref "U9") (pin "42") (pinfunction "PB3_42") (pintype "unspecified+no_connect"))
    )
    (net (code "264") (name "unconnected-(U9-PB4-Pad43)") (class "Default")
      (node (ref "U9") (pin "43") (pinfunction "PB4_43") (pintype "unspecified+no_connect"))
    )
    (net (code "265") (name "unconnected-(U9-PB5-Pad44)") (class "Default")
      (node (ref "U9") (pin "44") (pinfunction "PB5_44") (pintype "unspecified+no_connect"))
    )
    (net (code "266") (name "unconnected-(U9-PB6-Pad45)") (class "Default")
      (node (ref "U9") (pin "45") (pinfunction "PB6_45") (pintype "unspecified+no_connect"))
    )
    (net (code "267") (name "unconnected-(U9-PB7-Pad46)") (class "Default")
      (node (ref "U9") (pin "46") (pinfunction "PB7_46") (pintype "unspecified+no_connect"))
    )
    (net (code "268") (name "unconnected-(U9-PB8-Pad47)") (class "Default")
      (node (ref "U9") (pin "47") (pinfunction "PB8_47") (pintype "unspecified+no_connect"))
    )
    (net (code "269") (name "unconnected-(U9-PB9-Pad48)") (class "Default")
      (node (ref "U9") (pin "48") (pinfunction "PB9_48") (pintype "unspecified+no_connect"))
    )
    (net (code "270") (name "unconnected-(U9-PB10-Pad22)") (class "Default")
      (node (ref "U9") (pin "22") (pinfunction "PB10_22") (pintype "unspecified+no_connect"))
    )
    (net (code "271") (name "unconnected-(U9-PB11-Pad23)") (class "Default")
      (node (ref "U9") (pin "23") (pinfunction "PB11_23") (pintype "unspecified+no_connect"))
    )
    (net (code "272") (name "unconnected-(U9-PB12-Pad24)") (class "Default")
      (node (ref "U9") (pin "24") (pinfunction "PB12_24") (pintype "unspecified+no_connect"))
    )
    (net (code "273") (name "unconnected-(U9-PB13-Pad25)") (class "Default")
      (node (ref "U9") (pin "25") (pinfunction "PB13_25") (pintype "unspecified+no_connect"))
    )
    (net (code "274") (name "unconnected-(U9-PB14-Pad26)") (class "Default")
      (node (ref "U9") (pin "26") (pinfunction "PB14_26") (pintype "unspecified+no_connect"))
    )
    (net (code "275") (name "unconnected-(U9-PB15-Pad27)") (class "Default")
      (node (ref "U9") (pin "27") (pinfunction "PB15_27") (pintype "unspecified+no_connect"))
    )
    (net (code "276") (name "unconnected-(U9-PC6-Pad30)") (class "Default")
      (node (ref "U9") (pin "30") (pinfunction "PC6_30") (pintype "unspecified+no_connect"))
    )
    (net (code "277") (name "unconnected-(U9-PC7-Pad31)") (class "Default")
      (node (ref "U9") (pin "31") (pinfunction "PC7_31") (pintype "unspecified+no_connect"))
    )
    (net (code "278") (name "unconnected-(U9-PC13-Pad1)") (class "Default")
      (node (ref "U9") (pin "1") (pinfunction "PC13_1") (pintype "unspecified+no_connect"))
    )
    (net (code "279") (name "unconnected-(U9-PC14-OSC32_IN-Pad2)") (class "Default")
      (node (ref "U9") (pin "2") (pinfunction "PC14-OSC32_IN_2") (pintype "unspecified+no_connect"))
    )
    (net (code "280") (name "unconnected-(U9-PC15-OSC32_OUT-Pad3)") (class "Default")
      (node (ref "U9") (pin "3") (pinfunction "PC15-OSC32_OUT_3") (pintype "unspecified+no_connect"))
    )
    (net (code "281") (name "unconnected-(U9-PD0-Pad38)") (class "Default")
      (node (ref "U9") (pin "38") (pinfunction "PD0_38") (pintype "unspecified+no_connect"))
    )
    (net (code "282") (name "unconnected-(U9-PD1-Pad39)") (class "Default")
      (node (ref "U9") (pin "39") (pinfunction "PD1_39") (pintype "unspecified+no_connect"))
    )
    (net (code "283") (name "unconnected-(U9-PD2-Pad40)") (class "Default")
      (node (ref "U9") (pin "40") (pinfunction "PD2_40") (pintype "unspecified+no_connect"))
    )
    (net (code "284") (name "unconnected-(U9-PD3-Pad41)") (class "Default")
      (node (ref "U9") (pin "41") (pinfunction "PD3_41") (pintype "unspecified+no_connect"))
    )
    (net (code "285") (name "unconnected-(U9-PF0-OSC_IN-Pad8)") (class "Default")
      (node (ref "U9") (pin "8") (pinfunction "PF0-OSC_IN_8") (pintype "unspecified+no_connect"))
    )
    (net (code "286") (name "unconnected-(U9-PF1-OSC_OUT-Pad9)") (class "Default")
      (node (ref "U9") (pin "9") (pinfunction "PF1-OSC_OUT_9") (pintype "unspecified+no_connect"))
    )
    (net (code "287") (name "unconnected-(U9-VBAT-Pad4)") (class "Default")
      (node (ref "U9") (pin "4") (pinfunction "VBAT_4") (pintype "unspecified+no_connect"))
    )
    (net (code "288") (name "unconnected-(U12-EP-Pad9)") (class "Default")
      (node (ref "U12") (pin "9") (pinfunction "EP_9") (pintype "unspecified+no_connect"))
    )
    (net (code "289") (name "unconnected-(U12-PGOOD-Pad6)") (class "Default")
      (node (ref "U12") (pin "6") (pinfunction "PGOOD_6") (pintype "unspecified+no_connect"))
    )
  )
)
